# backplane.net
KiCad netlist of a schematic drawn in EAGLE
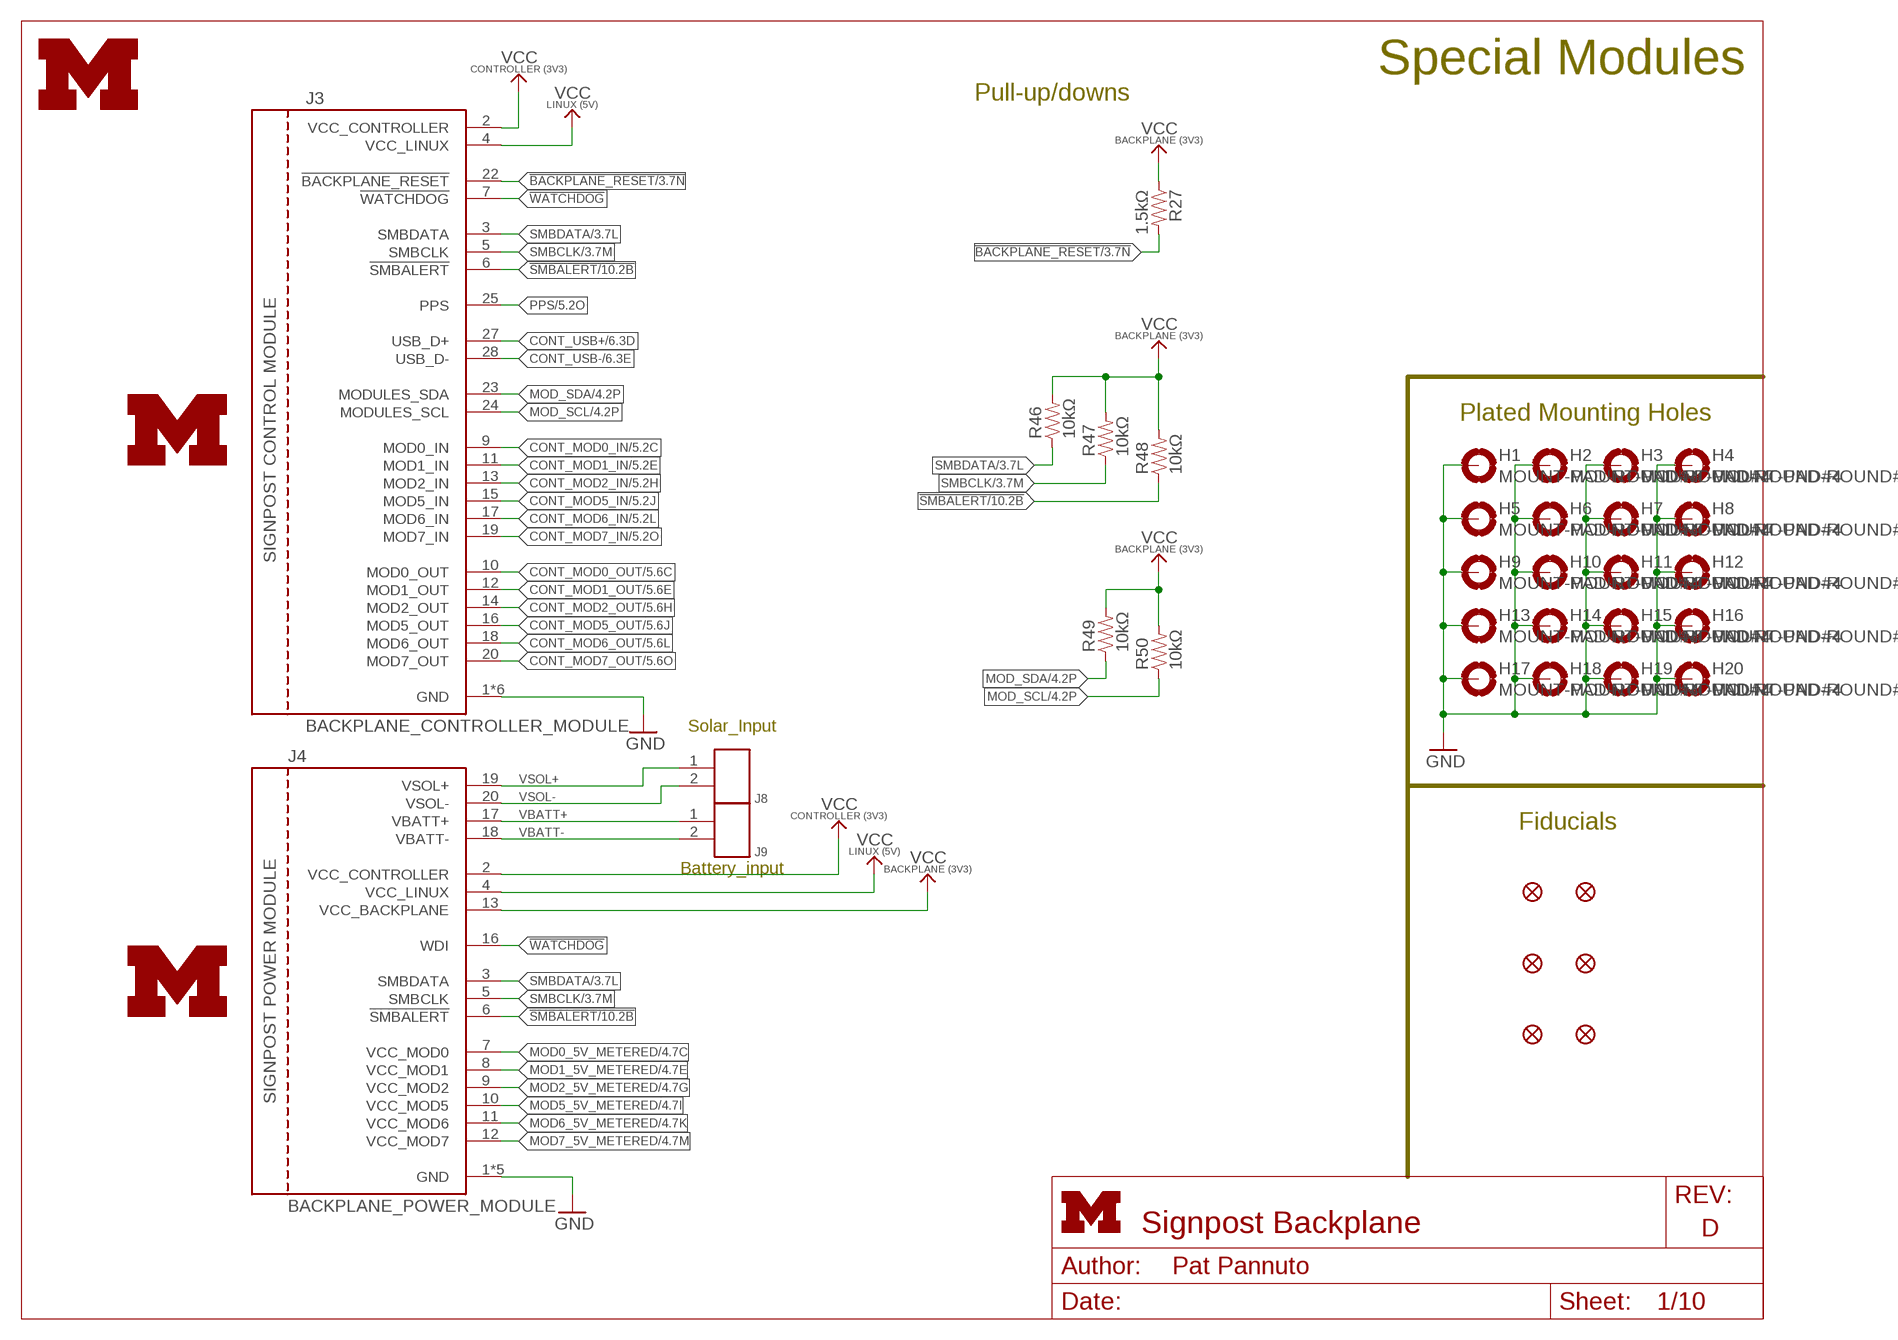
[diagram p0: schematic, sheet 1]
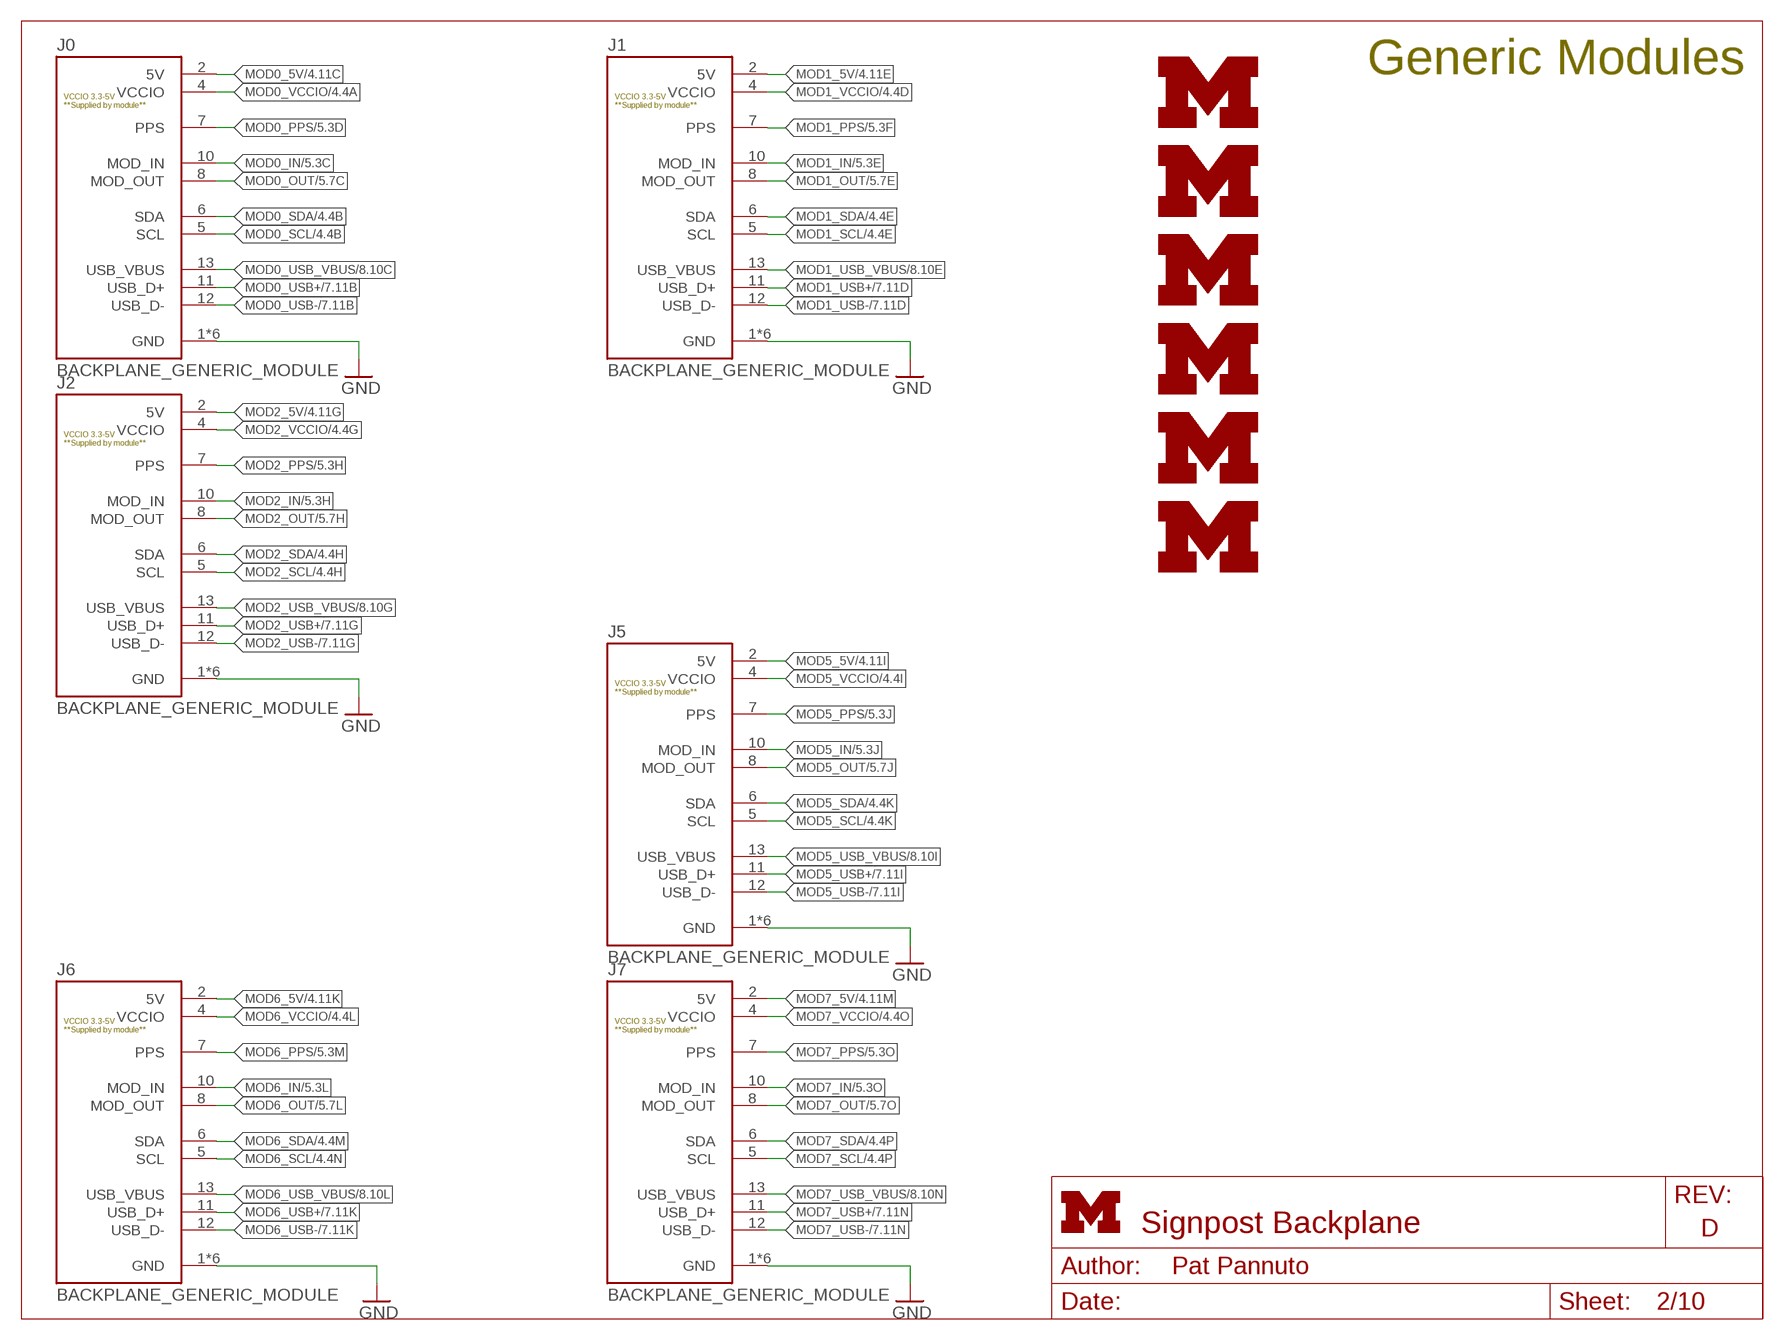
[diagram p1: schematic, sheet 2]
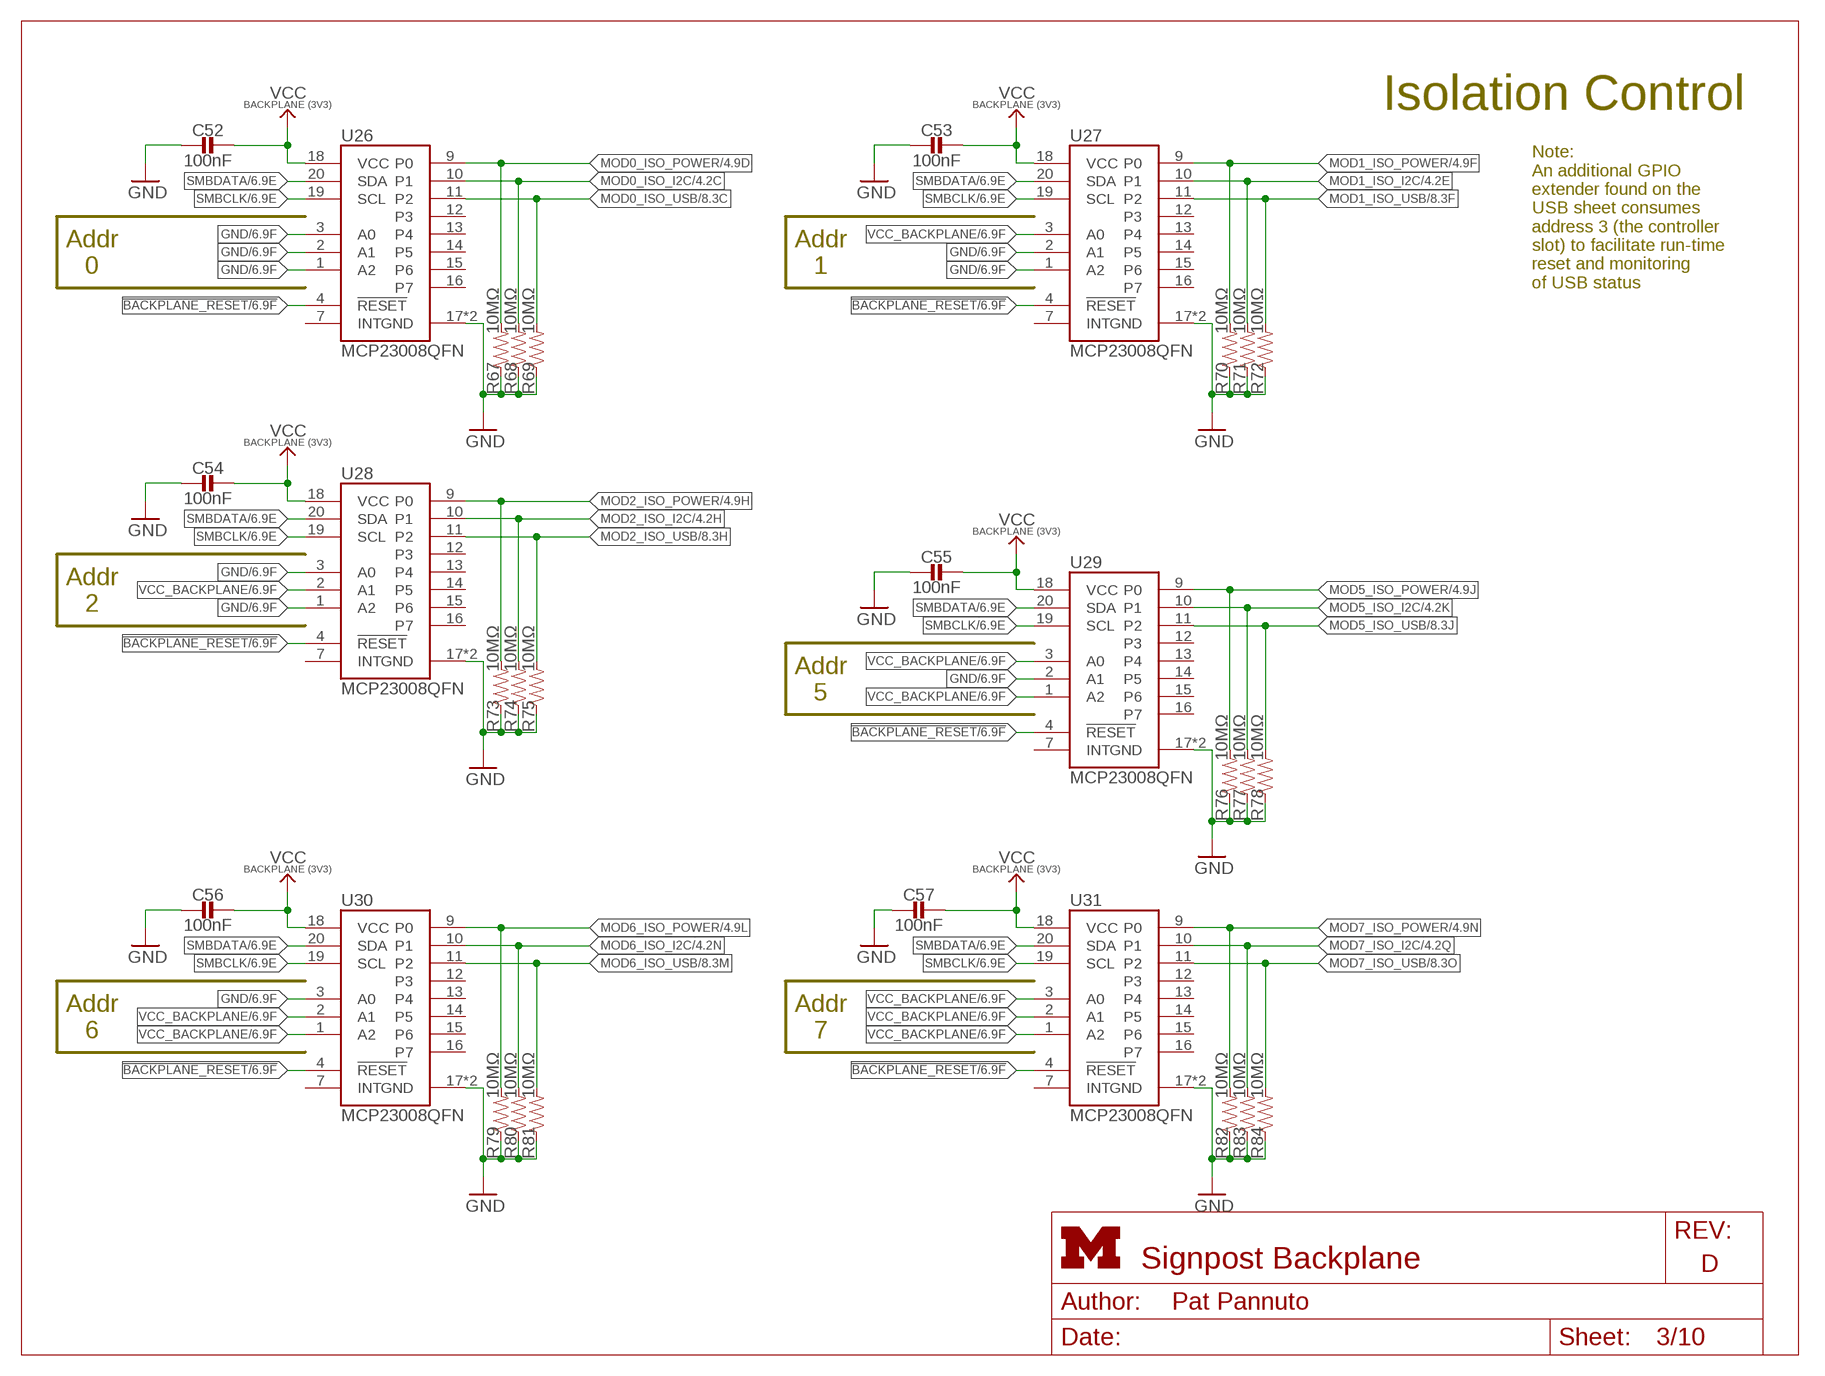
[diagram p2: schematic, sheet 3]
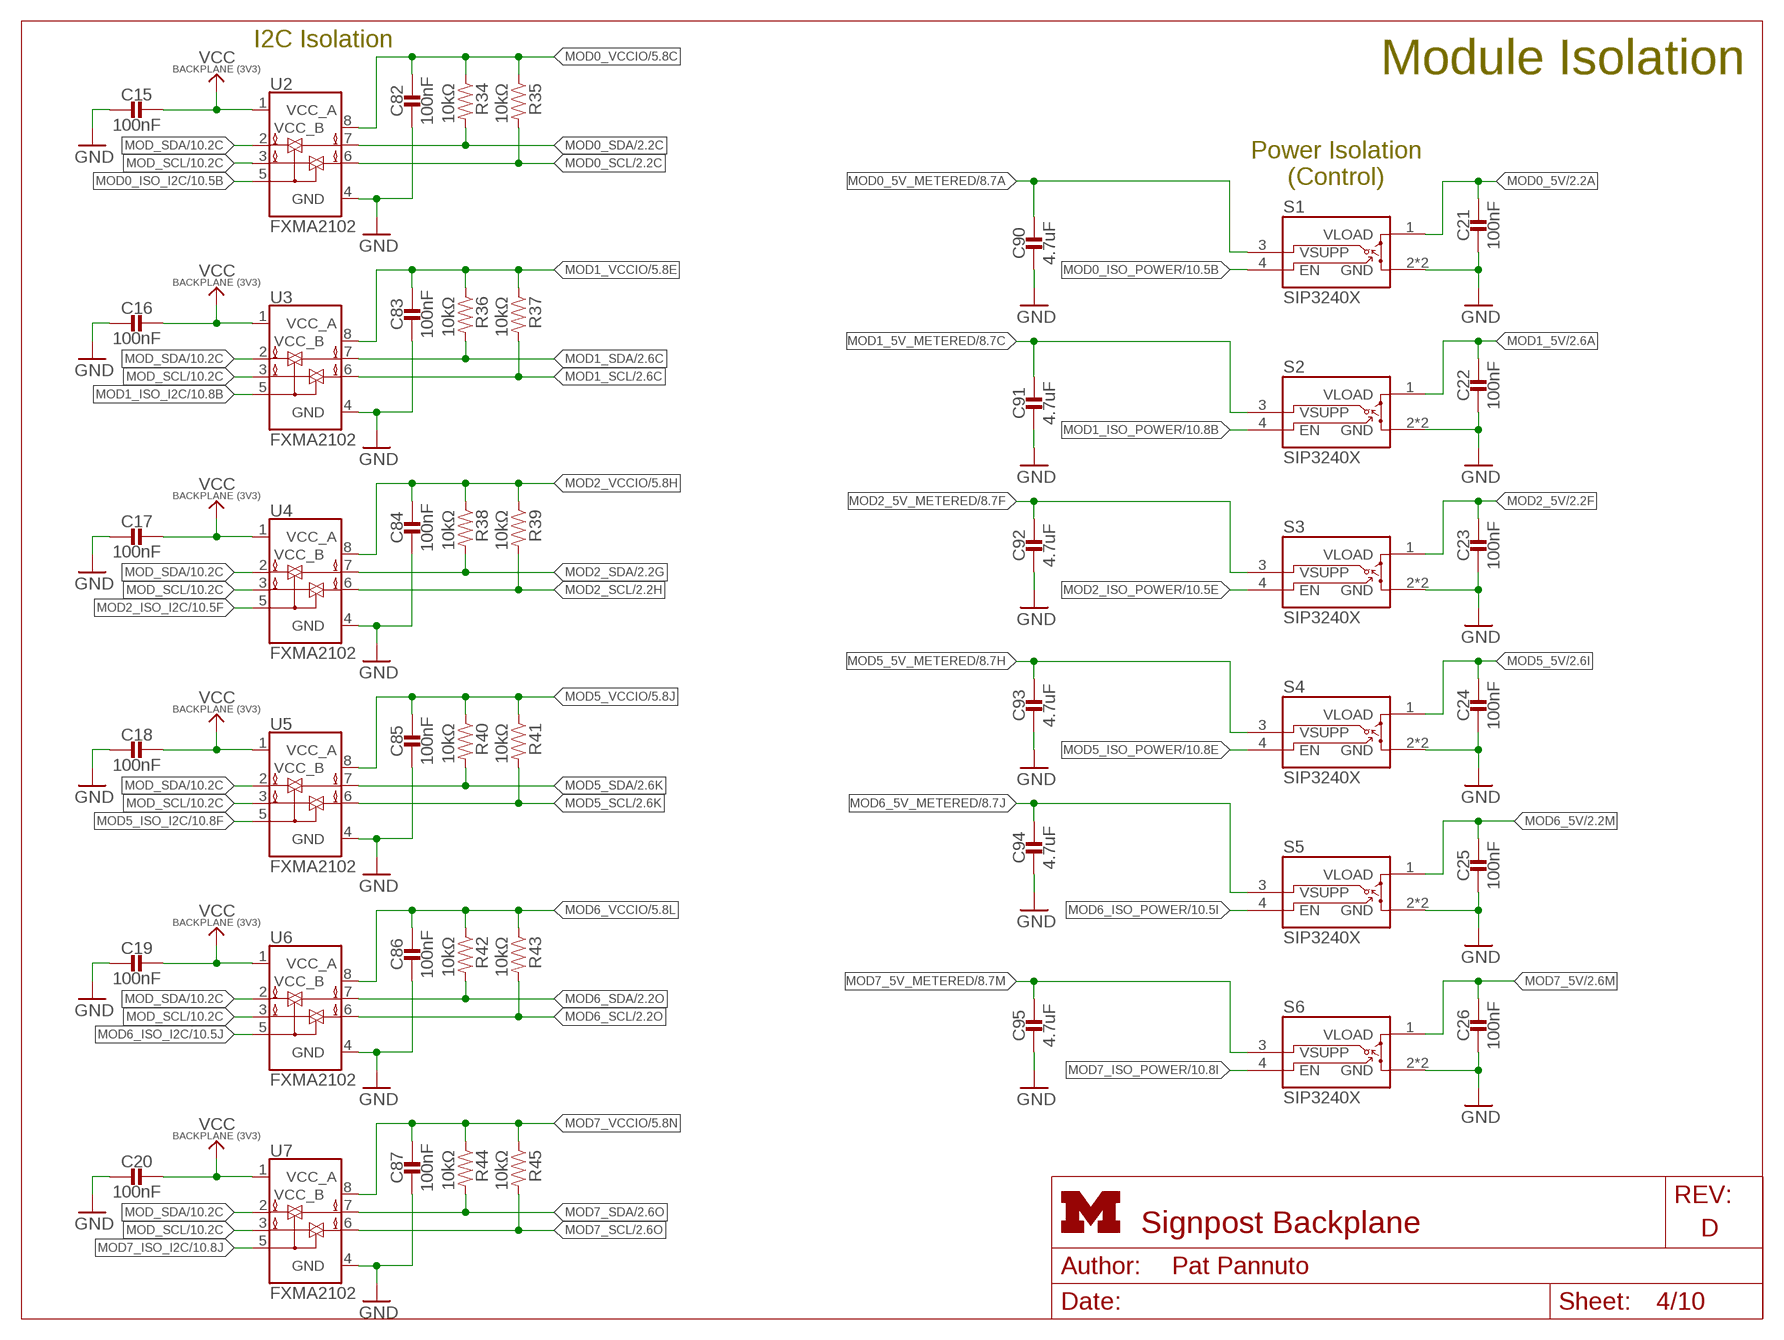
[diagram p3: schematic, sheet 4]
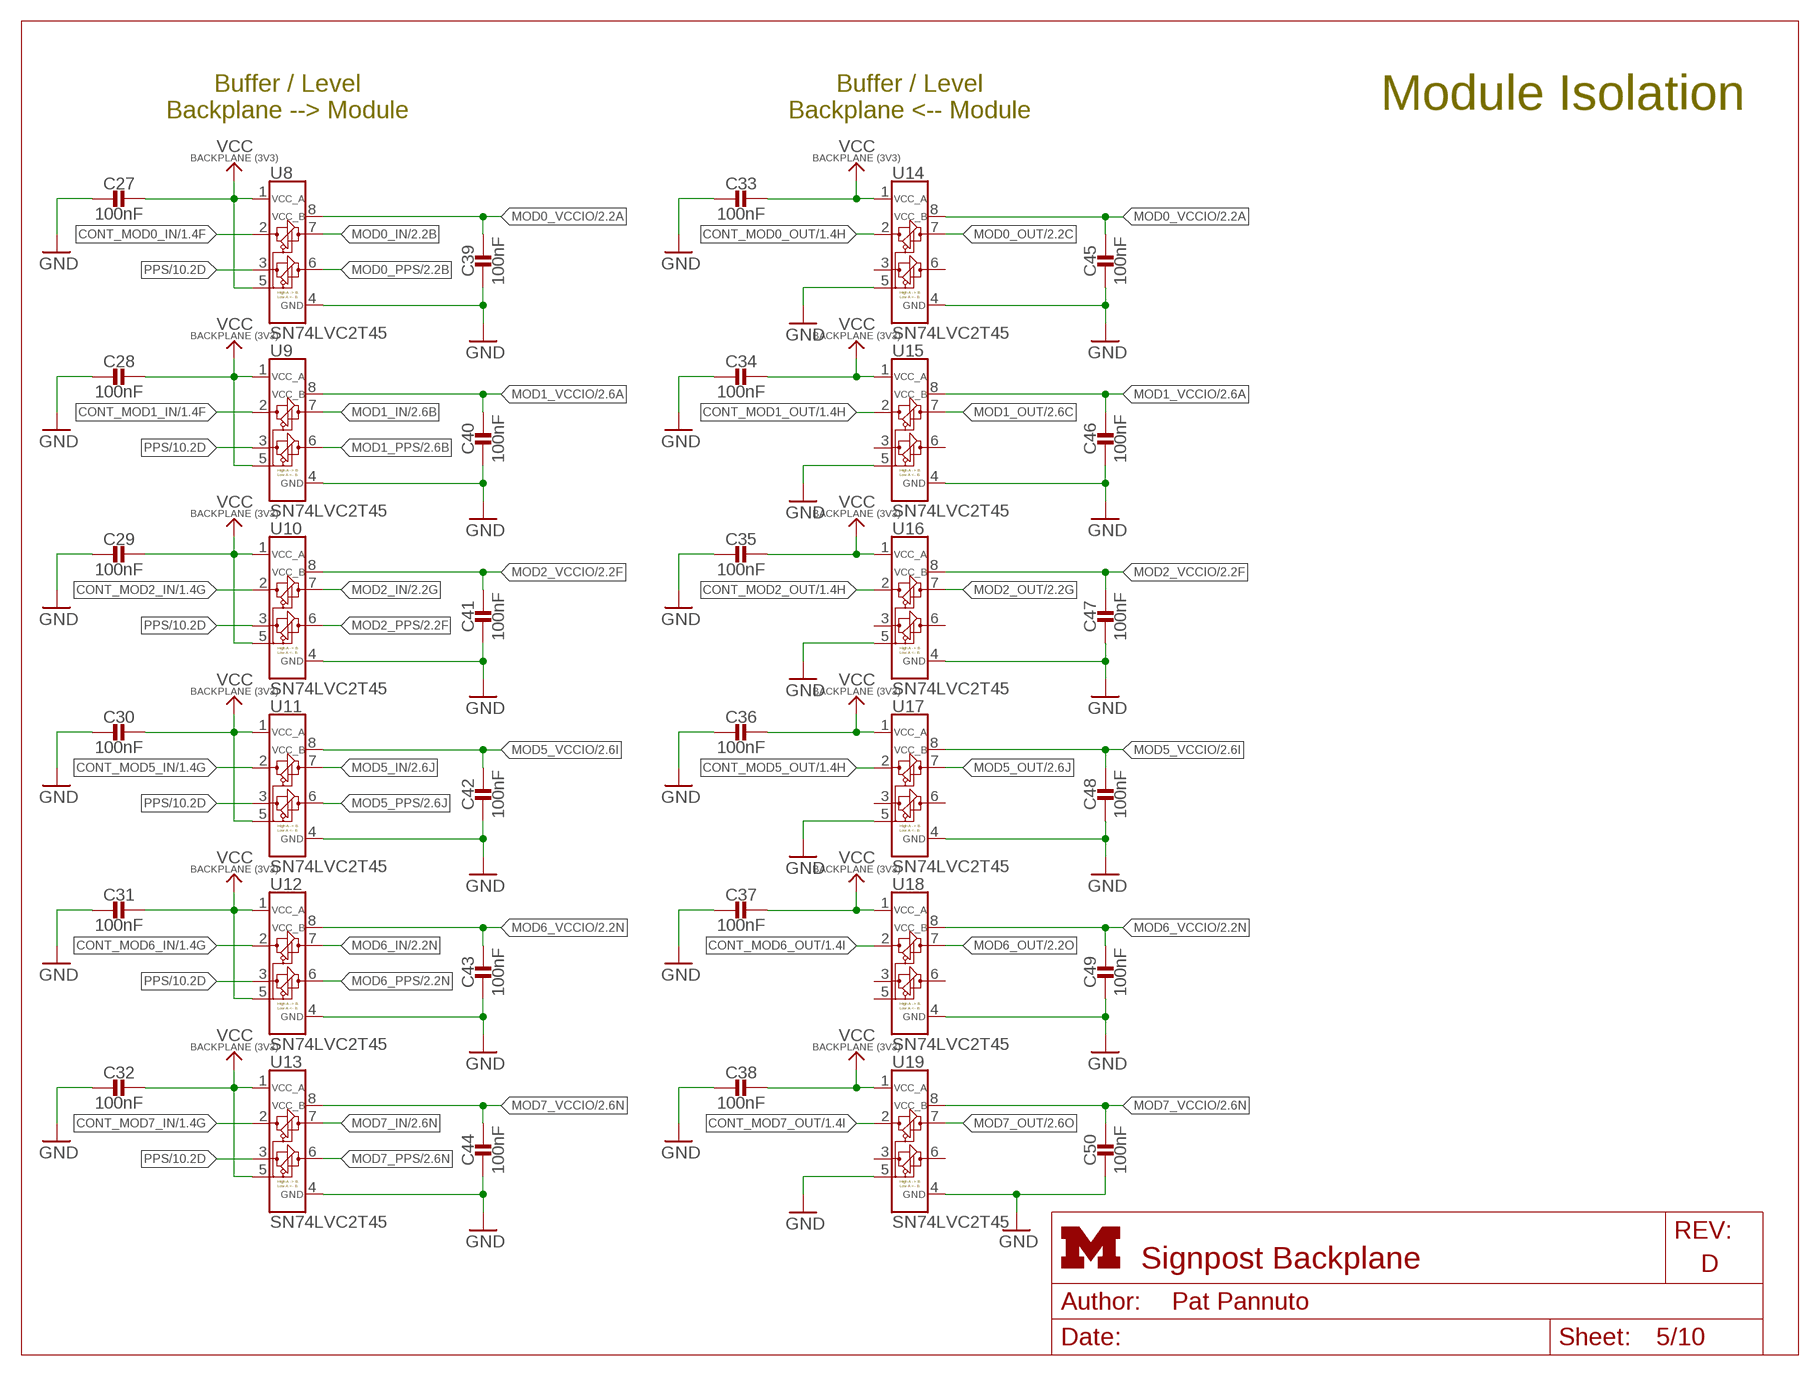
[diagram p4: schematic, sheet 5]
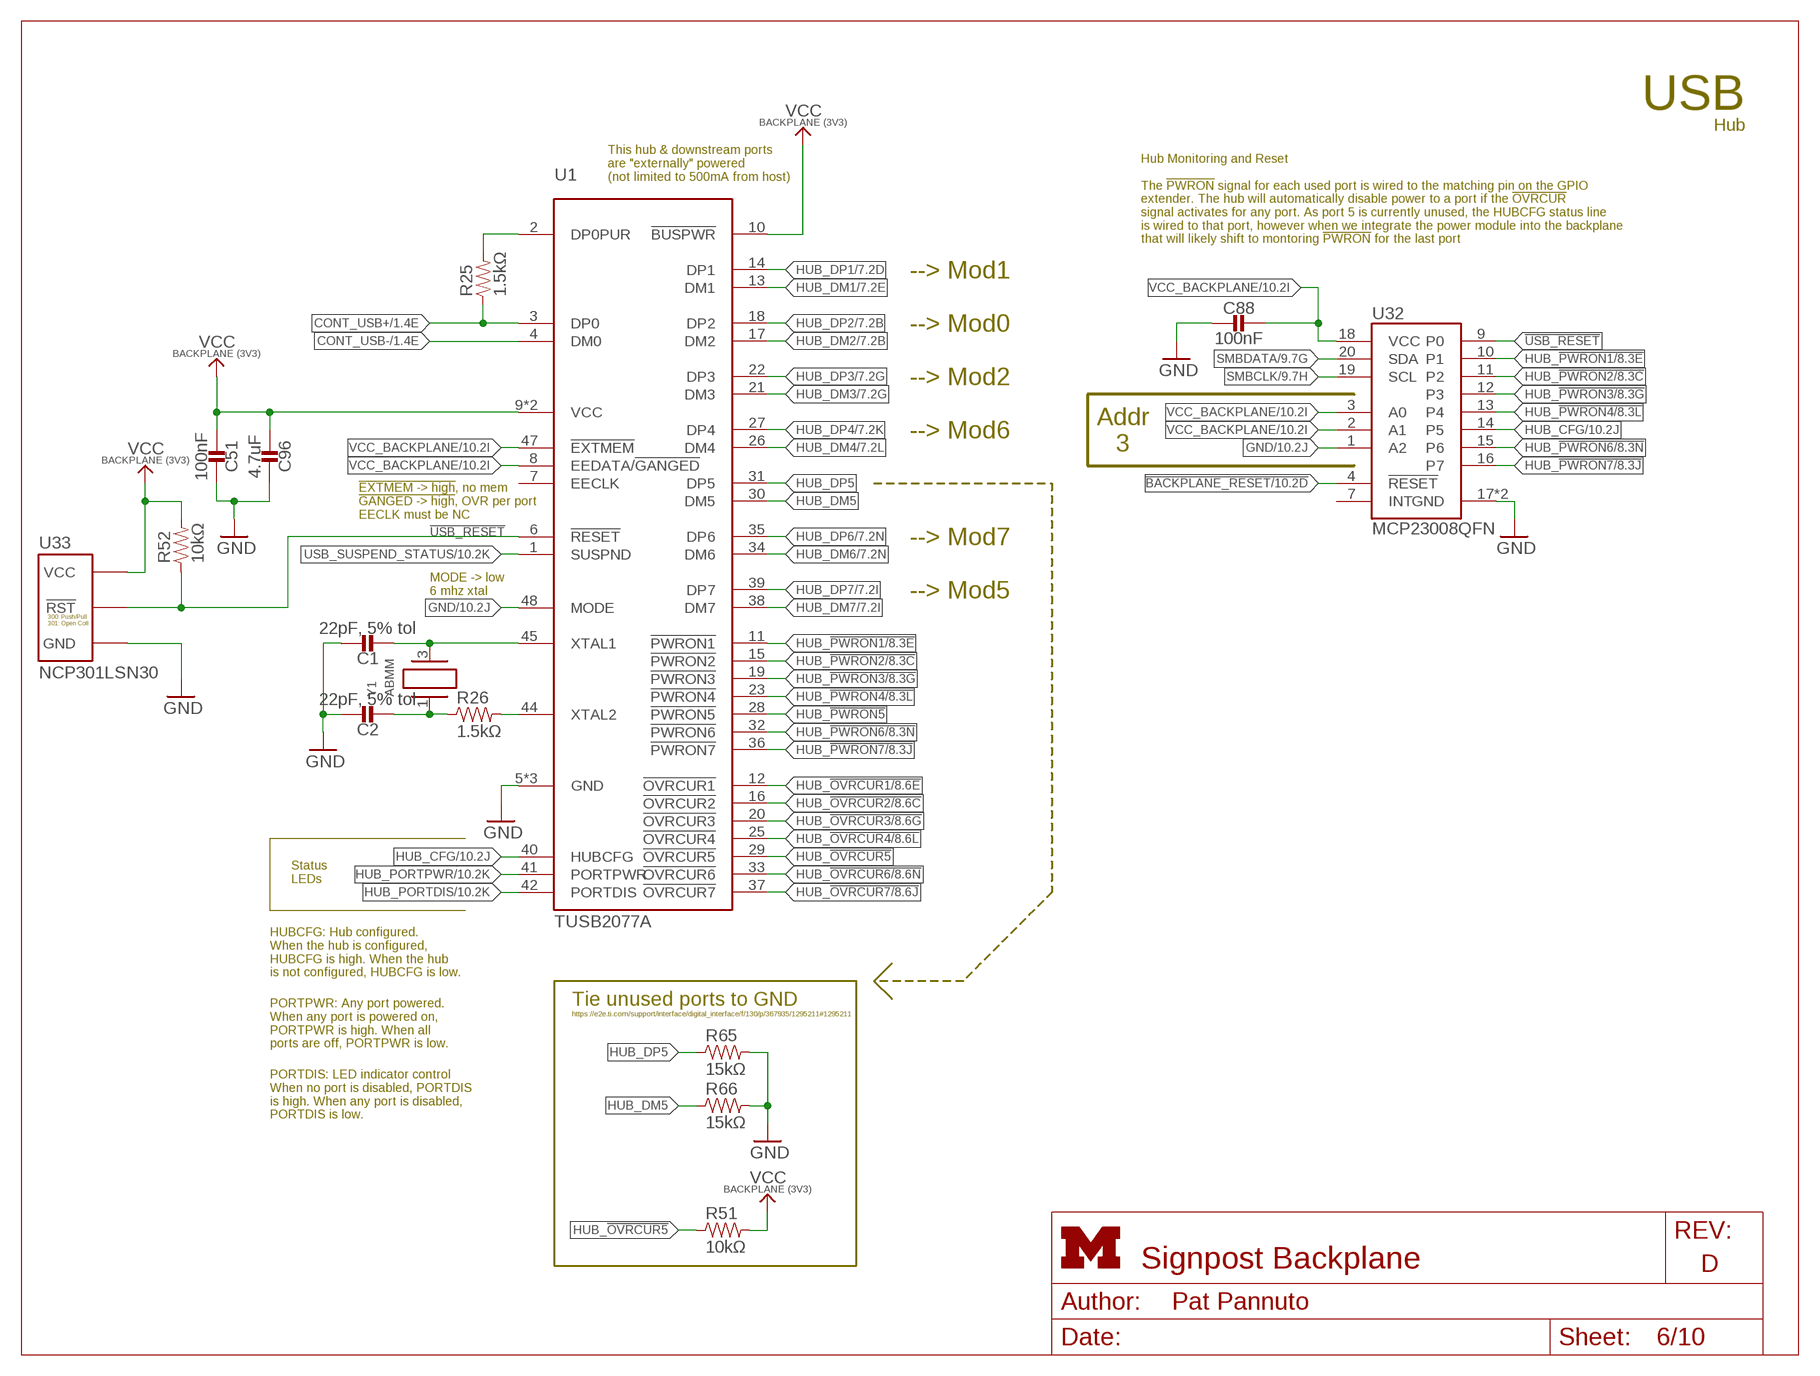
[diagram p5: schematic, sheet 6]
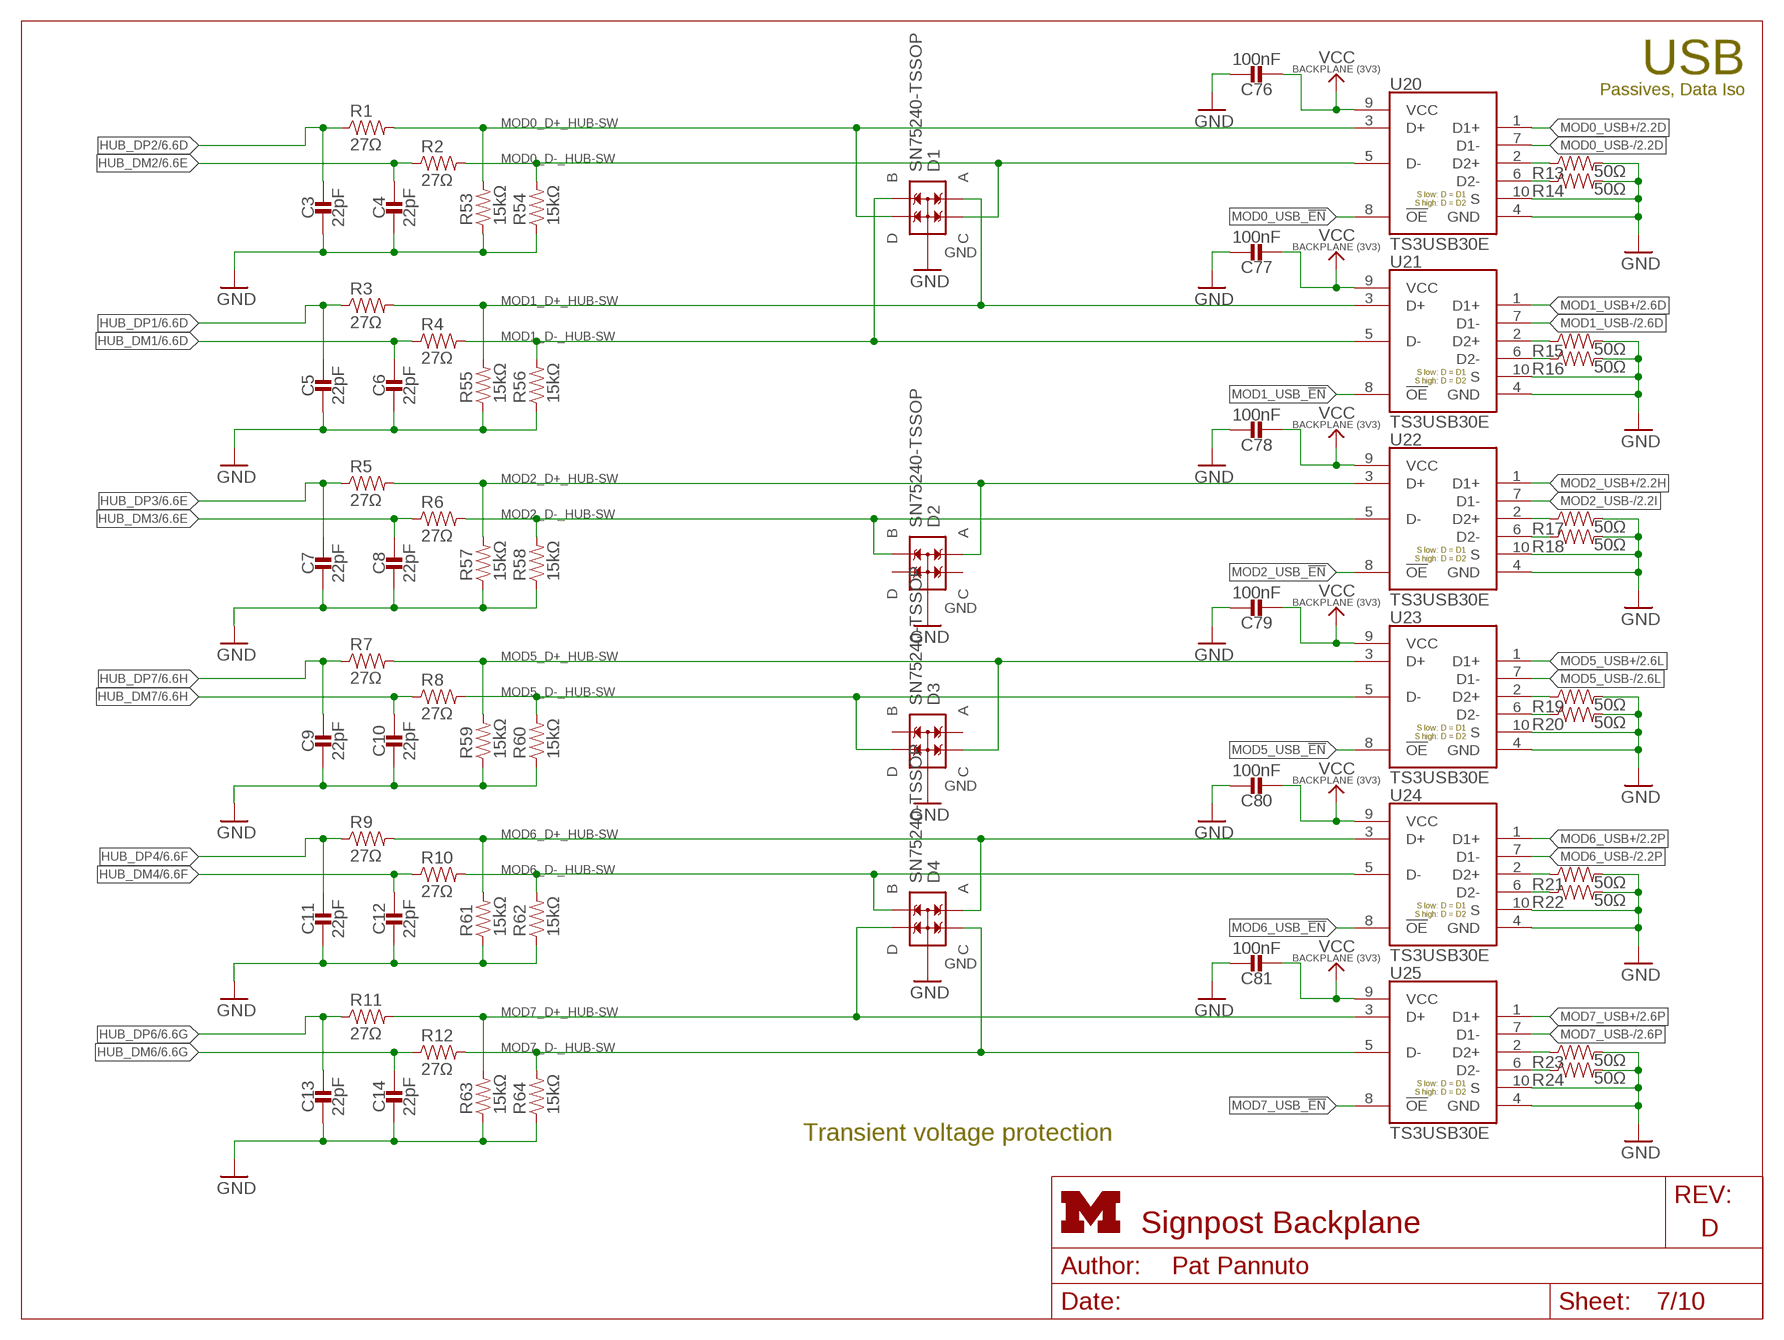
[diagram p6: schematic, sheet 7]
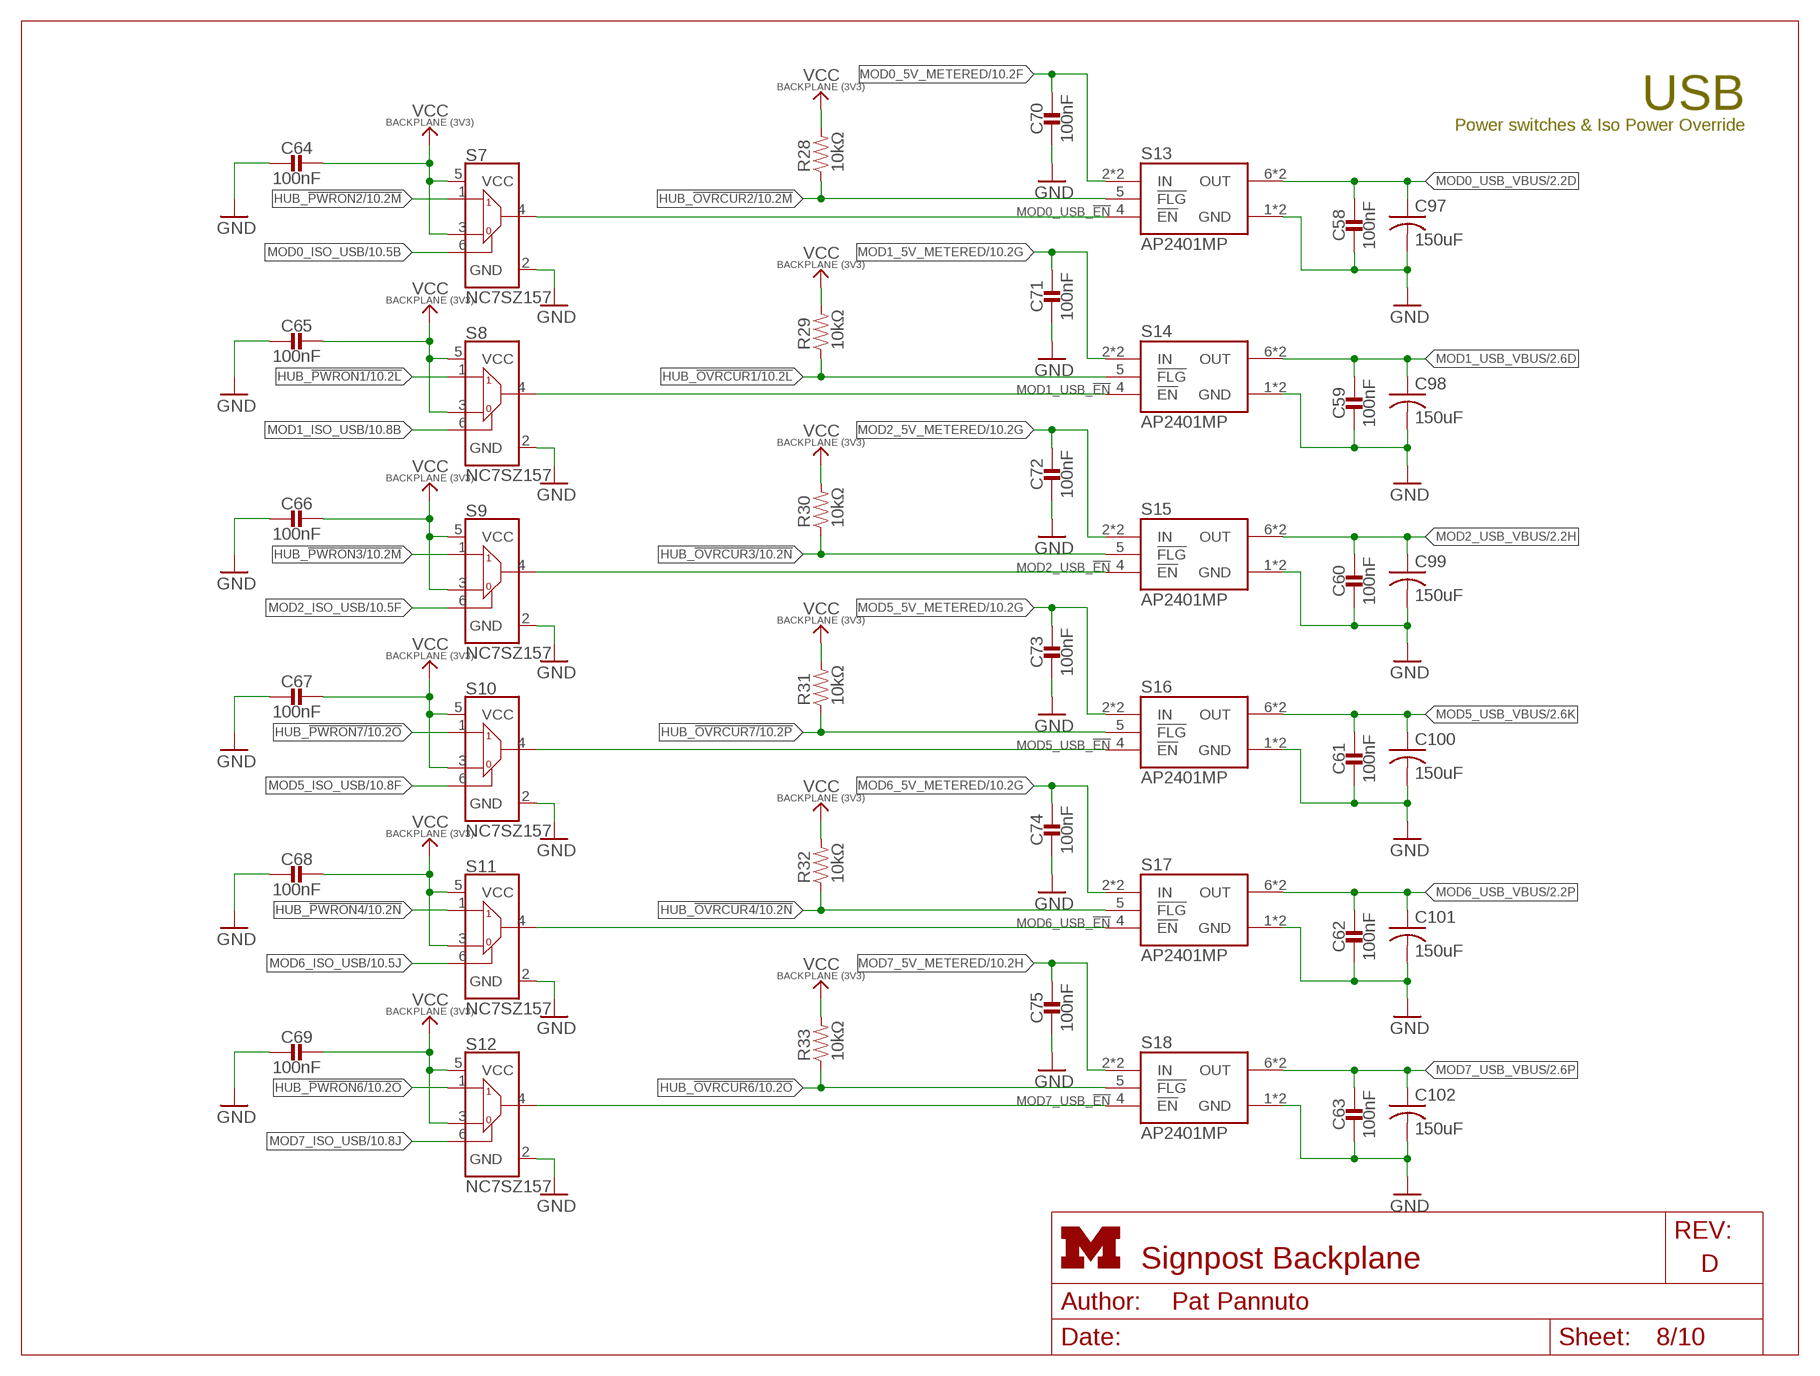
[diagram p7: schematic, sheet 8]
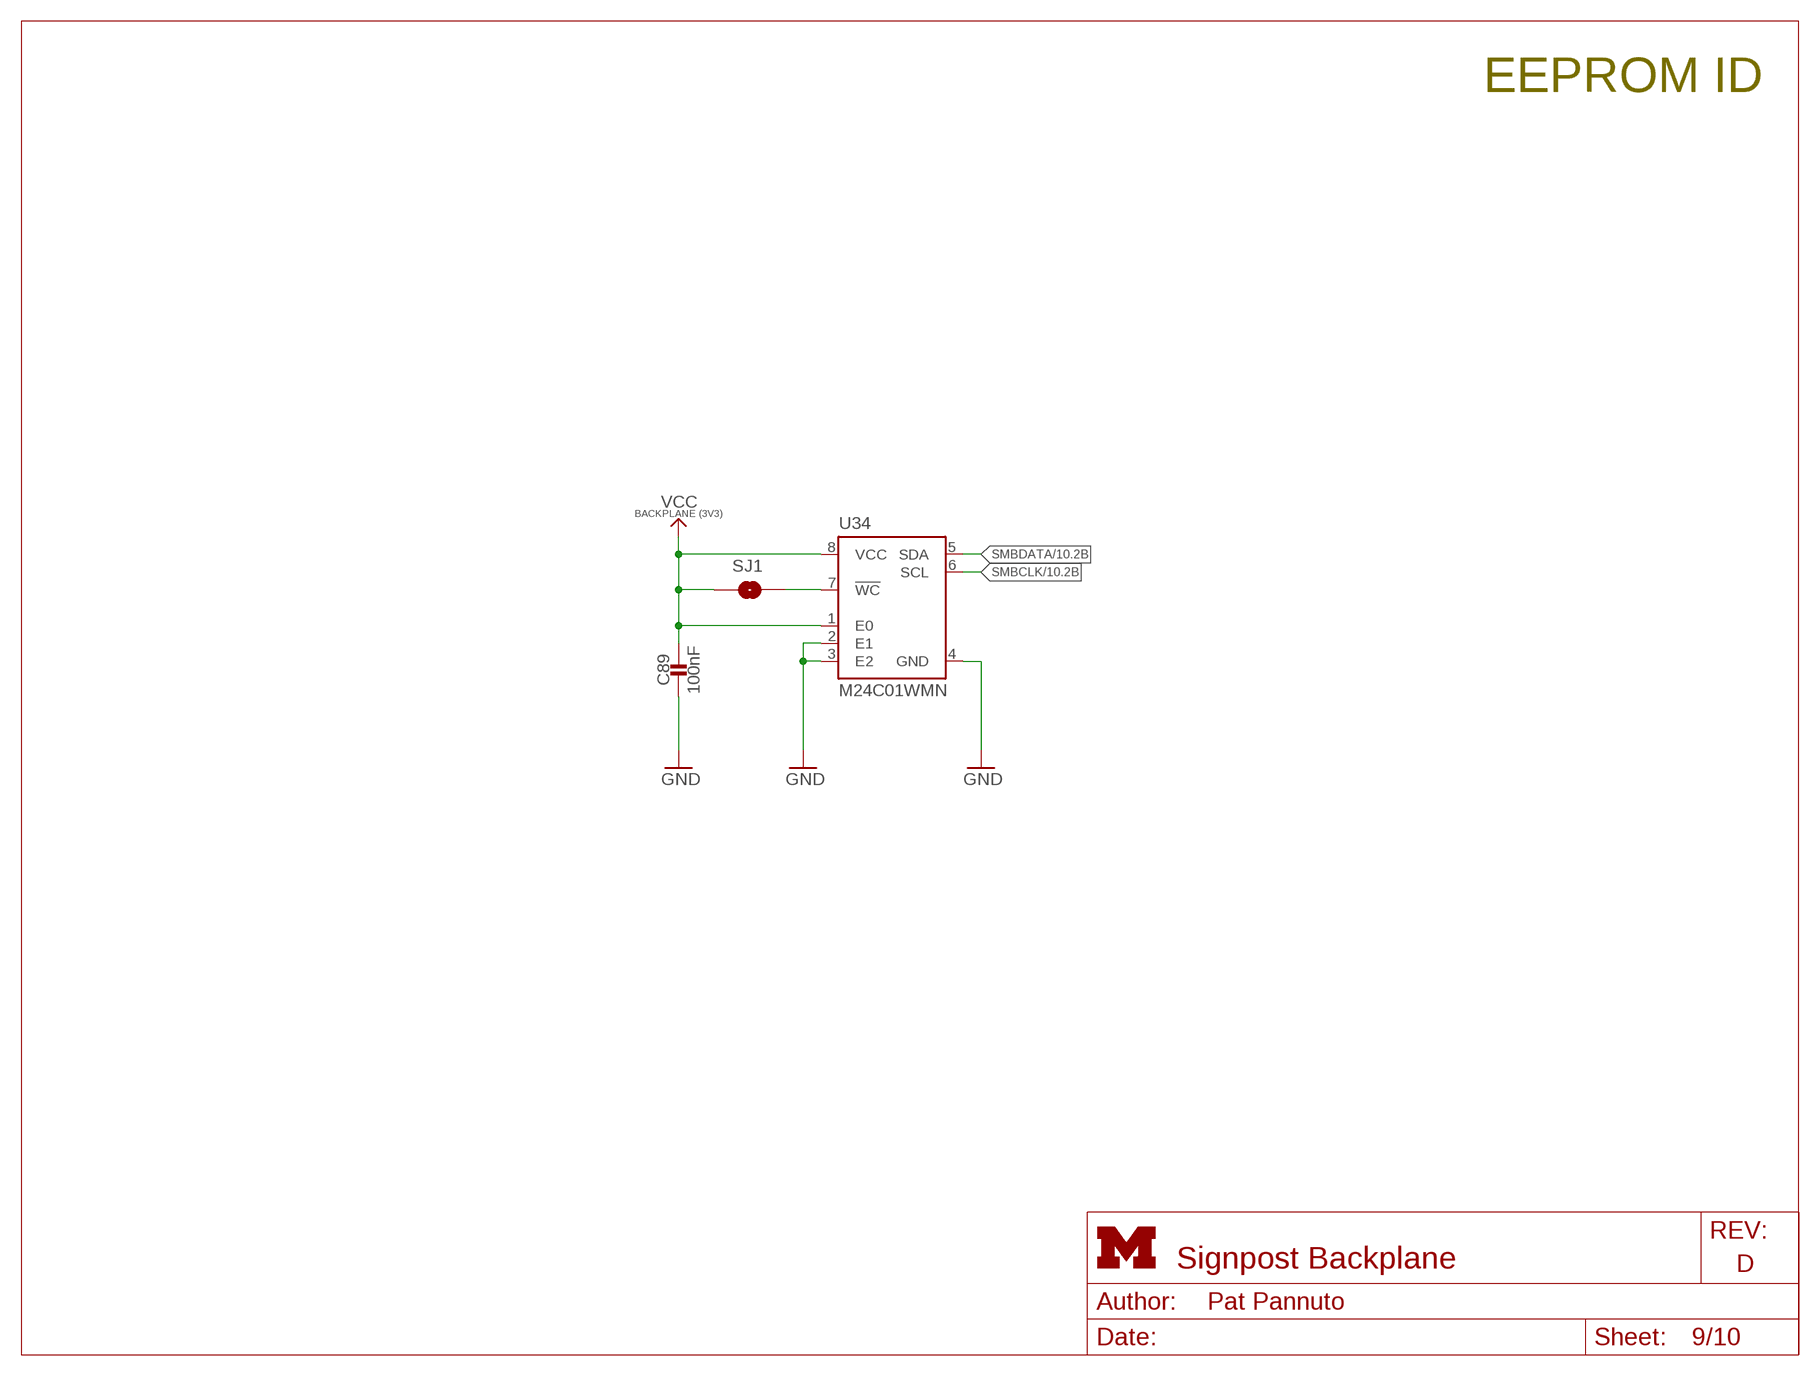
[diagram p8: schematic, sheet 9]
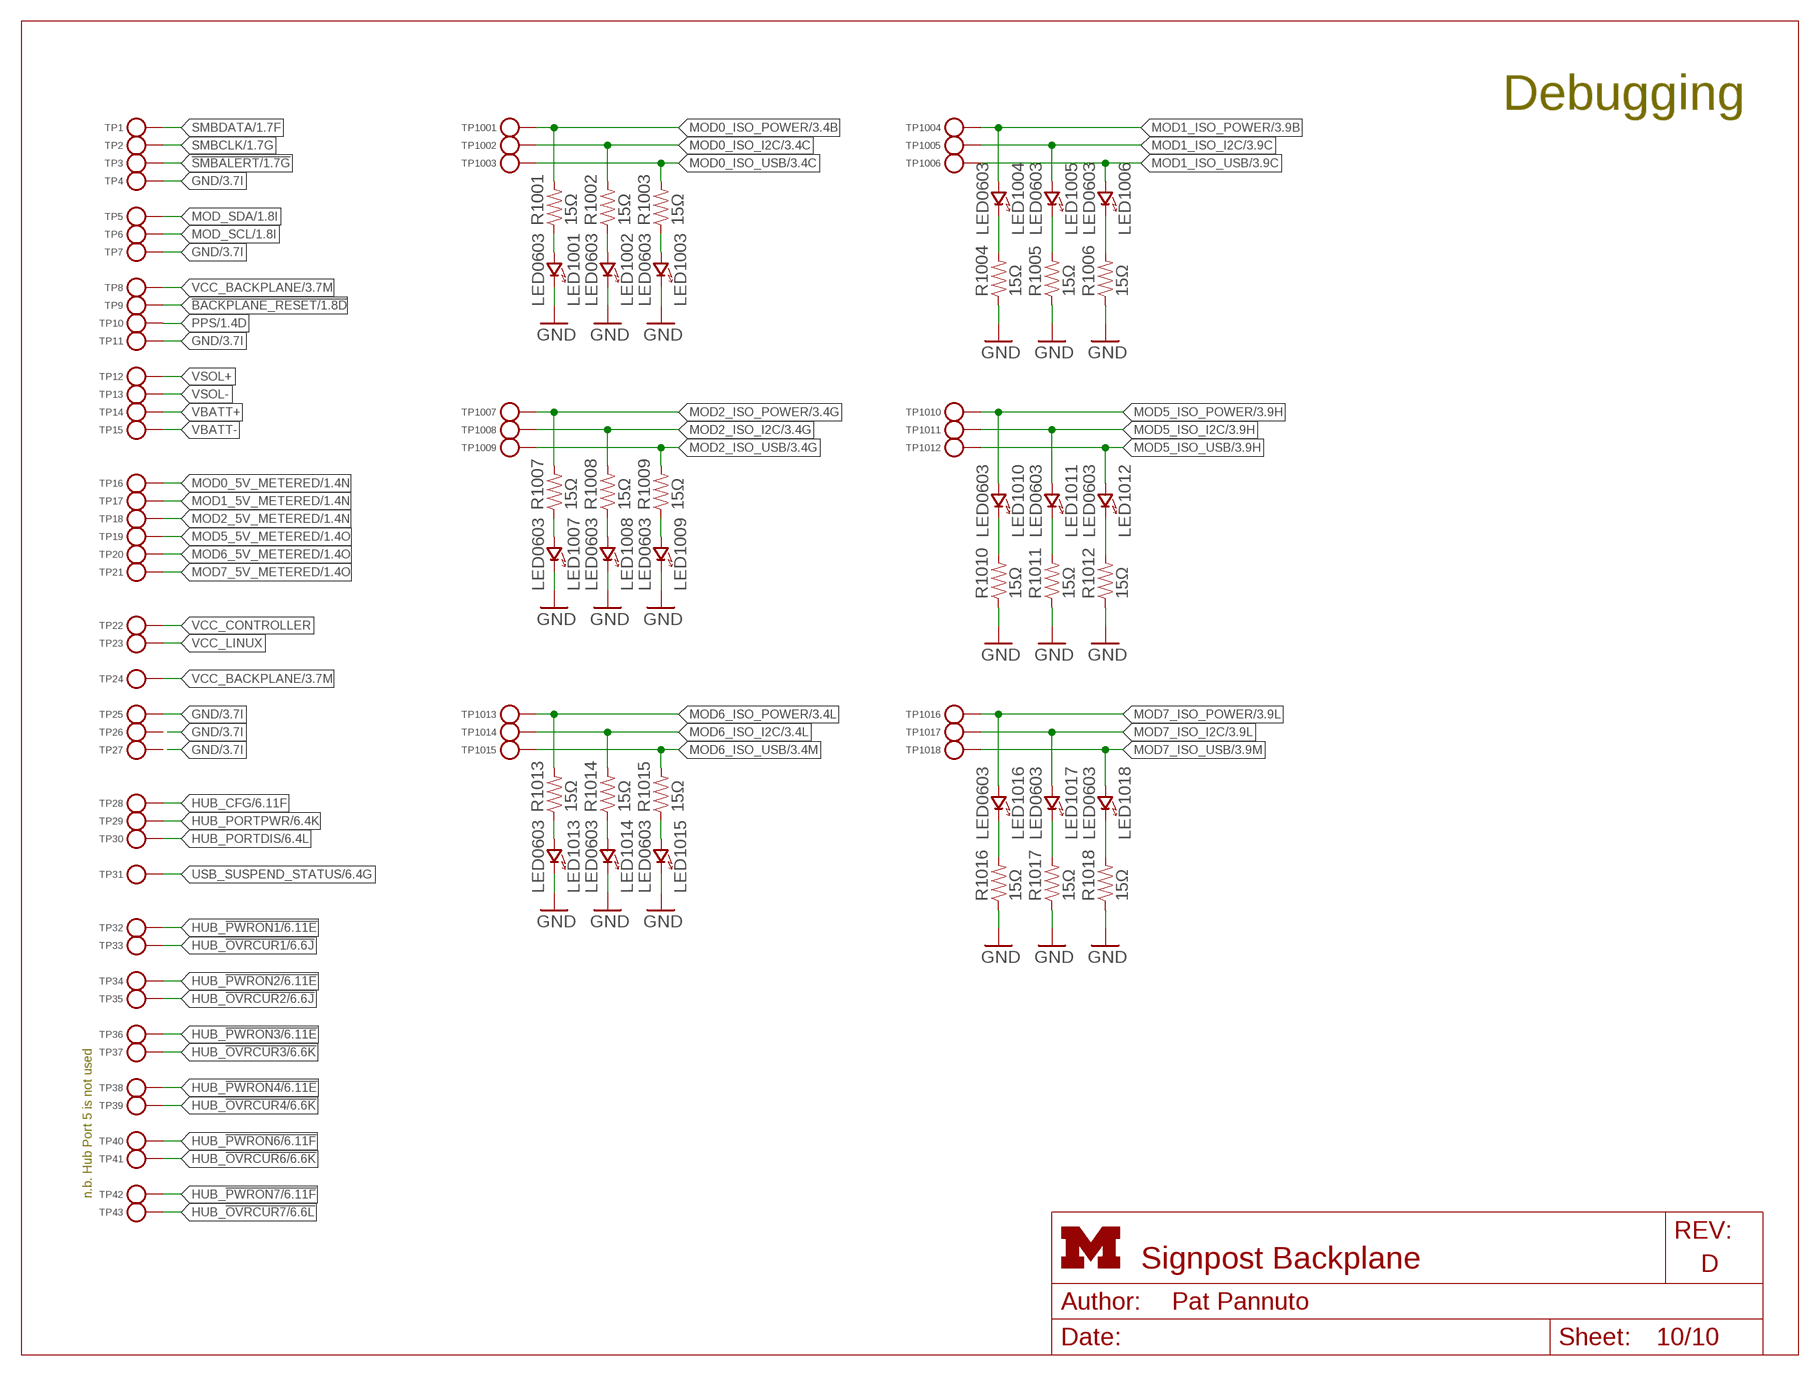
[diagram p9: schematic, sheet 10]

(export (version "E")
  (design (tool "Eeschema 10.0.6"))
  (components
    (comp (ref "C89")
      (value "100nF")
      (footprint "eagle-import:0603_CAP")
      (libsource (lib "eagle-import") (part "CAPACITOR0603_CAP"))
    )
    (comp (ref "SJ1")
      (value "SOLDERJUMPERNO")
      (footprint "eagle-import:SJ_2S-NO")
      (libsource (lib "eagle-import") (part "SOLDERJUMPERNO"))
    )
    (comp (ref "U34")
      (value "M24C01WMN")
      (footprint "eagle-import:SOIC-8")
      (libsource (lib "eagle-import") (part "M24C01WMN"))
    )
    (comp (ref "C58")
      (value "100nF")
      (footprint "eagle-import:0603_CAP")
      (libsource (lib "eagle-import") (part "CAPACITOR0603_CAP"))
    )
    (comp (ref "C59")
      (value "100nF")
      (footprint "eagle-import:0603_CAP")
      (libsource (lib "eagle-import") (part "CAPACITOR0603_CAP"))
    )
    (comp (ref "C60")
      (value "100nF")
      (footprint "eagle-import:0603_CAP")
      (libsource (lib "eagle-import") (part "CAPACITOR0603_CAP"))
    )
    (comp (ref "C61")
      (value "100nF")
      (footprint "eagle-import:0603_CAP")
      (libsource (lib "eagle-import") (part "CAPACITOR0603_CAP"))
    )
    (comp (ref "C62")
      (value "100nF")
      (footprint "eagle-import:0603_CAP")
      (libsource (lib "eagle-import") (part "CAPACITOR0603_CAP"))
    )
    (comp (ref "C63")
      (value "100nF")
      (footprint "eagle-import:0603_CAP")
      (libsource (lib "eagle-import") (part "CAPACITOR0603_CAP"))
    )
    (comp (ref "C64")
      (value "100nF")
      (footprint "eagle-import:0603_CAP")
      (libsource (lib "eagle-import") (part "CAPACITOR0603_CAP"))
    )
    (comp (ref "C65")
      (value "100nF")
      (footprint "eagle-import:0603_CAP")
      (libsource (lib "eagle-import") (part "CAPACITOR0603_CAP"))
    )
    (comp (ref "C66")
      (value "100nF")
      (footprint "eagle-import:0603_CAP")
      (libsource (lib "eagle-import") (part "CAPACITOR0603_CAP"))
    )
    (comp (ref "C67")
      (value "100nF")
      (footprint "eagle-import:0603_CAP")
      (libsource (lib "eagle-import") (part "CAPACITOR0603_CAP"))
    )
    (comp (ref "C68")
      (value "100nF")
      (footprint "eagle-import:0603_CAP")
      (libsource (lib "eagle-import") (part "CAPACITOR0603_CAP"))
    )
    (comp (ref "C69")
      (value "100nF")
      (footprint "eagle-import:0603_CAP")
      (libsource (lib "eagle-import") (part "CAPACITOR0603_CAP"))
    )
    (comp (ref "C70")
      (value "100nF")
      (footprint "eagle-import:0603_CAP")
      (libsource (lib "eagle-import") (part "CAPACITOR0603_CAP"))
    )
    (comp (ref "C71")
      (value "100nF")
      (footprint "eagle-import:0603_CAP")
      (libsource (lib "eagle-import") (part "CAPACITOR0603_CAP"))
    )
    (comp (ref "C72")
      (value "100nF")
      (footprint "eagle-import:0603_CAP")
      (libsource (lib "eagle-import") (part "CAPACITOR0603_CAP"))
    )
    (comp (ref "C73")
      (value "100nF")
      (footprint "eagle-import:0603_CAP")
      (libsource (lib "eagle-import") (part "CAPACITOR0603_CAP"))
    )
    (comp (ref "C74")
      (value "100nF")
      (footprint "eagle-import:0603_CAP")
      (libsource (lib "eagle-import") (part "CAPACITOR0603_CAP"))
    )
    (comp (ref "C75")
      (value "100nF")
      (footprint "eagle-import:0603_CAP")
      (libsource (lib "eagle-import") (part "CAPACITOR0603_CAP"))
    )
    (comp (ref "C97")
      (value "150uF")
      (footprint "eagle-import:C1206")
      (libsource (lib "eagle-import") (part "C-USC1206"))
    )
    (comp (ref "C98")
      (value "150uF")
      (footprint "eagle-import:C1206")
      (libsource (lib "eagle-import") (part "C-USC1206"))
    )
    (comp (ref "C99")
      (value "150uF")
      (footprint "eagle-import:C1206")
      (libsource (lib "eagle-import") (part "C-USC1206"))
    )
    (comp (ref "C100")
      (value "150uF")
      (footprint "eagle-import:C1206")
      (libsource (lib "eagle-import") (part "C-USC1206"))
    )
    (comp (ref "C101")
      (value "150uF")
      (footprint "eagle-import:C1206")
      (libsource (lib "eagle-import") (part "C-USC1206"))
    )
    (comp (ref "C102")
      (value "150uF")
      (footprint "eagle-import:C1206")
      (libsource (lib "eagle-import") (part "C-USC1206"))
    )
    (comp (ref "R28")
      (value "10kΩ")
      (footprint "eagle-import:0603-RES")
      (libsource (lib "eagle-import") (part "RESISTOR0603_RES"))
    )
    (comp (ref "R29")
      (value "10kΩ")
      (footprint "eagle-import:0603-RES")
      (libsource (lib "eagle-import") (part "RESISTOR0603_RES"))
    )
    (comp (ref "R30")
      (value "10kΩ")
      (footprint "eagle-import:0603-RES")
      (libsource (lib "eagle-import") (part "RESISTOR0603_RES"))
    )
    (comp (ref "R31")
      (value "10kΩ")
      (footprint "eagle-import:0603-RES")
      (libsource (lib "eagle-import") (part "RESISTOR0603_RES"))
    )
    (comp (ref "R32")
      (value "10kΩ")
      (footprint "eagle-import:0603-RES")
      (libsource (lib "eagle-import") (part "RESISTOR0603_RES"))
    )
    (comp (ref "R33")
      (value "10kΩ")
      (footprint "eagle-import:0603-RES")
      (libsource (lib "eagle-import") (part "RESISTOR0603_RES"))
    )
    (comp (ref "S7")
      (value "NC7SZ157")
      (footprint "eagle-import:SC70-6")
      (libsource (lib "eagle-import") (part "NC7SZ157"))
    )
    (comp (ref "S8")
      (value "NC7SZ157")
      (footprint "eagle-import:SC70-6")
      (libsource (lib "eagle-import") (part "NC7SZ157"))
    )
    (comp (ref "S9")
      (value "NC7SZ157")
      (footprint "eagle-import:SC70-6")
      (libsource (lib "eagle-import") (part "NC7SZ157"))
    )
    (comp (ref "S10")
      (value "NC7SZ157")
      (footprint "eagle-import:SC70-6")
      (libsource (lib "eagle-import") (part "NC7SZ157"))
    )
    (comp (ref "S11")
      (value "NC7SZ157")
      (footprint "eagle-import:SC70-6")
      (libsource (lib "eagle-import") (part "NC7SZ157"))
    )
    (comp (ref "S12")
      (value "NC7SZ157")
      (footprint "eagle-import:SC70-6")
      (libsource (lib "eagle-import") (part "NC7SZ157"))
    )
    (comp (ref "S13")
      (value "AP2401MP")
      (footprint "eagle-import:MSOP-8EP")
      (libsource (lib "eagle-import") (part "AP2401MP"))
    )
    (comp (ref "S14")
      (value "AP2401MP")
      (footprint "eagle-import:MSOP-8EP")
      (libsource (lib "eagle-import") (part "AP2401MP"))
    )
    (comp (ref "S15")
      (value "AP2401MP")
      (footprint "eagle-import:MSOP-8EP")
      (libsource (lib "eagle-import") (part "AP2401MP"))
    )
    (comp (ref "S16")
      (value "AP2401MP")
      (footprint "eagle-import:MSOP-8EP")
      (libsource (lib "eagle-import") (part "AP2401MP"))
    )
    (comp (ref "S17")
      (value "AP2401MP")
      (footprint "eagle-import:MSOP-8EP")
      (libsource (lib "eagle-import") (part "AP2401MP"))
    )
    (comp (ref "S18")
      (value "AP2401MP")
      (footprint "eagle-import:MSOP-8EP")
      (libsource (lib "eagle-import") (part "AP2401MP"))
    )
    (comp (ref "J0")
      (value "BACKPLANE_GENERIC_MODULE")
      (footprint "eagle-import:BACKPLANE_MODULE_14PIN")
      (libsource (lib "eagle-import") (part "BACKPLANE_GENERIC_MODULE"))
    )
    (comp (ref "J1")
      (value "BACKPLANE_GENERIC_MODULE")
      (footprint "eagle-import:BACKPLANE_MODULE_14PIN")
      (libsource (lib "eagle-import") (part "BACKPLANE_GENERIC_MODULE"))
    )
    (comp (ref "J2")
      (value "BACKPLANE_GENERIC_MODULE")
      (footprint "eagle-import:BACKPLANE_MODULE_14PIN")
      (libsource (lib "eagle-import") (part "BACKPLANE_GENERIC_MODULE"))
    )
    (comp (ref "J5")
      (value "BACKPLANE_GENERIC_MODULE")
      (footprint "eagle-import:BACKPLANE_MODULE_14PIN")
      (libsource (lib "eagle-import") (part "BACKPLANE_GENERIC_MODULE"))
    )
    (comp (ref "J6")
      (value "BACKPLANE_GENERIC_MODULE")
      (footprint "eagle-import:BACKPLANE_MODULE_14PIN")
      (libsource (lib "eagle-import") (part "BACKPLANE_GENERIC_MODULE"))
    )
    (comp (ref "J7")
      (value "BACKPLANE_GENERIC_MODULE")
      (footprint "eagle-import:BACKPLANE_MODULE_14PIN")
      (libsource (lib "eagle-import") (part "BACKPLANE_GENERIC_MODULE"))
    )
    (comp (ref "LOGO2")
      (value "UMICH_SOLID_MEDIUM")
      (footprint "eagle-import:UMICH_SOLID_200MIL")
      (libsource (lib "eagle-import") (part "UMICH_SOLID_MEDIUM"))
    )
    (comp (ref "LOGO3")
      (value "UMICH_SOLID_MEDIUM")
      (footprint "eagle-import:UMICH_SOLID_200MIL")
      (libsource (lib "eagle-import") (part "UMICH_SOLID_MEDIUM"))
    )
    (comp (ref "LOGO4")
      (value "UMICH_SOLID_MEDIUM")
      (footprint "eagle-import:UMICH_SOLID_200MIL")
      (libsource (lib "eagle-import") (part "UMICH_SOLID_MEDIUM"))
    )
    (comp (ref "LOGO5")
      (value "UMICH_SOLID_MEDIUM")
      (footprint "eagle-import:UMICH_SOLID_200MIL")
      (libsource (lib "eagle-import") (part "UMICH_SOLID_MEDIUM"))
    )
    (comp (ref "LOGO6")
      (value "UMICH_SOLID_MEDIUM")
      (footprint "eagle-import:UMICH_SOLID_200MIL")
      (libsource (lib "eagle-import") (part "UMICH_SOLID_MEDIUM"))
    )
    (comp (ref "LOGO7")
      (value "UMICH_SOLID_MEDIUM")
      (footprint "eagle-import:UMICH_SOLID_200MIL")
      (libsource (lib "eagle-import") (part "UMICH_SOLID_MEDIUM"))
    )
    (comp (ref "C52")
      (value "100nF")
      (footprint "eagle-import:0603_CAP")
      (libsource (lib "eagle-import") (part "CAPACITOR0603_CAP"))
    )
    (comp (ref "C53")
      (value "100nF")
      (footprint "eagle-import:0603_CAP")
      (libsource (lib "eagle-import") (part "CAPACITOR0603_CAP"))
    )
    (comp (ref "C54")
      (value "100nF")
      (footprint "eagle-import:0603_CAP")
      (libsource (lib "eagle-import") (part "CAPACITOR0603_CAP"))
    )
    (comp (ref "C55")
      (value "100nF")
      (footprint "eagle-import:0603_CAP")
      (libsource (lib "eagle-import") (part "CAPACITOR0603_CAP"))
    )
    (comp (ref "C56")
      (value "100nF")
      (footprint "eagle-import:0603_CAP")
      (libsource (lib "eagle-import") (part "CAPACITOR0603_CAP"))
    )
    (comp (ref "C57")
      (value "100nF")
      (footprint "eagle-import:0603_CAP")
      (libsource (lib "eagle-import") (part "CAPACITOR0603_CAP"))
    )
    (comp (ref "R67")
      (value "10MΩ")
      (footprint "eagle-import:0603-RES")
      (libsource (lib "eagle-import") (part "RESISTOR0603_RES"))
    )
    (comp (ref "R68")
      (value "10MΩ")
      (footprint "eagle-import:0603-RES")
      (libsource (lib "eagle-import") (part "RESISTOR0603_RES"))
    )
    (comp (ref "R69")
      (value "10MΩ")
      (footprint "eagle-import:0603-RES")
      (libsource (lib "eagle-import") (part "RESISTOR0603_RES"))
    )
    (comp (ref "R70")
      (value "10MΩ")
      (footprint "eagle-import:0603-RES")
      (libsource (lib "eagle-import") (part "RESISTOR0603_RES"))
    )
    (comp (ref "R71")
      (value "10MΩ")
      (footprint "eagle-import:0603-RES")
      (libsource (lib "eagle-import") (part "RESISTOR0603_RES"))
    )
    (comp (ref "R72")
      (value "10MΩ")
      (footprint "eagle-import:0603-RES")
      (libsource (lib "eagle-import") (part "RESISTOR0603_RES"))
    )
    (comp (ref "R73")
      (value "10MΩ")
      (footprint "eagle-import:0603-RES")
      (libsource (lib "eagle-import") (part "RESISTOR0603_RES"))
    )
    (comp (ref "R74")
      (value "10MΩ")
      (footprint "eagle-import:0603-RES")
      (libsource (lib "eagle-import") (part "RESISTOR0603_RES"))
    )
    (comp (ref "R75")
      (value "10MΩ")
      (footprint "eagle-import:0603-RES")
      (libsource (lib "eagle-import") (part "RESISTOR0603_RES"))
    )
    (comp (ref "R76")
      (value "10MΩ")
      (footprint "eagle-import:0603-RES")
      (libsource (lib "eagle-import") (part "RESISTOR0603_RES"))
    )
    (comp (ref "R77")
      (value "10MΩ")
      (footprint "eagle-import:0603-RES")
      (libsource (lib "eagle-import") (part "RESISTOR0603_RES"))
    )
    (comp (ref "R78")
      (value "10MΩ")
      (footprint "eagle-import:0603-RES")
      (libsource (lib "eagle-import") (part "RESISTOR0603_RES"))
    )
    (comp (ref "R79")
      (value "10MΩ")
      (footprint "eagle-import:0603-RES")
      (libsource (lib "eagle-import") (part "RESISTOR0603_RES"))
    )
    (comp (ref "R80")
      (value "10MΩ")
      (footprint "eagle-import:0603-RES")
      (libsource (lib "eagle-import") (part "RESISTOR0603_RES"))
    )
    (comp (ref "R81")
      (value "10MΩ")
      (footprint "eagle-import:0603-RES")
      (libsource (lib "eagle-import") (part "RESISTOR0603_RES"))
    )
    (comp (ref "R82")
      (value "10MΩ")
      (footprint "eagle-import:0603-RES")
      (libsource (lib "eagle-import") (part "RESISTOR0603_RES"))
    )
    (comp (ref "R83")
      (value "10MΩ")
      (footprint "eagle-import:0603-RES")
      (libsource (lib "eagle-import") (part "RESISTOR0603_RES"))
    )
    (comp (ref "R84")
      (value "10MΩ")
      (footprint "eagle-import:0603-RES")
      (libsource (lib "eagle-import") (part "RESISTOR0603_RES"))
    )
    (comp (ref "U26")
      (value "MCP23008QFN")
      (footprint "eagle-import:QFN-20-4MM")
      (libsource (lib "eagle-import") (part "MCP23008QFN"))
    )
    (comp (ref "U27")
      (value "MCP23008QFN")
      (footprint "eagle-import:QFN-20-4MM")
      (libsource (lib "eagle-import") (part "MCP23008QFN"))
    )
    (comp (ref "U28")
      (value "MCP23008QFN")
      (footprint "eagle-import:QFN-20-4MM")
      (libsource (lib "eagle-import") (part "MCP23008QFN"))
    )
    (comp (ref "U29")
      (value "MCP23008QFN")
      (footprint "eagle-import:QFN-20-4MM")
      (libsource (lib "eagle-import") (part "MCP23008QFN"))
    )
    (comp (ref "U30")
      (value "MCP23008QFN")
      (footprint "eagle-import:QFN-20-4MM")
      (libsource (lib "eagle-import") (part "MCP23008QFN"))
    )
    (comp (ref "U31")
      (value "MCP23008QFN")
      (footprint "eagle-import:QFN-20-4MM")
      (libsource (lib "eagle-import") (part "MCP23008QFN"))
    )
    (comp (ref "LED1001")
      (value "LED0603")
      (footprint "eagle-import:LED-0603")
      (libsource (lib "eagle-import") (part "LED0603"))
    )
    (comp (ref "LED1002")
      (value "LED0603")
      (footprint "eagle-import:LED-0603")
      (libsource (lib "eagle-import") (part "LED0603"))
    )
    (comp (ref "LED1003")
      (value "LED0603")
      (footprint "eagle-import:LED-0603")
      (libsource (lib "eagle-import") (part "LED0603"))
    )
    (comp (ref "LED1004")
      (value "LED0603")
      (footprint "eagle-import:LED-0603")
      (libsource (lib "eagle-import") (part "LED0603"))
    )
    (comp (ref "LED1005")
      (value "LED0603")
      (footprint "eagle-import:LED-0603")
      (libsource (lib "eagle-import") (part "LED0603"))
    )
    (comp (ref "LED1006")
      (value "LED0603")
      (footprint "eagle-import:LED-0603")
      (libsource (lib "eagle-import") (part "LED0603"))
    )
    (comp (ref "LED1007")
      (value "LED0603")
      (footprint "eagle-import:LED-0603")
      (libsource (lib "eagle-import") (part "LED0603"))
    )
    (comp (ref "LED1008")
      (value "LED0603")
      (footprint "eagle-import:LED-0603")
      (libsource (lib "eagle-import") (part "LED0603"))
    )
    (comp (ref "LED1009")
      (value "LED0603")
      (footprint "eagle-import:LED-0603")
      (libsource (lib "eagle-import") (part "LED0603"))
    )
    (comp (ref "LED1010")
      (value "LED0603")
      (footprint "eagle-import:LED-0603")
      (libsource (lib "eagle-import") (part "LED0603"))
    )
    (comp (ref "LED1011")
      (value "LED0603")
      (footprint "eagle-import:LED-0603")
      (libsource (lib "eagle-import") (part "LED0603"))
    )
    (comp (ref "LED1012")
      (value "LED0603")
      (footprint "eagle-import:LED-0603")
      (libsource (lib "eagle-import") (part "LED0603"))
    )
    (comp (ref "LED1013")
      (value "LED0603")
      (footprint "eagle-import:LED-0603")
      (libsource (lib "eagle-import") (part "LED0603"))
    )
    (comp (ref "LED1014")
      (value "LED0603")
      (footprint "eagle-import:LED-0603")
      (libsource (lib "eagle-import") (part "LED0603"))
    )
    (comp (ref "LED1015")
      (value "LED0603")
      (footprint "eagle-import:LED-0603")
      (libsource (lib "eagle-import") (part "LED0603"))
    )
    (comp (ref "LED1016")
      (value "LED0603")
      (footprint "eagle-import:LED-0603")
      (libsource (lib "eagle-import") (part "LED0603"))
    )
    (comp (ref "LED1017")
      (value "LED0603")
      (footprint "eagle-import:LED-0603")
      (libsource (lib "eagle-import") (part "LED0603"))
    )
    (comp (ref "LED1018")
      (value "LED0603")
      (footprint "eagle-import:LED-0603")
      (libsource (lib "eagle-import") (part "LED0603"))
    )
    (comp (ref "R1001")
      (value "15Ω")
      (footprint "eagle-import:0603-RES")
      (libsource (lib "eagle-import") (part "RESISTOR0603_RES"))
    )
    (comp (ref "R1002")
      (value "15Ω")
      (footprint "eagle-import:0603-RES")
      (libsource (lib "eagle-import") (part "RESISTOR0603_RES"))
    )
    (comp (ref "R1003")
      (value "15Ω")
      (footprint "eagle-import:0603-RES")
      (libsource (lib "eagle-import") (part "RESISTOR0603_RES"))
    )
    (comp (ref "R1004")
      (value "15Ω")
      (footprint "eagle-import:0603-RES")
      (libsource (lib "eagle-import") (part "RESISTOR0603_RES"))
    )
    (comp (ref "R1005")
      (value "15Ω")
      (footprint "eagle-import:0603-RES")
      (libsource (lib "eagle-import") (part "RESISTOR0603_RES"))
    )
    (comp (ref "R1006")
      (value "15Ω")
      (footprint "eagle-import:0603-RES")
      (libsource (lib "eagle-import") (part "RESISTOR0603_RES"))
    )
    (comp (ref "R1007")
      (value "15Ω")
      (footprint "eagle-import:0603-RES")
      (libsource (lib "eagle-import") (part "RESISTOR0603_RES"))
    )
    (comp (ref "R1008")
      (value "15Ω")
      (footprint "eagle-import:0603-RES")
      (libsource (lib "eagle-import") (part "RESISTOR0603_RES"))
    )
    (comp (ref "R1009")
      (value "15Ω")
      (footprint "eagle-import:0603-RES")
      (libsource (lib "eagle-import") (part "RESISTOR0603_RES"))
    )
    (comp (ref "R1010")
      (value "15Ω")
      (footprint "eagle-import:0603-RES")
      (libsource (lib "eagle-import") (part "RESISTOR0603_RES"))
    )
    (comp (ref "R1011")
      (value "15Ω")
      (footprint "eagle-import:0603-RES")
      (libsource (lib "eagle-import") (part "RESISTOR0603_RES"))
    )
    (comp (ref "R1012")
      (value "15Ω")
      (footprint "eagle-import:0603-RES")
      (libsource (lib "eagle-import") (part "RESISTOR0603_RES"))
    )
    (comp (ref "R1013")
      (value "15Ω")
      (footprint "eagle-import:0603-RES")
      (libsource (lib "eagle-import") (part "RESISTOR0603_RES"))
    )
    (comp (ref "R1014")
      (value "15Ω")
      (footprint "eagle-import:0603-RES")
      (libsource (lib "eagle-import") (part "RESISTOR0603_RES"))
    )
    (comp (ref "R1015")
      (value "15Ω")
      (footprint "eagle-import:0603-RES")
      (libsource (lib "eagle-import") (part "RESISTOR0603_RES"))
    )
    (comp (ref "R1016")
      (value "15Ω")
      (footprint "eagle-import:0603-RES")
      (libsource (lib "eagle-import") (part "RESISTOR0603_RES"))
    )
    (comp (ref "R1017")
      (value "15Ω")
      (footprint "eagle-import:0603-RES")
      (libsource (lib "eagle-import") (part "RESISTOR0603_RES"))
    )
    (comp (ref "R1018")
      (value "15Ω")
      (footprint "eagle-import:0603-RES")
      (libsource (lib "eagle-import") (part "RESISTOR0603_RES"))
    )
    (comp (ref "TP1")
      (value "TEST_POINT_0.040IN")
      (footprint "eagle-import:TESTPOINT_0.040IN")
      (libsource (lib "eagle-import") (part "TEST_POINT_0.040IN"))
    )
    (comp (ref "TP2")
      (value "TEST_POINT_0.040IN")
      (footprint "eagle-import:TESTPOINT_0.040IN")
      (libsource (lib "eagle-import") (part "TEST_POINT_0.040IN"))
    )
    (comp (ref "TP3")
      (value "TEST_POINT_0.040IN")
      (footprint "eagle-import:TESTPOINT_0.040IN")
      (libsource (lib "eagle-import") (part "TEST_POINT_0.040IN"))
    )
    (comp (ref "TP4")
      (value "TEST_POINT_0.040IN")
      (footprint "eagle-import:TESTPOINT_0.040IN")
      (libsource (lib "eagle-import") (part "TEST_POINT_0.040IN"))
    )
    (comp (ref "TP5")
      (value "TEST_POINT_0.040IN")
      (footprint "eagle-import:TESTPOINT_0.040IN")
      (libsource (lib "eagle-import") (part "TEST_POINT_0.040IN"))
    )
    (comp (ref "TP6")
      (value "TEST_POINT_0.040IN")
      (footprint "eagle-import:TESTPOINT_0.040IN")
      (libsource (lib "eagle-import") (part "TEST_POINT_0.040IN"))
    )
    (comp (ref "TP7")
      (value "TEST_POINT_0.040IN")
      (footprint "eagle-import:TESTPOINT_0.040IN")
      (libsource (lib "eagle-import") (part "TEST_POINT_0.040IN"))
    )
    (comp (ref "TP8")
      (value "TEST_POINT_0.040IN")
      (footprint "eagle-import:TESTPOINT_0.040IN")
      (libsource (lib "eagle-import") (part "TEST_POINT_0.040IN"))
    )
    (comp (ref "TP9")
      (value "TEST_POINT_0.040IN")
      (footprint "eagle-import:TESTPOINT_0.040IN")
      (libsource (lib "eagle-import") (part "TEST_POINT_0.040IN"))
    )
    (comp (ref "TP10")
      (value "TEST_POINT_0.040IN")
      (footprint "eagle-import:TESTPOINT_0.040IN")
      (libsource (lib "eagle-import") (part "TEST_POINT_0.040IN"))
    )
    (comp (ref "TP11")
      (value "TEST_POINT_0.040IN")
      (footprint "eagle-import:TESTPOINT_0.040IN")
      (libsource (lib "eagle-import") (part "TEST_POINT_0.040IN"))
    )
    (comp (ref "TP12")
      (value "TEST_POINT_0.040IN")
      (footprint "eagle-import:TESTPOINT_0.040IN")
      (libsource (lib "eagle-import") (part "TEST_POINT_0.040IN"))
    )
    (comp (ref "TP13")
      (value "TEST_POINT_0.040IN")
      (footprint "eagle-import:TESTPOINT_0.040IN")
      (libsource (lib "eagle-import") (part "TEST_POINT_0.040IN"))
    )
    (comp (ref "TP14")
      (value "TEST_POINT_0.040IN")
      (footprint "eagle-import:TESTPOINT_0.040IN")
      (libsource (lib "eagle-import") (part "TEST_POINT_0.040IN"))
    )
    (comp (ref "TP15")
      (value "TEST_POINT_0.040IN")
      (footprint "eagle-import:TESTPOINT_0.040IN")
      (libsource (lib "eagle-import") (part "TEST_POINT_0.040IN"))
    )
    (comp (ref "TP16")
      (value "TEST_POINT_0.040IN")
      (footprint "eagle-import:TESTPOINT_0.040IN")
      (libsource (lib "eagle-import") (part "TEST_POINT_0.040IN"))
    )
    (comp (ref "TP17")
      (value "TEST_POINT_0.040IN")
      (footprint "eagle-import:TESTPOINT_0.040IN")
      (libsource (lib "eagle-import") (part "TEST_POINT_0.040IN"))
    )
    (comp (ref "TP18")
      (value "TEST_POINT_0.040IN")
      (footprint "eagle-import:TESTPOINT_0.040IN")
      (libsource (lib "eagle-import") (part "TEST_POINT_0.040IN"))
    )
    (comp (ref "TP19")
      (value "TEST_POINT_0.040IN")
      (footprint "eagle-import:TESTPOINT_0.040IN")
      (libsource (lib "eagle-import") (part "TEST_POINT_0.040IN"))
    )
    (comp (ref "TP20")
      (value "TEST_POINT_0.040IN")
      (footprint "eagle-import:TESTPOINT_0.040IN")
      (libsource (lib "eagle-import") (part "TEST_POINT_0.040IN"))
    )
    (comp (ref "TP21")
      (value "TEST_POINT_0.040IN")
      (footprint "eagle-import:TESTPOINT_0.040IN")
      (libsource (lib "eagle-import") (part "TEST_POINT_0.040IN"))
    )
    (comp (ref "TP22")
      (value "TEST_POINT_0.040IN")
      (footprint "eagle-import:TESTPOINT_0.040IN")
      (libsource (lib "eagle-import") (part "TEST_POINT_0.040IN"))
    )
    (comp (ref "TP23")
      (value "TEST_POINT_0.040IN")
      (footprint "eagle-import:TESTPOINT_0.040IN")
      (libsource (lib "eagle-import") (part "TEST_POINT_0.040IN"))
    )
    (comp (ref "TP24")
      (value "TEST_POINT_0.040IN")
      (footprint "eagle-import:TESTPOINT_0.040IN")
      (libsource (lib "eagle-import") (part "TEST_POINT_0.040IN"))
    )
    (comp (ref "TP25")
      (value "TEST_POINT_0.040IN")
      (footprint "eagle-import:TESTPOINT_0.040IN")
      (libsource (lib "eagle-import") (part "TEST_POINT_0.040IN"))
    )
    (comp (ref "TP26")
      (value "TEST_POINT_0.040IN")
      (footprint "eagle-import:TESTPOINT_0.040IN")
      (libsource (lib "eagle-import") (part "TEST_POINT_0.040IN"))
    )
    (comp (ref "TP27")
      (value "TEST_POINT_0.040IN")
      (footprint "eagle-import:TESTPOINT_0.040IN")
      (libsource (lib "eagle-import") (part "TEST_POINT_0.040IN"))
    )
    (comp (ref "TP28")
      (value "TEST_POINT_0.040IN")
      (footprint "eagle-import:TESTPOINT_0.040IN")
      (libsource (lib "eagle-import") (part "TEST_POINT_0.040IN"))
    )
    (comp (ref "TP29")
      (value "TEST_POINT_0.040IN")
      (footprint "eagle-import:TESTPOINT_0.040IN")
      (libsource (lib "eagle-import") (part "TEST_POINT_0.040IN"))
    )
    (comp (ref "TP30")
      (value "TEST_POINT_0.040IN")
      (footprint "eagle-import:TESTPOINT_0.040IN")
      (libsource (lib "eagle-import") (part "TEST_POINT_0.040IN"))
    )
    (comp (ref "TP31")
      (value "TEST_POINT_0.040IN")
      (footprint "eagle-import:TESTPOINT_0.040IN")
      (libsource (lib "eagle-import") (part "TEST_POINT_0.040IN"))
    )
    (comp (ref "TP32")
      (value "TEST_POINT_0.040IN")
      (footprint "eagle-import:TESTPOINT_0.040IN")
      (libsource (lib "eagle-import") (part "TEST_POINT_0.040IN"))
    )
    (comp (ref "TP33")
      (value "TEST_POINT_0.040IN")
      (footprint "eagle-import:TESTPOINT_0.040IN")
      (libsource (lib "eagle-import") (part "TEST_POINT_0.040IN"))
    )
    (comp (ref "TP34")
      (value "TEST_POINT_0.040IN")
      (footprint "eagle-import:TESTPOINT_0.040IN")
      (libsource (lib "eagle-import") (part "TEST_POINT_0.040IN"))
    )
    (comp (ref "TP35")
      (value "TEST_POINT_0.040IN")
      (footprint "eagle-import:TESTPOINT_0.040IN")
      (libsource (lib "eagle-import") (part "TEST_POINT_0.040IN"))
    )
    (comp (ref "TP36")
      (value "TEST_POINT_0.040IN")
      (footprint "eagle-import:TESTPOINT_0.040IN")
      (libsource (lib "eagle-import") (part "TEST_POINT_0.040IN"))
    )
    (comp (ref "TP37")
      (value "TEST_POINT_0.040IN")
      (footprint "eagle-import:TESTPOINT_0.040IN")
      (libsource (lib "eagle-import") (part "TEST_POINT_0.040IN"))
    )
    (comp (ref "TP38")
      (value "TEST_POINT_0.040IN")
      (footprint "eagle-import:TESTPOINT_0.040IN")
      (libsource (lib "eagle-import") (part "TEST_POINT_0.040IN"))
    )
    (comp (ref "TP39")
      (value "TEST_POINT_0.040IN")
      (footprint "eagle-import:TESTPOINT_0.040IN")
      (libsource (lib "eagle-import") (part "TEST_POINT_0.040IN"))
    )
    (comp (ref "TP40")
      (value "TEST_POINT_0.040IN")
      (footprint "eagle-import:TESTPOINT_0.040IN")
      (libsource (lib "eagle-import") (part "TEST_POINT_0.040IN"))
    )
    (comp (ref "TP41")
      (value "TEST_POINT_0.040IN")
      (footprint "eagle-import:TESTPOINT_0.040IN")
      (libsource (lib "eagle-import") (part "TEST_POINT_0.040IN"))
    )
    (comp (ref "TP42")
      (value "TEST_POINT_0.040IN")
      (footprint "eagle-import:TESTPOINT_0.040IN")
      (libsource (lib "eagle-import") (part "TEST_POINT_0.040IN"))
    )
    (comp (ref "TP43")
      (value "TEST_POINT_0.040IN")
      (footprint "eagle-import:TESTPOINT_0.040IN")
      (libsource (lib "eagle-import") (part "TEST_POINT_0.040IN"))
    )
    (comp (ref "TP1001")
      (value "TEST_POINT_0.040IN")
      (footprint "eagle-import:TESTPOINT_0.040IN")
      (libsource (lib "eagle-import") (part "TEST_POINT_0.040IN"))
    )
    (comp (ref "TP1002")
      (value "TEST_POINT_0.040IN")
      (footprint "eagle-import:TESTPOINT_0.040IN")
      (libsource (lib "eagle-import") (part "TEST_POINT_0.040IN"))
    )
    (comp (ref "TP1003")
      (value "TEST_POINT_0.040IN")
      (footprint "eagle-import:TESTPOINT_0.040IN")
      (libsource (lib "eagle-import") (part "TEST_POINT_0.040IN"))
    )
    (comp (ref "TP1004")
      (value "TEST_POINT_0.040IN")
      (footprint "eagle-import:TESTPOINT_0.040IN")
      (libsource (lib "eagle-import") (part "TEST_POINT_0.040IN"))
    )
    (comp (ref "TP1005")
      (value "TEST_POINT_0.040IN")
      (footprint "eagle-import:TESTPOINT_0.040IN")
      (libsource (lib "eagle-import") (part "TEST_POINT_0.040IN"))
    )
    (comp (ref "TP1006")
      (value "TEST_POINT_0.040IN")
      (footprint "eagle-import:TESTPOINT_0.040IN")
      (libsource (lib "eagle-import") (part "TEST_POINT_0.040IN"))
    )
    (comp (ref "TP1007")
      (value "TEST_POINT_0.040IN")
      (footprint "eagle-import:TESTPOINT_0.040IN")
      (libsource (lib "eagle-import") (part "TEST_POINT_0.040IN"))
    )
    (comp (ref "TP1008")
      (value "TEST_POINT_0.040IN")
      (footprint "eagle-import:TESTPOINT_0.040IN")
      (libsource (lib "eagle-import") (part "TEST_POINT_0.040IN"))
    )
    (comp (ref "TP1009")
      (value "TEST_POINT_0.040IN")
      (footprint "eagle-import:TESTPOINT_0.040IN")
      (libsource (lib "eagle-import") (part "TEST_POINT_0.040IN"))
    )
    (comp (ref "TP1010")
      (value "TEST_POINT_0.040IN")
      (footprint "eagle-import:TESTPOINT_0.040IN")
      (libsource (lib "eagle-import") (part "TEST_POINT_0.040IN"))
    )
    (comp (ref "TP1011")
      (value "TEST_POINT_0.040IN")
      (footprint "eagle-import:TESTPOINT_0.040IN")
      (libsource (lib "eagle-import") (part "TEST_POINT_0.040IN"))
    )
    (comp (ref "TP1012")
      (value "TEST_POINT_0.040IN")
      (footprint "eagle-import:TESTPOINT_0.040IN")
      (libsource (lib "eagle-import") (part "TEST_POINT_0.040IN"))
    )
    (comp (ref "TP1013")
      (value "TEST_POINT_0.040IN")
      (footprint "eagle-import:TESTPOINT_0.040IN")
      (libsource (lib "eagle-import") (part "TEST_POINT_0.040IN"))
    )
    (comp (ref "TP1014")
      (value "TEST_POINT_0.040IN")
      (footprint "eagle-import:TESTPOINT_0.040IN")
      (libsource (lib "eagle-import") (part "TEST_POINT_0.040IN"))
    )
    (comp (ref "TP1015")
      (value "TEST_POINT_0.040IN")
      (footprint "eagle-import:TESTPOINT_0.040IN")
      (libsource (lib "eagle-import") (part "TEST_POINT_0.040IN"))
    )
    (comp (ref "TP1016")
      (value "TEST_POINT_0.040IN")
      (footprint "eagle-import:TESTPOINT_0.040IN")
      (libsource (lib "eagle-import") (part "TEST_POINT_0.040IN"))
    )
    (comp (ref "TP1017")
      (value "TEST_POINT_0.040IN")
      (footprint "eagle-import:TESTPOINT_0.040IN")
      (libsource (lib "eagle-import") (part "TEST_POINT_0.040IN"))
    )
    (comp (ref "TP1018")
      (value "TEST_POINT_0.040IN")
      (footprint "eagle-import:TESTPOINT_0.040IN")
      (libsource (lib "eagle-import") (part "TEST_POINT_0.040IN"))
    )
    (comp (ref "C1")
      (value "22pF, 5% tol")
      (footprint "eagle-import:0603_CAP")
      (libsource (lib "eagle-import") (part "CAPACITOR0603_CAP"))
    )
    (comp (ref "C2")
      (value "22pF, 5% tol")
      (footprint "eagle-import:0603_CAP")
      (libsource (lib "eagle-import") (part "CAPACITOR0603_CAP"))
    )
    (comp (ref "C51")
      (value "100nF")
      (footprint "eagle-import:0603_CAP")
      (libsource (lib "eagle-import") (part "CAPACITOR0603_CAP"))
    )
    (comp (ref "C88")
      (value "100nF")
      (footprint "eagle-import:0603_CAP")
      (libsource (lib "eagle-import") (part "CAPACITOR0603_CAP"))
    )
    (comp (ref "C96")
      (value "4.7uF")
      (footprint "eagle-import:0603_CAP")
      (libsource (lib "eagle-import") (part "CAPACITOR0603_CAP"))
    )
    (comp (ref "R25")
      (value "1.5kΩ")
      (footprint "eagle-import:0603-RES")
      (libsource (lib "eagle-import") (part "RESISTOR0603_RES"))
    )
    (comp (ref "R26")
      (value "1.5kΩ")
      (footprint "eagle-import:0603-RES")
      (libsource (lib "eagle-import") (part "RESISTOR0603_RES"))
    )
    (comp (ref "R51")
      (value "10kΩ")
      (footprint "eagle-import:0603-RES")
      (libsource (lib "eagle-import") (part "RESISTOR0603_RES"))
    )
    (comp (ref "R52")
      (value "10kΩ")
      (footprint "eagle-import:0603-RES")
      (libsource (lib "eagle-import") (part "RESISTOR0603_RES"))
    )
    (comp (ref "R65")
      (value "15kΩ")
      (footprint "eagle-import:0603-RES")
      (libsource (lib "eagle-import") (part "RESISTOR0603_RES"))
    )
    (comp (ref "R66")
      (value "15kΩ")
      (footprint "eagle-import:0603-RES")
      (libsource (lib "eagle-import") (part "RESISTOR0603_RES"))
    )
    (comp (ref "U1")
      (value "TUSB2077A")
      (footprint "eagle-import:LQFP-48")
      (libsource (lib "eagle-import") (part "TUSB2077A"))
    )
    (comp (ref "U32")
      (value "MCP23008QFN")
      (footprint "eagle-import:QFN-20-4MM")
      (libsource (lib "eagle-import") (part "MCP23008QFN"))
    )
    (comp (ref "U33")
      (value "NCP301LSN30")
      (footprint "eagle-import:SOT23-5")
      (libsource (lib "eagle-import") (part "NCP301LSN30"))
    )
    (comp (ref "Y1")
      (value "ABMM")
      (footprint "eagle-import:ABMM")
      (libsource (lib "eagle-import") (part "ABMM"))
    )
    (comp (ref "H1")
      (value "MOUNT-PAD-ROUND#4")
      (footprint "eagle-import:#4-PAD")
      (libsource (lib "eagle-import") (part "MOUNT-PAD-ROUND#4"))
    )
    (comp (ref "H2")
      (value "MOUNT-PAD-ROUND#4")
      (footprint "eagle-import:#4-PAD")
      (libsource (lib "eagle-import") (part "MOUNT-PAD-ROUND#4"))
    )
    (comp (ref "H3")
      (value "MOUNT-PAD-ROUND#4")
      (footprint "eagle-import:#4-PAD")
      (libsource (lib "eagle-import") (part "MOUNT-PAD-ROUND#4"))
    )
    (comp (ref "H4")
      (value "MOUNT-PAD-ROUND#4")
      (footprint "eagle-import:#4-PAD")
      (libsource (lib "eagle-import") (part "MOUNT-PAD-ROUND#4"))
    )
    (comp (ref "H5")
      (value "MOUNT-PAD-ROUND#4")
      (footprint "eagle-import:#4-PAD")
      (libsource (lib "eagle-import") (part "MOUNT-PAD-ROUND#4"))
    )
    (comp (ref "H6")
      (value "MOUNT-PAD-ROUND#4")
      (footprint "eagle-import:#4-PAD")
      (libsource (lib "eagle-import") (part "MOUNT-PAD-ROUND#4"))
    )
    (comp (ref "H7")
      (value "MOUNT-PAD-ROUND#4")
      (footprint "eagle-import:#4-PAD")
      (libsource (lib "eagle-import") (part "MOUNT-PAD-ROUND#4"))
    )
    (comp (ref "H8")
      (value "MOUNT-PAD-ROUND#4")
      (footprint "eagle-import:#4-PAD")
      (libsource (lib "eagle-import") (part "MOUNT-PAD-ROUND#4"))
    )
    (comp (ref "H9")
      (value "MOUNT-PAD-ROUND#4")
      (footprint "eagle-import:#4-PAD")
      (libsource (lib "eagle-import") (part "MOUNT-PAD-ROUND#4"))
    )
    (comp (ref "H10")
      (value "MOUNT-PAD-ROUND#4")
      (footprint "eagle-import:#4-PAD")
      (libsource (lib "eagle-import") (part "MOUNT-PAD-ROUND#4"))
    )
    (comp (ref "H11")
      (value "MOUNT-PAD-ROUND#4")
      (footprint "eagle-import:#4-PAD")
      (libsource (lib "eagle-import") (part "MOUNT-PAD-ROUND#4"))
    )
    (comp (ref "H12")
      (value "MOUNT-PAD-ROUND#4")
      (footprint "eagle-import:#4-PAD")
      (libsource (lib "eagle-import") (part "MOUNT-PAD-ROUND#4"))
    )
    (comp (ref "H13")
      (value "MOUNT-PAD-ROUND#4")
      (footprint "eagle-import:#4-PAD")
      (libsource (lib "eagle-import") (part "MOUNT-PAD-ROUND#4"))
    )
    (comp (ref "H14")
      (value "MOUNT-PAD-ROUND#4")
      (footprint "eagle-import:#4-PAD")
      (libsource (lib "eagle-import") (part "MOUNT-PAD-ROUND#4"))
    )
    (comp (ref "H15")
      (value "MOUNT-PAD-ROUND#4")
      (footprint "eagle-import:#4-PAD")
      (libsource (lib "eagle-import") (part "MOUNT-PAD-ROUND#4"))
    )
    (comp (ref "H16")
      (value "MOUNT-PAD-ROUND#4")
      (footprint "eagle-import:#4-PAD")
      (libsource (lib "eagle-import") (part "MOUNT-PAD-ROUND#4"))
    )
    (comp (ref "H17")
      (value "MOUNT-PAD-ROUND#4")
      (footprint "eagle-import:#4-PAD")
      (libsource (lib "eagle-import") (part "MOUNT-PAD-ROUND#4"))
    )
    (comp (ref "H18")
      (value "MOUNT-PAD-ROUND#4")
      (footprint "eagle-import:#4-PAD")
      (libsource (lib "eagle-import") (part "MOUNT-PAD-ROUND#4"))
    )
    (comp (ref "H19")
      (value "MOUNT-PAD-ROUND#4")
      (footprint "eagle-import:#4-PAD")
      (libsource (lib "eagle-import") (part "MOUNT-PAD-ROUND#4"))
    )
    (comp (ref "H20")
      (value "MOUNT-PAD-ROUND#4")
      (footprint "eagle-import:#4-PAD")
      (libsource (lib "eagle-import") (part "MOUNT-PAD-ROUND#4"))
    )
    (comp (ref "J3")
      (value "BACKPLANE_CONTROLLER_MODULE")
      (footprint "eagle-import:BACKPLANE_MODULE_20PIN_10PIN")
      (libsource (lib "eagle-import") (part "BACKPLANE_CONTROLLER_MODULE"))
    )
    (comp (ref "J4")
      (value "BACKPLANE_POWER_MODULE")
      (footprint "eagle-import:BACKPLANE_MODULE_20PIN")
      (libsource (lib "eagle-import") (part "BACKPLANE_POWER_MODULE"))
    )
    (comp (ref "J8")
      (value "SCREW-TERMINAL_2_0.100")
      (footprint "eagle-import:CONN_BLOCK_2")
      (libsource (lib "eagle-import") (part "SCREW-TERMINAL_2_0.100"))
    )
    (comp (ref "J9")
      (value "SCREW-TERMINAL_2_0.100")
      (footprint "eagle-import:CONN_BLOCK_2")
      (libsource (lib "eagle-import") (part "SCREW-TERMINAL_2_0.100"))
    )
    (comp (ref "JP1")
      (value "FIDUCIAL1X2")
      (footprint "eagle-import:FIDUCIAL-1X2")
      (libsource (lib "eagle-import") (part "FIDUCIAL1X2"))
    )
    (comp (ref "JP2")
      (value "FIDUCIAL1X2")
      (footprint "eagle-import:FIDUCIAL-1X2")
      (libsource (lib "eagle-import") (part "FIDUCIAL1X2"))
    )
    (comp (ref "JP3")
      (value "FIDUCIAL1X2")
      (footprint "eagle-import:FIDUCIAL-1X2")
      (libsource (lib "eagle-import") (part "FIDUCIAL1X2"))
    )
    (comp (ref "JP4")
      (value "FIDUCIAL1X2")
      (footprint "eagle-import:FIDUCIAL-1X2")
      (libsource (lib "eagle-import") (part "FIDUCIAL1X2"))
    )
    (comp (ref "JP5")
      (value "FIDUCIAL1X2")
      (footprint "eagle-import:FIDUCIAL-1X2")
      (libsource (lib "eagle-import") (part "FIDUCIAL1X2"))
    )
    (comp (ref "JP6")
      (value "FIDUCIAL1X2")
      (footprint "eagle-import:FIDUCIAL-1X2")
      (libsource (lib "eagle-import") (part "FIDUCIAL1X2"))
    )
    (comp (ref "LOGO1")
      (value "UMICH_SOLID_GIANT")
      (footprint "eagle-import:UMICH_SOLID_1000MIL")
      (libsource (lib "eagle-import") (part "UMICH_SOLID_GIANT"))
    )
    (comp (ref "LOGO8")
      (value "UMICH_SOLID_MEDIUM")
      (footprint "eagle-import:UMICH_SOLID_200MIL")
      (libsource (lib "eagle-import") (part "UMICH_SOLID_MEDIUM"))
    )
    (comp (ref "LOGO9")
      (value "UMICH_SOLID_MEDIUM")
      (footprint "eagle-import:UMICH_SOLID_200MIL")
      (libsource (lib "eagle-import") (part "UMICH_SOLID_MEDIUM"))
    )
    (comp (ref "R27")
      (value "1.5kΩ")
      (footprint "eagle-import:0603-RES")
      (libsource (lib "eagle-import") (part "RESISTOR0603_RES"))
    )
    (comp (ref "R46")
      (value "10kΩ")
      (footprint "eagle-import:0603-RES")
      (libsource (lib "eagle-import") (part "RESISTOR0603_RES"))
    )
    (comp (ref "R47")
      (value "10kΩ")
      (footprint "eagle-import:0603-RES")
      (libsource (lib "eagle-import") (part "RESISTOR0603_RES"))
    )
    (comp (ref "R48")
      (value "10kΩ")
      (footprint "eagle-import:0603-RES")
      (libsource (lib "eagle-import") (part "RESISTOR0603_RES"))
    )
    (comp (ref "R49")
      (value "10kΩ")
      (footprint "eagle-import:0603-RES")
      (libsource (lib "eagle-import") (part "RESISTOR0603_RES"))
    )
    (comp (ref "R50")
      (value "10kΩ")
      (footprint "eagle-import:0603-RES")
      (libsource (lib "eagle-import") (part "RESISTOR0603_RES"))
    )
    (comp (ref "C15")
      (value "100nF")
      (footprint "eagle-import:0603_CAP")
      (libsource (lib "eagle-import") (part "CAPACITOR0603_CAP"))
    )
    (comp (ref "C16")
      (value "100nF")
      (footprint "eagle-import:0603_CAP")
      (libsource (lib "eagle-import") (part "CAPACITOR0603_CAP"))
    )
    (comp (ref "C17")
      (value "100nF")
      (footprint "eagle-import:0603_CAP")
      (libsource (lib "eagle-import") (part "CAPACITOR0603_CAP"))
    )
    (comp (ref "C18")
      (value "100nF")
      (footprint "eagle-import:0603_CAP")
      (libsource (lib "eagle-import") (part "CAPACITOR0603_CAP"))
    )
    (comp (ref "C19")
      (value "100nF")
      (footprint "eagle-import:0603_CAP")
      (libsource (lib "eagle-import") (part "CAPACITOR0603_CAP"))
    )
    (comp (ref "C20")
      (value "100nF")
      (footprint "eagle-import:0603_CAP")
      (libsource (lib "eagle-import") (part "CAPACITOR0603_CAP"))
    )
    (comp (ref "C21")
      (value "100nF")
      (footprint "eagle-import:0603_CAP")
      (libsource (lib "eagle-import") (part "CAPACITOR0603_CAP"))
    )
    (comp (ref "C22")
      (value "100nF")
      (footprint "eagle-import:0603_CAP")
      (libsource (lib "eagle-import") (part "CAPACITOR0603_CAP"))
    )
    (comp (ref "C23")
      (value "100nF")
      (footprint "eagle-import:0603_CAP")
      (libsource (lib "eagle-import") (part "CAPACITOR0603_CAP"))
    )
    (comp (ref "C24")
      (value "100nF")
      (footprint "eagle-import:0603_CAP")
      (libsource (lib "eagle-import") (part "CAPACITOR0603_CAP"))
    )
    (comp (ref "C25")
      (value "100nF")
      (footprint "eagle-import:0603_CAP")
      (libsource (lib "eagle-import") (part "CAPACITOR0603_CAP"))
    )
    (comp (ref "C26")
      (value "100nF")
      (footprint "eagle-import:0603_CAP")
      (libsource (lib "eagle-import") (part "CAPACITOR0603_CAP"))
    )
    (comp (ref "C82")
      (value "100nF")
      (footprint "eagle-import:0603_CAP")
      (libsource (lib "eagle-import") (part "CAPACITOR0603_CAP"))
    )
    (comp (ref "C83")
      (value "100nF")
      (footprint "eagle-import:0603_CAP")
      (libsource (lib "eagle-import") (part "CAPACITOR0603_CAP"))
    )
    (comp (ref "C84")
      (value "100nF")
      (footprint "eagle-import:0603_CAP")
      (libsource (lib "eagle-import") (part "CAPACITOR0603_CAP"))
    )
    (comp (ref "C85")
      (value "100nF")
      (footprint "eagle-import:0603_CAP")
      (libsource (lib "eagle-import") (part "CAPACITOR0603_CAP"))
    )
    (comp (ref "C86")
      (value "100nF")
      (footprint "eagle-import:0603_CAP")
      (libsource (lib "eagle-import") (part "CAPACITOR0603_CAP"))
    )
    (comp (ref "C87")
      (value "100nF")
      (footprint "eagle-import:0603_CAP")
      (libsource (lib "eagle-import") (part "CAPACITOR0603_CAP"))
    )
    (comp (ref "C90")
      (value "4.7uF")
      (footprint "eagle-import:0603_CAP")
      (libsource (lib "eagle-import") (part "CAPACITOR0603_CAP"))
    )
    (comp (ref "C91")
      (value "4.7uF")
      (footprint "eagle-import:0603_CAP")
      (libsource (lib "eagle-import") (part "CAPACITOR0603_CAP"))
    )
    (comp (ref "C92")
      (value "4.7uF")
      (footprint "eagle-import:0603_CAP")
      (libsource (lib "eagle-import") (part "CAPACITOR0603_CAP"))
    )
    (comp (ref "C93")
      (value "4.7uF")
      (footprint "eagle-import:0603_CAP")
      (libsource (lib "eagle-import") (part "CAPACITOR0603_CAP"))
    )
    (comp (ref "C94")
      (value "4.7uF")
      (footprint "eagle-import:0603_CAP")
      (libsource (lib "eagle-import") (part "CAPACITOR0603_CAP"))
    )
    (comp (ref "C95")
      (value "4.7uF")
      (footprint "eagle-import:0603_CAP")
      (libsource (lib "eagle-import") (part "CAPACITOR0603_CAP"))
    )
    (comp (ref "R34")
      (value "10kΩ")
      (footprint "eagle-import:0603-RES")
      (libsource (lib "eagle-import") (part "RESISTOR0603_RES"))
    )
    (comp (ref "R35")
      (value "10kΩ")
      (footprint "eagle-import:0603-RES")
      (libsource (lib "eagle-import") (part "RESISTOR0603_RES"))
    )
    (comp (ref "R36")
      (value "10kΩ")
      (footprint "eagle-import:0603-RES")
      (libsource (lib "eagle-import") (part "RESISTOR0603_RES"))
    )
    (comp (ref "R37")
      (value "10kΩ")
      (footprint "eagle-import:0603-RES")
      (libsource (lib "eagle-import") (part "RESISTOR0603_RES"))
    )
    (comp (ref "R38")
      (value "10kΩ")
      (footprint "eagle-import:0603-RES")
      (libsource (lib "eagle-import") (part "RESISTOR0603_RES"))
    )
    (comp (ref "R39")
      (value "10kΩ")
      (footprint "eagle-import:0603-RES")
      (libsource (lib "eagle-import") (part "RESISTOR0603_RES"))
    )
    (comp (ref "R40")
      (value "10kΩ")
      (footprint "eagle-import:0603-RES")
      (libsource (lib "eagle-import") (part "RESISTOR0603_RES"))
    )
    (comp (ref "R41")
      (value "10kΩ")
      (footprint "eagle-import:0603-RES")
      (libsource (lib "eagle-import") (part "RESISTOR0603_RES"))
    )
    (comp (ref "R42")
      (value "10kΩ")
      (footprint "eagle-import:0603-RES")
      (libsource (lib "eagle-import") (part "RESISTOR0603_RES"))
    )
    (comp (ref "R43")
      (value "10kΩ")
      (footprint "eagle-import:0603-RES")
      (libsource (lib "eagle-import") (part "RESISTOR0603_RES"))
    )
    (comp (ref "R44")
      (value "10kΩ")
      (footprint "eagle-import:0603-RES")
      (libsource (lib "eagle-import") (part "RESISTOR0603_RES"))
    )
    (comp (ref "R45")
      (value "10kΩ")
      (footprint "eagle-import:0603-RES")
      (libsource (lib "eagle-import") (part "RESISTOR0603_RES"))
    )
    (comp (ref "S1")
      (value "SIP3240X")
      (footprint "eagle-import:TDFN4")
      (libsource (lib "eagle-import") (part "SIP3240X"))
    )
    (comp (ref "S2")
      (value "SIP3240X")
      (footprint "eagle-import:TDFN4")
      (libsource (lib "eagle-import") (part "SIP3240X"))
    )
    (comp (ref "S3")
      (value "SIP3240X")
      (footprint "eagle-import:TDFN4")
      (libsource (lib "eagle-import") (part "SIP3240X"))
    )
    (comp (ref "S4")
      (value "SIP3240X")
      (footprint "eagle-import:TDFN4")
      (libsource (lib "eagle-import") (part "SIP3240X"))
    )
    (comp (ref "S5")
      (value "SIP3240X")
      (footprint "eagle-import:TDFN4")
      (libsource (lib "eagle-import") (part "SIP3240X"))
    )
    (comp (ref "S6")
      (value "SIP3240X")
      (footprint "eagle-import:TDFN4")
      (libsource (lib "eagle-import") (part "SIP3240X"))
    )
    (comp (ref "U2")
      (value "FXMA2102")
      (footprint "eagle-import:UMLP-8")
      (libsource (lib "eagle-import") (part "FXMA2102"))
    )
    (comp (ref "U3")
      (value "FXMA2102")
      (footprint "eagle-import:UMLP-8")
      (libsource (lib "eagle-import") (part "FXMA2102"))
    )
    (comp (ref "U4")
      (value "FXMA2102")
      (footprint "eagle-import:UMLP-8")
      (libsource (lib "eagle-import") (part "FXMA2102"))
    )
    (comp (ref "U5")
      (value "FXMA2102")
      (footprint "eagle-import:UMLP-8")
      (libsource (lib "eagle-import") (part "FXMA2102"))
    )
    (comp (ref "U6")
      (value "FXMA2102")
      (footprint "eagle-import:UMLP-8")
      (libsource (lib "eagle-import") (part "FXMA2102"))
    )
    (comp (ref "U7")
      (value "FXMA2102")
      (footprint "eagle-import:UMLP-8")
      (libsource (lib "eagle-import") (part "FXMA2102"))
    )
    (comp (ref "C27")
      (value "100nF")
      (footprint "eagle-import:0603_CAP")
      (libsource (lib "eagle-import") (part "CAPACITOR0603_CAP"))
    )
    (comp (ref "C28")
      (value "100nF")
      (footprint "eagle-import:0603_CAP")
      (libsource (lib "eagle-import") (part "CAPACITOR0603_CAP"))
    )
    (comp (ref "C29")
      (value "100nF")
      (footprint "eagle-import:0603_CAP")
      (libsource (lib "eagle-import") (part "CAPACITOR0603_CAP"))
    )
    (comp (ref "C30")
      (value "100nF")
      (footprint "eagle-import:0603_CAP")
      (libsource (lib "eagle-import") (part "CAPACITOR0603_CAP"))
    )
    (comp (ref "C31")
      (value "100nF")
      (footprint "eagle-import:0603_CAP")
      (libsource (lib "eagle-import") (part "CAPACITOR0603_CAP"))
    )
    (comp (ref "C32")
      (value "100nF")
      (footprint "eagle-import:0603_CAP")
      (libsource (lib "eagle-import") (part "CAPACITOR0603_CAP"))
    )
    (comp (ref "C33")
      (value "100nF")
      (footprint "eagle-import:0603_CAP")
      (libsource (lib "eagle-import") (part "CAPACITOR0603_CAP"))
    )
    (comp (ref "C34")
      (value "100nF")
      (footprint "eagle-import:0603_CAP")
      (libsource (lib "eagle-import") (part "CAPACITOR0603_CAP"))
    )
    (comp (ref "C35")
      (value "100nF")
      (footprint "eagle-import:0603_CAP")
      (libsource (lib "eagle-import") (part "CAPACITOR0603_CAP"))
    )
    (comp (ref "C36")
      (value "100nF")
      (footprint "eagle-import:0603_CAP")
      (libsource (lib "eagle-import") (part "CAPACITOR0603_CAP"))
    )
    (comp (ref "C37")
      (value "100nF")
      (footprint "eagle-import:0603_CAP")
      (libsource (lib "eagle-import") (part "CAPACITOR0603_CAP"))
    )
    (comp (ref "C38")
      (value "100nF")
      (footprint "eagle-import:0603_CAP")
      (libsource (lib "eagle-import") (part "CAPACITOR0603_CAP"))
    )
    (comp (ref "C39")
      (value "100nF")
      (footprint "eagle-import:0603_CAP")
      (libsource (lib "eagle-import") (part "CAPACITOR0603_CAP"))
    )
    (comp (ref "C40")
      (value "100nF")
      (footprint "eagle-import:0603_CAP")
      (libsource (lib "eagle-import") (part "CAPACITOR0603_CAP"))
    )
    (comp (ref "C41")
      (value "100nF")
      (footprint "eagle-import:0603_CAP")
      (libsource (lib "eagle-import") (part "CAPACITOR0603_CAP"))
    )
    (comp (ref "C42")
      (value "100nF")
      (footprint "eagle-import:0603_CAP")
      (libsource (lib "eagle-import") (part "CAPACITOR0603_CAP"))
    )
    (comp (ref "C43")
      (value "100nF")
      (footprint "eagle-import:0603_CAP")
      (libsource (lib "eagle-import") (part "CAPACITOR0603_CAP"))
    )
    (comp (ref "C44")
      (value "100nF")
      (footprint "eagle-import:0603_CAP")
      (libsource (lib "eagle-import") (part "CAPACITOR0603_CAP"))
    )
    (comp (ref "C45")
      (value "100nF")
      (footprint "eagle-import:0603_CAP")
      (libsource (lib "eagle-import") (part "CAPACITOR0603_CAP"))
    )
    (comp (ref "C46")
      (value "100nF")
      (footprint "eagle-import:0603_CAP")
      (libsource (lib "eagle-import") (part "CAPACITOR0603_CAP"))
    )
    (comp (ref "C47")
      (value "100nF")
      (footprint "eagle-import:0603_CAP")
      (libsource (lib "eagle-import") (part "CAPACITOR0603_CAP"))
    )
    (comp (ref "C48")
      (value "100nF")
      (footprint "eagle-import:0603_CAP")
      (libsource (lib "eagle-import") (part "CAPACITOR0603_CAP"))
    )
    (comp (ref "C49")
      (value "100nF")
      (footprint "eagle-import:0603_CAP")
      (libsource (lib "eagle-import") (part "CAPACITOR0603_CAP"))
    )
    (comp (ref "C50")
      (value "100nF")
      (footprint "eagle-import:0603_CAP")
      (libsource (lib "eagle-import") (part "CAPACITOR0603_CAP"))
    )
    (comp (ref "U8")
      (value "SN74LVC2T45")
      (footprint "eagle-import:VFSOP-8")
      (libsource (lib "eagle-import") (part "SN74LVC2T45"))
    )
    (comp (ref "U9")
      (value "SN74LVC2T45")
      (footprint "eagle-import:VFSOP-8")
      (libsource (lib "eagle-import") (part "SN74LVC2T45"))
    )
    (comp (ref "U10")
      (value "SN74LVC2T45")
      (footprint "eagle-import:VFSOP-8")
      (libsource (lib "eagle-import") (part "SN74LVC2T45"))
    )
    (comp (ref "U11")
      (value "SN74LVC2T45")
      (footprint "eagle-import:VFSOP-8")
      (libsource (lib "eagle-import") (part "SN74LVC2T45"))
    )
    (comp (ref "U12")
      (value "SN74LVC2T45")
      (footprint "eagle-import:VFSOP-8")
      (libsource (lib "eagle-import") (part "SN74LVC2T45"))
    )
    (comp (ref "U13")
      (value "SN74LVC2T45")
      (footprint "eagle-import:VFSOP-8")
      (libsource (lib "eagle-import") (part "SN74LVC2T45"))
    )
    (comp (ref "U14")
      (value "SN74LVC2T45")
      (footprint "eagle-import:VFSOP-8")
      (libsource (lib "eagle-import") (part "SN74LVC2T45"))
    )
    (comp (ref "U15")
      (value "SN74LVC2T45")
      (footprint "eagle-import:VFSOP-8")
      (libsource (lib "eagle-import") (part "SN74LVC2T45"))
    )
    (comp (ref "U16")
      (value "SN74LVC2T45")
      (footprint "eagle-import:VFSOP-8")
      (libsource (lib "eagle-import") (part "SN74LVC2T45"))
    )
    (comp (ref "U17")
      (value "SN74LVC2T45")
      (footprint "eagle-import:VFSOP-8")
      (libsource (lib "eagle-import") (part "SN74LVC2T45"))
    )
    (comp (ref "U18")
      (value "SN74LVC2T45")
      (footprint "eagle-import:VFSOP-8")
      (libsource (lib "eagle-import") (part "SN74LVC2T45"))
    )
    (comp (ref "U19")
      (value "SN74LVC2T45")
      (footprint "eagle-import:VFSOP-8")
      (libsource (lib "eagle-import") (part "SN74LVC2T45"))
    )
    (comp (ref "C3")
      (value "22pF")
      (footprint "eagle-import:0402_CAP")
      (libsource (lib "eagle-import") (part "CAPACITOR0402_CAP"))
    )
    (comp (ref "C4")
      (value "22pF")
      (footprint "eagle-import:0402_CAP")
      (libsource (lib "eagle-import") (part "CAPACITOR0402_CAP"))
    )
    (comp (ref "C5")
      (value "22pF")
      (footprint "eagle-import:0402_CAP")
      (libsource (lib "eagle-import") (part "CAPACITOR0402_CAP"))
    )
    (comp (ref "C6")
      (value "22pF")
      (footprint "eagle-import:0402_CAP")
      (libsource (lib "eagle-import") (part "CAPACITOR0402_CAP"))
    )
    (comp (ref "C7")
      (value "22pF")
      (footprint "eagle-import:0402_CAP")
      (libsource (lib "eagle-import") (part "CAPACITOR0402_CAP"))
    )
    (comp (ref "C8")
      (value "22pF")
      (footprint "eagle-import:0402_CAP")
      (libsource (lib "eagle-import") (part "CAPACITOR0402_CAP"))
    )
    (comp (ref "C9")
      (value "22pF")
      (footprint "eagle-import:0402_CAP")
      (libsource (lib "eagle-import") (part "CAPACITOR0402_CAP"))
    )
    (comp (ref "C10")
      (value "22pF")
      (footprint "eagle-import:0402_CAP")
      (libsource (lib "eagle-import") (part "CAPACITOR0402_CAP"))
    )
    (comp (ref "C11")
      (value "22pF")
      (footprint "eagle-import:0402_CAP")
      (libsource (lib "eagle-import") (part "CAPACITOR0402_CAP"))
    )
    (comp (ref "C12")
      (value "22pF")
      (footprint "eagle-import:0402_CAP")
      (libsource (lib "eagle-import") (part "CAPACITOR0402_CAP"))
    )
    (comp (ref "C13")
      (value "22pF")
      (footprint "eagle-import:0402_CAP")
      (libsource (lib "eagle-import") (part "CAPACITOR0402_CAP"))
    )
    (comp (ref "C14")
      (value "22pF")
      (footprint "eagle-import:0402_CAP")
      (libsource (lib "eagle-import") (part "CAPACITOR0402_CAP"))
    )
    (comp (ref "C76")
      (value "100nF")
      (footprint "eagle-import:0603_CAP")
      (libsource (lib "eagle-import") (part "CAPACITOR0603_CAP"))
    )
    (comp (ref "C77")
      (value "100nF")
      (footprint "eagle-import:0603_CAP")
      (libsource (lib "eagle-import") (part "CAPACITOR0603_CAP"))
    )
    (comp (ref "C78")
      (value "100nF")
      (footprint "eagle-import:0603_CAP")
      (libsource (lib "eagle-import") (part "CAPACITOR0603_CAP"))
    )
    (comp (ref "C79")
      (value "100nF")
      (footprint "eagle-import:0603_CAP")
      (libsource (lib "eagle-import") (part "CAPACITOR0603_CAP"))
    )
    (comp (ref "C80")
      (value "100nF")
      (footprint "eagle-import:0603_CAP")
      (libsource (lib "eagle-import") (part "CAPACITOR0603_CAP"))
    )
    (comp (ref "C81")
      (value "100nF")
      (footprint "eagle-import:0603_CAP")
      (libsource (lib "eagle-import") (part "CAPACITOR0603_CAP"))
    )
    (comp (ref "D1")
      (value "SN75240-TSSOP")
      (footprint "eagle-import:TSSOP-8")
      (libsource (lib "eagle-import") (part "SN75240-TSSOP"))
    )
    (comp (ref "D2")
      (value "SN75240-TSSOP")
      (footprint "eagle-import:TSSOP-8")
      (libsource (lib "eagle-import") (part "SN75240-TSSOP"))
    )
    (comp (ref "D3")
      (value "SN75240-TSSOP")
      (footprint "eagle-import:TSSOP-8")
      (libsource (lib "eagle-import") (part "SN75240-TSSOP"))
    )
    (comp (ref "D4")
      (value "SN75240-TSSOP")
      (footprint "eagle-import:TSSOP-8")
      (libsource (lib "eagle-import") (part "SN75240-TSSOP"))
    )
    (comp (ref "R1")
      (value "27Ω")
      (footprint "eagle-import:0402_RES-HIGH_SPEED")
      (libsource (lib "eagle-import") (part "RESISTOR0402_RES-HIGH_SPEED"))
    )
    (comp (ref "R2")
      (value "27Ω")
      (footprint "eagle-import:0402_RES-HIGH_SPEED")
      (libsource (lib "eagle-import") (part "RESISTOR0402_RES-HIGH_SPEED"))
    )
    (comp (ref "R3")
      (value "27Ω")
      (footprint "eagle-import:0402_RES-HIGH_SPEED")
      (libsource (lib "eagle-import") (part "RESISTOR0402_RES-HIGH_SPEED"))
    )
    (comp (ref "R4")
      (value "27Ω")
      (footprint "eagle-import:0402_RES-HIGH_SPEED")
      (libsource (lib "eagle-import") (part "RESISTOR0402_RES-HIGH_SPEED"))
    )
    (comp (ref "R5")
      (value "27Ω")
      (footprint "eagle-import:0402_RES-HIGH_SPEED")
      (libsource (lib "eagle-import") (part "RESISTOR0402_RES-HIGH_SPEED"))
    )
    (comp (ref "R6")
      (value "27Ω")
      (footprint "eagle-import:0402_RES-HIGH_SPEED")
      (libsource (lib "eagle-import") (part "RESISTOR0402_RES-HIGH_SPEED"))
    )
    (comp (ref "R7")
      (value "27Ω")
      (footprint "eagle-import:0402_RES-HIGH_SPEED")
      (libsource (lib "eagle-import") (part "RESISTOR0402_RES-HIGH_SPEED"))
    )
    (comp (ref "R8")
      (value "27Ω")
      (footprint "eagle-import:0402_RES-HIGH_SPEED")
      (libsource (lib "eagle-import") (part "RESISTOR0402_RES-HIGH_SPEED"))
    )
    (comp (ref "R9")
      (value "27Ω")
      (footprint "eagle-import:0402_RES-HIGH_SPEED")
      (libsource (lib "eagle-import") (part "RESISTOR0402_RES-HIGH_SPEED"))
    )
    (comp (ref "R10")
      (value "27Ω")
      (footprint "eagle-import:0402_RES-HIGH_SPEED")
      (libsource (lib "eagle-import") (part "RESISTOR0402_RES-HIGH_SPEED"))
    )
    (comp (ref "R11")
      (value "27Ω")
      (footprint "eagle-import:0402_RES-HIGH_SPEED")
      (libsource (lib "eagle-import") (part "RESISTOR0402_RES-HIGH_SPEED"))
    )
    (comp (ref "R12")
      (value "27Ω")
      (footprint "eagle-import:0402_RES-HIGH_SPEED")
      (libsource (lib "eagle-import") (part "RESISTOR0402_RES-HIGH_SPEED"))
    )
    (comp (ref "R13")
      (value "50Ω")
      (footprint "eagle-import:0603-RES")
      (libsource (lib "eagle-import") (part "RESISTOR0603_RES"))
    )
    (comp (ref "R14")
      (value "50Ω")
      (footprint "eagle-import:0603-RES")
      (libsource (lib "eagle-import") (part "RESISTOR0603_RES"))
    )
    (comp (ref "R15")
      (value "50Ω")
      (footprint "eagle-import:0603-RES")
      (libsource (lib "eagle-import") (part "RESISTOR0603_RES"))
    )
    (comp (ref "R16")
      (value "50Ω")
      (footprint "eagle-import:0603-RES")
      (libsource (lib "eagle-import") (part "RESISTOR0603_RES"))
    )
    (comp (ref "R17")
      (value "50Ω")
      (footprint "eagle-import:0603-RES")
      (libsource (lib "eagle-import") (part "RESISTOR0603_RES"))
    )
    (comp (ref "R18")
      (value "50Ω")
      (footprint "eagle-import:0603-RES")
      (libsource (lib "eagle-import") (part "RESISTOR0603_RES"))
    )
    (comp (ref "R19")
      (value "50Ω")
      (footprint "eagle-import:0603-RES")
      (libsource (lib "eagle-import") (part "RESISTOR0603_RES"))
    )
    (comp (ref "R20")
      (value "50Ω")
      (footprint "eagle-import:0603-RES")
      (libsource (lib "eagle-import") (part "RESISTOR0603_RES"))
    )
    (comp (ref "R21")
      (value "50Ω")
      (footprint "eagle-import:0603-RES")
      (libsource (lib "eagle-import") (part "RESISTOR0603_RES"))
    )
    (comp (ref "R22")
      (value "50Ω")
      (footprint "eagle-import:0603-RES")
      (libsource (lib "eagle-import") (part "RESISTOR0603_RES"))
    )
    (comp (ref "R23")
      (value "50Ω")
      (footprint "eagle-import:0603-RES")
      (libsource (lib "eagle-import") (part "RESISTOR0603_RES"))
    )
    (comp (ref "R24")
      (value "50Ω")
      (footprint "eagle-import:0603-RES")
      (libsource (lib "eagle-import") (part "RESISTOR0603_RES"))
    )
    (comp (ref "R53")
      (value "15kΩ")
      (footprint "eagle-import:0603-RES")
      (libsource (lib "eagle-import") (part "RESISTOR0603_RES"))
    )
    (comp (ref "R54")
      (value "15kΩ")
      (footprint "eagle-import:0603-RES")
      (libsource (lib "eagle-import") (part "RESISTOR0603_RES"))
    )
    (comp (ref "R55")
      (value "15kΩ")
      (footprint "eagle-import:0603-RES")
      (libsource (lib "eagle-import") (part "RESISTOR0603_RES"))
    )
    (comp (ref "R56")
      (value "15kΩ")
      (footprint "eagle-import:0603-RES")
      (libsource (lib "eagle-import") (part "RESISTOR0603_RES"))
    )
    (comp (ref "R57")
      (value "15kΩ")
      (footprint "eagle-import:0603-RES")
      (libsource (lib "eagle-import") (part "RESISTOR0603_RES"))
    )
    (comp (ref "R58")
      (value "15kΩ")
      (footprint "eagle-import:0603-RES")
      (libsource (lib "eagle-import") (part "RESISTOR0603_RES"))
    )
    (comp (ref "R59")
      (value "15kΩ")
      (footprint "eagle-import:0603-RES")
      (libsource (lib "eagle-import") (part "RESISTOR0603_RES"))
    )
    (comp (ref "R60")
      (value "15kΩ")
      (footprint "eagle-import:0603-RES")
      (libsource (lib "eagle-import") (part "RESISTOR0603_RES"))
    )
    (comp (ref "R61")
      (value "15kΩ")
      (footprint "eagle-import:0603-RES")
      (libsource (lib "eagle-import") (part "RESISTOR0603_RES"))
    )
    (comp (ref "R62")
      (value "15kΩ")
      (footprint "eagle-import:0603-RES")
      (libsource (lib "eagle-import") (part "RESISTOR0603_RES"))
    )
    (comp (ref "R63")
      (value "15kΩ")
      (footprint "eagle-import:0603-RES")
      (libsource (lib "eagle-import") (part "RESISTOR0603_RES"))
    )
    (comp (ref "R64")
      (value "15kΩ")
      (footprint "eagle-import:0603-RES")
      (libsource (lib "eagle-import") (part "RESISTOR0603_RES"))
    )
    (comp (ref "U20")
      (value "TS3USB30E")
      (footprint "eagle-import:UQFN-10")
      (libsource (lib "eagle-import") (part "TS3USB30E"))
    )
    (comp (ref "U21")
      (value "TS3USB30E")
      (footprint "eagle-import:UQFN-10")
      (libsource (lib "eagle-import") (part "TS3USB30E"))
    )
    (comp (ref "U22")
      (value "TS3USB30E")
      (footprint "eagle-import:UQFN-10")
      (libsource (lib "eagle-import") (part "TS3USB30E"))
    )
    (comp (ref "U23")
      (value "TS3USB30E")
      (footprint "eagle-import:UQFN-10")
      (libsource (lib "eagle-import") (part "TS3USB30E"))
    )
    (comp (ref "U24")
      (value "TS3USB30E")
      (footprint "eagle-import:UQFN-10")
      (libsource (lib "eagle-import") (part "TS3USB30E"))
    )
    (comp (ref "U25")
      (value "TS3USB30E")
      (footprint "eagle-import:UQFN-10")
      (libsource (lib "eagle-import") (part "TS3USB30E"))
    )
  )
  (nets
    (net (code "1") (name "CONT_MOD0_IN") (class "Default")
      (node (ref "J3") (pin "9") (pinfunction "MOD0_IN_9") (pintype "bidirectional"))
      (node (ref "U8") (pin "2") (pinfunction "A1_2") (pintype "bidirectional"))
    )
    (net (code "2") (name "CONT_MOD0_OUT") (class "Default")
      (node (ref "J3") (pin "10") (pinfunction "MOD0_OUT_10") (pintype "bidirectional"))
      (node (ref "U14") (pin "2") (pinfunction "A1_2") (pintype "bidirectional"))
    )
    (net (code "3") (name "CONT_MOD1_IN") (class "Default")
      (node (ref "J3") (pin "11") (pinfunction "MOD1_IN_11") (pintype "bidirectional"))
      (node (ref "U9") (pin "2") (pinfunction "A1_2") (pintype "bidirectional"))
    )
    (net (code "4") (name "CONT_MOD1_OUT") (class "Default")
      (node (ref "J3") (pin "12") (pinfunction "MOD1_OUT_12") (pintype "bidirectional"))
      (node (ref "U15") (pin "2") (pinfunction "A1_2") (pintype "bidirectional"))
    )
    (net (code "5") (name "CONT_MOD2_IN") (class "Default")
      (node (ref "J3") (pin "13") (pinfunction "MOD2_IN_13") (pintype "bidirectional"))
      (node (ref "U10") (pin "2") (pinfunction "A1_2") (pintype "bidirectional"))
    )
    (net (code "6") (name "CONT_MOD2_OUT") (class "Default")
      (node (ref "J3") (pin "14") (pinfunction "MOD2_OUT_14") (pintype "bidirectional"))
      (node (ref "U16") (pin "2") (pinfunction "A1_2") (pintype "bidirectional"))
    )
    (net (code "7") (name "CONT_MOD5_IN") (class "Default")
      (node (ref "J3") (pin "15") (pinfunction "MOD5_IN_15") (pintype "bidirectional"))
      (node (ref "U11") (pin "2") (pinfunction "A1_2") (pintype "bidirectional"))
    )
    (net (code "8") (name "CONT_MOD5_OUT") (class "Default")
      (node (ref "J3") (pin "16") (pinfunction "MOD5_OUT_16") (pintype "bidirectional"))
      (node (ref "U17") (pin "2") (pinfunction "A1_2") (pintype "bidirectional"))
    )
    (net (code "9") (name "CONT_MOD6_IN") (class "Default")
      (node (ref "J3") (pin "17") (pinfunction "MOD6_IN_17") (pintype "bidirectional"))
      (node (ref "U12") (pin "2") (pinfunction "A1_2") (pintype "bidirectional"))
    )
    (net (code "10") (name "CONT_MOD6_OUT") (class "Default")
      (node (ref "J3") (pin "18") (pinfunction "MOD6_OUT_18") (pintype "bidirectional"))
      (node (ref "U18") (pin "2") (pinfunction "A1_2") (pintype "bidirectional"))
    )
    (net (code "11") (name "CONT_MOD7_IN") (class "Default")
      (node (ref "J3") (pin "19") (pinfunction "MOD7_IN_19") (pintype "bidirectional"))
      (node (ref "U13") (pin "2") (pinfunction "A1_2") (pintype "bidirectional"))
    )
    (net (code "12") (name "CONT_MOD7_OUT") (class "Default")
      (node (ref "J3") (pin "20") (pinfunction "MOD7_OUT_20") (pintype "bidirectional"))
      (node (ref "U19") (pin "2") (pinfunction "A1_2") (pintype "bidirectional"))
    )
    (net (code "13") (name "CONT_USB+") (class "Default")
      (node (ref "J3") (pin "27") (pinfunction "USB_D+_27") (pintype "bidirectional"))
      (node (ref "R25") (pin "1") (pinfunction "1_1") (pintype "passive"))
      (node (ref "U1") (pin "3") (pinfunction "DP0_3") (pintype "bidirectional"))
    )
    (net (code "14") (name "CONT_USB-") (class "Default")
      (node (ref "J3") (pin "28") (pinfunction "USB_D-_28") (pintype "bidirectional"))
      (node (ref "U1") (pin "4") (pinfunction "DM0_4") (pintype "bidirectional"))
    )
    (net (code "15") (name "GND") (class "Default")
      (node (ref "C1") (pin "1") (pinfunction "1_1") (pintype "bidirectional"))
      (node (ref "C10") (pin "2") (pinfunction "2_2") (pintype "bidirectional"))
      (node (ref "C100") (pin "2") (pinfunction "2_2") (pintype "passive"))
      (node (ref "C101") (pin "2") (pinfunction "2_2") (pintype "passive"))
      (node (ref "C102") (pin "2") (pinfunction "2_2") (pintype "passive"))
      (node (ref "C11") (pin "2") (pinfunction "2_2") (pintype "bidirectional"))
      (node (ref "C12") (pin "2") (pinfunction "2_2") (pintype "bidirectional"))
      (node (ref "C13") (pin "2") (pinfunction "2_2") (pintype "bidirectional"))
      (node (ref "C14") (pin "2") (pinfunction "2_2") (pintype "bidirectional"))
      (node (ref "C15") (pin "2") (pinfunction "2_2") (pintype "bidirectional"))
      (node (ref "C16") (pin "2") (pinfunction "2_2") (pintype "bidirectional"))
      (node (ref "C17") (pin "2") (pinfunction "2_2") (pintype "bidirectional"))
      (node (ref "C18") (pin "2") (pinfunction "2_2") (pintype "bidirectional"))
      (node (ref "C19") (pin "2") (pinfunction "2_2") (pintype "bidirectional"))
      (node (ref "C2") (pin "1") (pinfunction "1_1") (pintype "bidirectional"))
      (node (ref "C20") (pin "2") (pinfunction "2_2") (pintype "bidirectional"))
      (node (ref "C21") (pin "2") (pinfunction "2_2") (pintype "bidirectional"))
      (node (ref "C22") (pin "2") (pinfunction "2_2") (pintype "bidirectional"))
      (node (ref "C23") (pin "2") (pinfunction "2_2") (pintype "bidirectional"))
      (node (ref "C24") (pin "2") (pinfunction "2_2") (pintype "bidirectional"))
      (node (ref "C25") (pin "2") (pinfunction "2_2") (pintype "bidirectional"))
      (node (ref "C26") (pin "2") (pinfunction "2_2") (pintype "bidirectional"))
      (node (ref "C27") (pin "2") (pinfunction "2_2") (pintype "bidirectional"))
      (node (ref "C28") (pin "2") (pinfunction "2_2") (pintype "bidirectional"))
      (node (ref "C29") (pin "2") (pinfunction "2_2") (pintype "bidirectional"))
      (node (ref "C3") (pin "2") (pinfunction "2_2") (pintype "bidirectional"))
      (node (ref "C30") (pin "2") (pinfunction "2_2") (pintype "bidirectional"))
      (node (ref "C31") (pin "2") (pinfunction "2_2") (pintype "bidirectional"))
      (node (ref "C32") (pin "2") (pinfunction "2_2") (pintype "bidirectional"))
      (node (ref "C33") (pin "2") (pinfunction "2_2") (pintype "bidirectional"))
      (node (ref "C34") (pin "2") (pinfunction "2_2") (pintype "bidirectional"))
      (node (ref "C35") (pin "2") (pinfunction "2_2") (pintype "bidirectional"))
      (node (ref "C36") (pin "2") (pinfunction "2_2") (pintype "bidirectional"))
      (node (ref "C37") (pin "2") (pinfunction "2_2") (pintype "bidirectional"))
      (node (ref "C38") (pin "2") (pinfunction "2_2") (pintype "bidirectional"))
      (node (ref "C39") (pin "2") (pinfunction "2_2") (pintype "bidirectional"))
      (node (ref "C4") (pin "2") (pinfunction "2_2") (pintype "bidirectional"))
      (node (ref "C40") (pin "2") (pinfunction "2_2") (pintype "bidirectional"))
      (node (ref "C41") (pin "2") (pinfunction "2_2") (pintype "bidirectional"))
      (node (ref "C42") (pin "2") (pinfunction "2_2") (pintype "bidirectional"))
      (node (ref "C43") (pin "2") (pinfunction "2_2") (pintype "bidirectional"))
      (node (ref "C44") (pin "2") (pinfunction "2_2") (pintype "bidirectional"))
      (node (ref "C45") (pin "2") (pinfunction "2_2") (pintype "bidirectional"))
      (node (ref "C46") (pin "2") (pinfunction "2_2") (pintype "bidirectional"))
      (node (ref "C47") (pin "2") (pinfunction "2_2") (pintype "bidirectional"))
      (node (ref "C48") (pin "2") (pinfunction "2_2") (pintype "bidirectional"))
      (node (ref "C49") (pin "2") (pinfunction "2_2") (pintype "bidirectional"))
      (node (ref "C5") (pin "2") (pinfunction "2_2") (pintype "bidirectional"))
      (node (ref "C50") (pin "2") (pinfunction "2_2") (pintype "bidirectional"))
      (node (ref "C51") (pin "1") (pinfunction "1_1") (pintype "bidirectional"))
      (node (ref "C52") (pin "2") (pinfunction "2_2") (pintype "bidirectional"))
      (node (ref "C53") (pin "2") (pinfunction "2_2") (pintype "bidirectional"))
      (node (ref "C54") (pin "2") (pinfunction "2_2") (pintype "bidirectional"))
      (node (ref "C55") (pin "2") (pinfunction "2_2") (pintype "bidirectional"))
      (node (ref "C56") (pin "2") (pinfunction "2_2") (pintype "bidirectional"))
      (node (ref "C57") (pin "2") (pinfunction "2_2") (pintype "bidirectional"))
      (node (ref "C58") (pin "2") (pinfunction "2_2") (pintype "bidirectional"))
      (node (ref "C59") (pin "2") (pinfunction "2_2") (pintype "bidirectional"))
      (node (ref "C6") (pin "2") (pinfunction "2_2") (pintype "bidirectional"))
      (node (ref "C60") (pin "2") (pinfunction "2_2") (pintype "bidirectional"))
      (node (ref "C61") (pin "2") (pinfunction "2_2") (pintype "bidirectional"))
      (node (ref "C62") (pin "2") (pinfunction "2_2") (pintype "bidirectional"))
      (node (ref "C63") (pin "2") (pinfunction "2_2") (pintype "bidirectional"))
      (node (ref "C64") (pin "2") (pinfunction "2_2") (pintype "bidirectional"))
      (node (ref "C65") (pin "2") (pinfunction "2_2") (pintype "bidirectional"))
      (node (ref "C66") (pin "2") (pinfunction "2_2") (pintype "bidirectional"))
      (node (ref "C67") (pin "2") (pinfunction "2_2") (pintype "bidirectional"))
      (node (ref "C68") (pin "2") (pinfunction "2_2") (pintype "bidirectional"))
      (node (ref "C69") (pin "2") (pinfunction "2_2") (pintype "bidirectional"))
      (node (ref "C7") (pin "2") (pinfunction "2_2") (pintype "bidirectional"))
      (node (ref "C70") (pin "2") (pinfunction "2_2") (pintype "bidirectional"))
      (node (ref "C71") (pin "2") (pinfunction "2_2") (pintype "bidirectional"))
      (node (ref "C72") (pin "2") (pinfunction "2_2") (pintype "bidirectional"))
      (node (ref "C73") (pin "2") (pinfunction "2_2") (pintype "bidirectional"))
      (node (ref "C74") (pin "2") (pinfunction "2_2") (pintype "bidirectional"))
      (node (ref "C75") (pin "2") (pinfunction "2_2") (pintype "bidirectional"))
      (node (ref "C76") (pin "1") (pinfunction "1_1") (pintype "bidirectional"))
      (node (ref "C77") (pin "1") (pinfunction "1_1") (pintype "bidirectional"))
      (node (ref "C78") (pin "1") (pinfunction "1_1") (pintype "bidirectional"))
      (node (ref "C79") (pin "1") (pinfunction "1_1") (pintype "bidirectional"))
      (node (ref "C8") (pin "2") (pinfunction "2_2") (pintype "bidirectional"))
      (node (ref "C80") (pin "1") (pinfunction "1_1") (pintype "bidirectional"))
      (node (ref "C81") (pin "1") (pinfunction "1_1") (pintype "bidirectional"))
      (node (ref "C82") (pin "2") (pinfunction "2_2") (pintype "bidirectional"))
      (node (ref "C83") (pin "2") (pinfunction "2_2") (pintype "bidirectional"))
      (node (ref "C84") (pin "2") (pinfunction "2_2") (pintype "bidirectional"))
      (node (ref "C85") (pin "2") (pinfunction "2_2") (pintype "bidirectional"))
      (node (ref "C86") (pin "2") (pinfunction "2_2") (pintype "bidirectional"))
      (node (ref "C87") (pin "2") (pinfunction "2_2") (pintype "bidirectional"))
      (node (ref "C88") (pin "2") (pinfunction "2_2") (pintype "bidirectional"))
      (node (ref "C89") (pin "2") (pinfunction "2_2") (pintype "bidirectional"))
      (node (ref "C9") (pin "2") (pinfunction "2_2") (pintype "bidirectional"))
      (node (ref "C90") (pin "2") (pinfunction "2_2") (pintype "bidirectional"))
      (node (ref "C91") (pin "2") (pinfunction "2_2") (pintype "bidirectional"))
      (node (ref "C92") (pin "2") (pinfunction "2_2") (pintype "bidirectional"))
      (node (ref "C93") (pin "2") (pinfunction "2_2") (pintype "bidirectional"))
      (node (ref "C94") (pin "2") (pinfunction "2_2") (pintype "bidirectional"))
      (node (ref "C95") (pin "2") (pinfunction "2_2") (pintype "bidirectional"))
      (node (ref "C96") (pin "1") (pinfunction "1_1") (pintype "bidirectional"))
      (node (ref "C97") (pin "2") (pinfunction "2_2") (pintype "passive"))
      (node (ref "C98") (pin "2") (pinfunction "2_2") (pintype "passive"))
      (node (ref "C99") (pin "2") (pinfunction "2_2") (pintype "passive"))
      (node (ref "D1") (pin "1") (pinfunction "GND_1") (pintype "bidirectional"))
      (node (ref "D1") (pin "3") (pinfunction "GND_3") (pintype "bidirectional"))
      (node (ref "D1") (pin "5") (pinfunction "GND_5") (pintype "bidirectional"))
      (node (ref "D1") (pin "7") (pinfunction "GND_7") (pintype "bidirectional"))
      (node (ref "D2") (pin "1") (pinfunction "GND_1") (pintype "bidirectional"))
      (node (ref "D2") (pin "3") (pinfunction "GND_3") (pintype "bidirectional"))
      (node (ref "D2") (pin "5") (pinfunction "GND_5") (pintype "bidirectional"))
      (node (ref "D2") (pin "7") (pinfunction "GND_7") (pintype "bidirectional"))
      (node (ref "D3") (pin "1") (pinfunction "GND_1") (pintype "bidirectional"))
      (node (ref "D3") (pin "3") (pinfunction "GND_3") (pintype "bidirectional"))
      (node (ref "D3") (pin "5") (pinfunction "GND_5") (pintype "bidirectional"))
      (node (ref "D3") (pin "7") (pinfunction "GND_7") (pintype "bidirectional"))
      (node (ref "D4") (pin "1") (pinfunction "GND_1") (pintype "bidirectional"))
      (node (ref "D4") (pin "3") (pinfunction "GND_3") (pintype "bidirectional"))
      (node (ref "D4") (pin "5") (pinfunction "GND_5") (pintype "bidirectional"))
      (node (ref "D4") (pin "7") (pinfunction "GND_7") (pintype "bidirectional"))
      (node (ref "H1") (pin "B#4") (pinfunction "MOUNT_B#4") (pintype "passive"))
      (node (ref "H10") (pin "B#4") (pinfunction "MOUNT_B#4") (pintype "passive"))
      (node (ref "H11") (pin "B#4") (pinfunction "MOUNT_B#4") (pintype "passive"))
      (node (ref "H12") (pin "B#4") (pinfunction "MOUNT_B#4") (pintype "passive"))
      (node (ref "H13") (pin "B#4") (pinfunction "MOUNT_B#4") (pintype "passive"))
      (node (ref "H14") (pin "B#4") (pinfunction "MOUNT_B#4") (pintype "passive"))
      (node (ref "H15") (pin "B#4") (pinfunction "MOUNT_B#4") (pintype "passive"))
      (node (ref "H16") (pin "B#4") (pinfunction "MOUNT_B#4") (pintype "passive"))
      (node (ref "H17") (pin "B#4") (pinfunction "MOUNT_B#4") (pintype "passive"))
      (node (ref "H18") (pin "B#4") (pinfunction "MOUNT_B#4") (pintype "passive"))
      (node (ref "H19") (pin "B#4") (pinfunction "MOUNT_B#4") (pintype "passive"))
      (node (ref "H2") (pin "B#4") (pinfunction "MOUNT_B#4") (pintype "passive"))
      (node (ref "H20") (pin "B#4") (pinfunction "MOUNT_B#4") (pintype "passive"))
      (node (ref "H3") (pin "B#4") (pinfunction "MOUNT_B#4") (pintype "passive"))
      (node (ref "H4") (pin "B#4") (pinfunction "MOUNT_B#4") (pintype "passive"))
      (node (ref "H5") (pin "B#4") (pinfunction "MOUNT_B#4") (pintype "passive"))
      (node (ref "H6") (pin "B#4") (pinfunction "MOUNT_B#4") (pintype "passive"))
      (node (ref "H7") (pin "B#4") (pinfunction "MOUNT_B#4") (pintype "passive"))
      (node (ref "H8") (pin "B#4") (pinfunction "MOUNT_B#4") (pintype "passive"))
      (node (ref "H9") (pin "B#4") (pinfunction "MOUNT_B#4") (pintype "passive"))
      (node (ref "J0") (pin "1") (pinfunction "GND_1") (pintype "bidirectional"))
      (node (ref "J0") (pin "14") (pinfunction "GND_14") (pintype "bidirectional"))
      (node (ref "J0") (pin "MNT1") (pinfunction "GND_MNT1") (pintype "bidirectional"))
      (node (ref "J0") (pin "MNT2") (pinfunction "GND_MNT2") (pintype "bidirectional"))
      (node (ref "J0") (pin "MNT3") (pinfunction "GND_MNT3") (pintype "bidirectional"))
      (node (ref "J0") (pin "MNT4") (pinfunction "GND_MNT4") (pintype "bidirectional"))
      (node (ref "J1") (pin "1") (pinfunction "GND_1") (pintype "bidirectional"))
      (node (ref "J1") (pin "14") (pinfunction "GND_14") (pintype "bidirectional"))
      (node (ref "J1") (pin "MNT1") (pinfunction "GND_MNT1") (pintype "bidirectional"))
      (node (ref "J1") (pin "MNT2") (pinfunction "GND_MNT2") (pintype "bidirectional"))
      (node (ref "J1") (pin "MNT3") (pinfunction "GND_MNT3") (pintype "bidirectional"))
      (node (ref "J1") (pin "MNT4") (pinfunction "GND_MNT4") (pintype "bidirectional"))
      (node (ref "J2") (pin "1") (pinfunction "GND_1") (pintype "bidirectional"))
      (node (ref "J2") (pin "14") (pinfunction "GND_14") (pintype "bidirectional"))
      (node (ref "J2") (pin "MNT1") (pinfunction "GND_MNT1") (pintype "bidirectional"))
      (node (ref "J2") (pin "MNT2") (pinfunction "GND_MNT2") (pintype "bidirectional"))
      (node (ref "J2") (pin "MNT3") (pinfunction "GND_MNT3") (pintype "bidirectional"))
      (node (ref "J2") (pin "MNT4") (pinfunction "GND_MNT4") (pintype "bidirectional"))
      (node (ref "J3") (pin "1") (pinfunction "GND_1") (pintype "bidirectional"))
      (node (ref "J3") (pin "21") (pinfunction "GND_21") (pintype "bidirectional"))
      (node (ref "J3") (pin "MNT1") (pinfunction "GND_MNT1") (pintype "bidirectional"))
      (node (ref "J3") (pin "MNT2") (pinfunction "GND_MNT2") (pintype "bidirectional"))
      (node (ref "J3") (pin "MNT3") (pinfunction "GND_MNT3") (pintype "bidirectional"))
      (node (ref "J3") (pin "MNT4") (pinfunction "GND_MNT4") (pintype "bidirectional"))
      (node (ref "J4") (pin "1") (pinfunction "GND_1") (pintype "power_in"))
      (node (ref "J4") (pin "MNT1") (pinfunction "GND_MNT1") (pintype "power_in"))
      (node (ref "J4") (pin "MNT2") (pinfunction "GND_MNT2") (pintype "power_in"))
      (node (ref "J4") (pin "MNT3") (pinfunction "GND_MNT3") (pintype "power_in"))
      (node (ref "J4") (pin "MNT4") (pinfunction "GND_MNT4") (pintype "power_in"))
      (node (ref "J5") (pin "1") (pinfunction "GND_1") (pintype "bidirectional"))
      (node (ref "J5") (pin "14") (pinfunction "GND_14") (pintype "bidirectional"))
      (node (ref "J5") (pin "MNT1") (pinfunction "GND_MNT1") (pintype "bidirectional"))
      (node (ref "J5") (pin "MNT2") (pinfunction "GND_MNT2") (pintype "bidirectional"))
      (node (ref "J5") (pin "MNT3") (pinfunction "GND_MNT3") (pintype "bidirectional"))
      (node (ref "J5") (pin "MNT4") (pinfunction "GND_MNT4") (pintype "bidirectional"))
      (node (ref "J6") (pin "1") (pinfunction "GND_1") (pintype "bidirectional"))
      (node (ref "J6") (pin "14") (pinfunction "GND_14") (pintype "bidirectional"))
      (node (ref "J6") (pin "MNT1") (pinfunction "GND_MNT1") (pintype "bidirectional"))
      (node (ref "J6") (pin "MNT2") (pinfunction "GND_MNT2") (pintype "bidirectional"))
      (node (ref "J6") (pin "MNT3") (pinfunction "GND_MNT3") (pintype "bidirectional"))
      (node (ref "J6") (pin "MNT4") (pinfunction "GND_MNT4") (pintype "bidirectional"))
      (node (ref "J7") (pin "1") (pinfunction "GND_1") (pintype "bidirectional"))
      (node (ref "J7") (pin "14") (pinfunction "GND_14") (pintype "bidirectional"))
      (node (ref "J7") (pin "MNT1") (pinfunction "GND_MNT1") (pintype "bidirectional"))
      (node (ref "J7") (pin "MNT2") (pinfunction "GND_MNT2") (pintype "bidirectional"))
      (node (ref "J7") (pin "MNT3") (pinfunction "GND_MNT3") (pintype "bidirectional"))
      (node (ref "J7") (pin "MNT4") (pinfunction "GND_MNT4") (pintype "bidirectional"))
      (node (ref "LED1001") (pin "C") (pinfunction "CATHODE_C") (pintype "bidirectional"))
      (node (ref "LED1002") (pin "C") (pinfunction "CATHODE_C") (pintype "bidirectional"))
      (node (ref "LED1003") (pin "C") (pinfunction "CATHODE_C") (pintype "bidirectional"))
      (node (ref "LED1007") (pin "C") (pinfunction "CATHODE_C") (pintype "bidirectional"))
      (node (ref "LED1008") (pin "C") (pinfunction "CATHODE_C") (pintype "bidirectional"))
      (node (ref "LED1009") (pin "C") (pinfunction "CATHODE_C") (pintype "bidirectional"))
      (node (ref "LED1013") (pin "C") (pinfunction "CATHODE_C") (pintype "bidirectional"))
      (node (ref "LED1014") (pin "C") (pinfunction "CATHODE_C") (pintype "bidirectional"))
      (node (ref "LED1015") (pin "C") (pinfunction "CATHODE_C") (pintype "bidirectional"))
      (node (ref "R1004") (pin "1") (pinfunction "1_1") (pintype "passive"))
      (node (ref "R1005") (pin "1") (pinfunction "1_1") (pintype "passive"))
      (node (ref "R1006") (pin "1") (pinfunction "1_1") (pintype "passive"))
      (node (ref "R1010") (pin "1") (pinfunction "1_1") (pintype "passive"))
      (node (ref "R1011") (pin "1") (pinfunction "1_1") (pintype "passive"))
      (node (ref "R1012") (pin "1") (pinfunction "1_1") (pintype "passive"))
      (node (ref "R1016") (pin "1") (pinfunction "1_1") (pintype "passive"))
      (node (ref "R1017") (pin "1") (pinfunction "1_1") (pintype "passive"))
      (node (ref "R1018") (pin "1") (pinfunction "1_1") (pintype "passive"))
      (node (ref "R13") (pin "2") (pinfunction "2_2") (pintype "passive"))
      (node (ref "R14") (pin "2") (pinfunction "2_2") (pintype "passive"))
      (node (ref "R15") (pin "2") (pinfunction "2_2") (pintype "passive"))
      (node (ref "R16") (pin "2") (pinfunction "2_2") (pintype "passive"))
      (node (ref "R17") (pin "2") (pinfunction "2_2") (pintype "passive"))
      (node (ref "R18") (pin "2") (pinfunction "2_2") (pintype "passive"))
      (node (ref "R19") (pin "2") (pinfunction "2_2") (pintype "passive"))
      (node (ref "R20") (pin "2") (pinfunction "2_2") (pintype "passive"))
      (node (ref "R21") (pin "2") (pinfunction "2_2") (pintype "passive"))
      (node (ref "R22") (pin "2") (pinfunction "2_2") (pintype "passive"))
      (node (ref "R23") (pin "2") (pinfunction "2_2") (pintype "passive"))
      (node (ref "R24") (pin "2") (pinfunction "2_2") (pintype "passive"))
      (node (ref "R53") (pin "1") (pinfunction "1_1") (pintype "passive"))
      (node (ref "R54") (pin "1") (pinfunction "1_1") (pintype "passive"))
      (node (ref "R55") (pin "1") (pinfunction "1_1") (pintype "passive"))
      (node (ref "R56") (pin "1") (pinfunction "1_1") (pintype "passive"))
      (node (ref "R57") (pin "1") (pinfunction "1_1") (pintype "passive"))
      (node (ref "R58") (pin "1") (pinfunction "1_1") (pintype "passive"))
      (node (ref "R59") (pin "1") (pinfunction "1_1") (pintype "passive"))
      (node (ref "R60") (pin "1") (pinfunction "1_1") (pintype "passive"))
      (node (ref "R61") (pin "1") (pinfunction "1_1") (pintype "passive"))
      (node (ref "R62") (pin "1") (pinfunction "1_1") (pintype "passive"))
      (node (ref "R63") (pin "1") (pinfunction "1_1") (pintype "passive"))
      (node (ref "R64") (pin "1") (pinfunction "1_1") (pintype "passive"))
      (node (ref "R65") (pin "2") (pinfunction "2_2") (pintype "passive"))
      (node (ref "R66") (pin "2") (pinfunction "2_2") (pintype "passive"))
      (node (ref "R67") (pin "1") (pinfunction "1_1") (pintype "passive"))
      (node (ref "R68") (pin "1") (pinfunction "1_1") (pintype "passive"))
      (node (ref "R69") (pin "1") (pinfunction "1_1") (pintype "passive"))
      (node (ref "R70") (pin "1") (pinfunction "1_1") (pintype "passive"))
      (node (ref "R71") (pin "1") (pinfunction "1_1") (pintype "passive"))
      (node (ref "R72") (pin "1") (pinfunction "1_1") (pintype "passive"))
      (node (ref "R73") (pin "1") (pinfunction "1_1") (pintype "passive"))
      (node (ref "R74") (pin "1") (pinfunction "1_1") (pintype "passive"))
      (node (ref "R75") (pin "1") (pinfunction "1_1") (pintype "passive"))
      (node (ref "R76") (pin "1") (pinfunction "1_1") (pintype "passive"))
      (node (ref "R77") (pin "1") (pinfunction "1_1") (pintype "passive"))
      (node (ref "R78") (pin "1") (pinfunction "1_1") (pintype "passive"))
      (node (ref "R79") (pin "1") (pinfunction "1_1") (pintype "passive"))
      (node (ref "R80") (pin "1") (pinfunction "1_1") (pintype "passive"))
      (node (ref "R81") (pin "1") (pinfunction "1_1") (pintype "passive"))
      (node (ref "R82") (pin "1") (pinfunction "1_1") (pintype "passive"))
      (node (ref "R83") (pin "1") (pinfunction "1_1") (pintype "passive"))
      (node (ref "R84") (pin "1") (pinfunction "1_1") (pintype "passive"))
      (node (ref "S1") (pin "2") (pinfunction "GND_2") (pintype "bidirectional"))
      (node (ref "S1") (pin "PAD") (pinfunction "GND_PAD") (pintype "bidirectional"))
      (node (ref "S10") (pin "2") (pinfunction "GND_2") (pintype "bidirectional"))
      (node (ref "S11") (pin "2") (pinfunction "GND_2") (pintype "bidirectional"))
      (node (ref "S12") (pin "2") (pinfunction "GND_2") (pintype "bidirectional"))
      (node (ref "S13") (pin "1") (pinfunction "GND_1") (pintype "bidirectional"))
      (node (ref "S13") (pin "PAD") (pinfunction "GND_PAD") (pintype "bidirectional"))
      (node (ref "S14") (pin "1") (pinfunction "GND_1") (pintype "bidirectional"))
      (node (ref "S14") (pin "PAD") (pinfunction "GND_PAD") (pintype "bidirectional"))
      (node (ref "S15") (pin "1") (pinfunction "GND_1") (pintype "bidirectional"))
      (node (ref "S15") (pin "PAD") (pinfunction "GND_PAD") (pintype "bidirectional"))
      (node (ref "S16") (pin "1") (pinfunction "GND_1") (pintype "bidirectional"))
      (node (ref "S16") (pin "PAD") (pinfunction "GND_PAD") (pintype "bidirectional"))
      (node (ref "S17") (pin "1") (pinfunction "GND_1") (pintype "bidirectional"))
      (node (ref "S17") (pin "PAD") (pinfunction "GND_PAD") (pintype "bidirectional"))
      (node (ref "S18") (pin "1") (pinfunction "GND_1") (pintype "bidirectional"))
      (node (ref "S18") (pin "PAD") (pinfunction "GND_PAD") (pintype "bidirectional"))
      (node (ref "S2") (pin "2") (pinfunction "GND_2") (pintype "bidirectional"))
      (node (ref "S2") (pin "PAD") (pinfunction "GND_PAD") (pintype "bidirectional"))
      (node (ref "S3") (pin "2") (pinfunction "GND_2") (pintype "bidirectional"))
      (node (ref "S3") (pin "PAD") (pinfunction "GND_PAD") (pintype "bidirectional"))
      (node (ref "S4") (pin "2") (pinfunction "GND_2") (pintype "bidirectional"))
      (node (ref "S4") (pin "PAD") (pinfunction "GND_PAD") (pintype "bidirectional"))
      (node (ref "S5") (pin "2") (pinfunction "GND_2") (pintype "bidirectional"))
      (node (ref "S5") (pin "PAD") (pinfunction "GND_PAD") (pintype "bidirectional"))
      (node (ref "S6") (pin "2") (pinfunction "GND_2") (pintype "bidirectional"))
      (node (ref "S6") (pin "PAD") (pinfunction "GND_PAD") (pintype "bidirectional"))
      (node (ref "S7") (pin "2") (pinfunction "GND_2") (pintype "bidirectional"))
      (node (ref "S8") (pin "2") (pinfunction "GND_2") (pintype "bidirectional"))
      (node (ref "S9") (pin "2") (pinfunction "GND_2") (pintype "bidirectional"))
      (node (ref "TP11") (pin "TESTPOINT") (pinfunction "TESTPOINT_TESTPOINT") (pintype "bidirectional"))
      (node (ref "TP25") (pin "TESTPOINT") (pinfunction "TESTPOINT_TESTPOINT") (pintype "bidirectional"))
      (node (ref "TP26") (pin "TESTPOINT") (pinfunction "TESTPOINT_TESTPOINT") (pintype "bidirectional"))
      (node (ref "TP27") (pin "TESTPOINT") (pinfunction "TESTPOINT_TESTPOINT") (pintype "bidirectional"))
      (node (ref "TP4") (pin "TESTPOINT") (pinfunction "TESTPOINT_TESTPOINT") (pintype "bidirectional"))
      (node (ref "TP7") (pin "TESTPOINT") (pinfunction "TESTPOINT_TESTPOINT") (pintype "bidirectional"))
      (node (ref "U1") (pin "24") (pinfunction "GND_24") (pintype "bidirectional"))
      (node (ref "U1") (pin "43") (pinfunction "GND_43") (pintype "bidirectional"))
      (node (ref "U1") (pin "48") (pinfunction "MODE_48") (pintype "bidirectional"))
      (node (ref "U1") (pin "5") (pinfunction "GND_5") (pintype "bidirectional"))
      (node (ref "U10") (pin "4") (pinfunction "GND_4") (pintype "bidirectional"))
      (node (ref "U11") (pin "4") (pinfunction "GND_4") (pintype "bidirectional"))
      (node (ref "U12") (pin "4") (pinfunction "GND_4") (pintype "bidirectional"))
      (node (ref "U13") (pin "4") (pinfunction "GND_4") (pintype "bidirectional"))
      (node (ref "U14") (pin "4") (pinfunction "GND_4") (pintype "bidirectional"))
      (node (ref "U14") (pin "5") (pinfunction "DIR_5") (pintype "bidirectional"))
      (node (ref "U15") (pin "4") (pinfunction "GND_4") (pintype "bidirectional"))
      (node (ref "U15") (pin "5") (pinfunction "DIR_5") (pintype "bidirectional"))
      (node (ref "U16") (pin "4") (pinfunction "GND_4") (pintype "bidirectional"))
      (node (ref "U16") (pin "5") (pinfunction "DIR_5") (pintype "bidirectional"))
      (node (ref "U17") (pin "4") (pinfunction "GND_4") (pintype "bidirectional"))
      (node (ref "U17") (pin "5") (pinfunction "DIR_5") (pintype "bidirectional"))
      (node (ref "U18") (pin "4") (pinfunction "GND_4") (pintype "bidirectional"))
      (node (ref "U19") (pin "4") (pinfunction "GND_4") (pintype "bidirectional"))
      (node (ref "U19") (pin "5") (pinfunction "DIR_5") (pintype "bidirectional"))
      (node (ref "U2") (pin "4") (pinfunction "GND_4") (pintype "bidirectional"))
      (node (ref "U20") (pin "10") (pinfunction "S_10") (pintype "bidirectional"))
      (node (ref "U20") (pin "4") (pinfunction "GND_4") (pintype "bidirectional"))
      (node (ref "U21") (pin "10") (pinfunction "S_10") (pintype "bidirectional"))
      (node (ref "U21") (pin "4") (pinfunction "GND_4") (pintype "bidirectional"))
      (node (ref "U22") (pin "10") (pinfunction "S_10") (pintype "bidirectional"))
      (node (ref "U22") (pin "4") (pinfunction "GND_4") (pintype "bidirectional"))
      (node (ref "U23") (pin "10") (pinfunction "S_10") (pintype "bidirectional"))
      (node (ref "U23") (pin "4") (pinfunction "GND_4") (pintype "bidirectional"))
      (node (ref "U24") (pin "10") (pinfunction "S_10") (pintype "bidirectional"))
      (node (ref "U24") (pin "4") (pinfunction "GND_4") (pintype "bidirectional"))
      (node (ref "U25") (pin "10") (pinfunction "S_10") (pintype "bidirectional"))
      (node (ref "U25") (pin "4") (pinfunction "GND_4") (pintype "bidirectional"))
      (node (ref "U26") (pin "1") (pinfunction "A2_1") (pintype "bidirectional"))
      (node (ref "U26") (pin "17") (pinfunction "GND_17") (pintype "bidirectional"))
      (node (ref "U26") (pin "2") (pinfunction "A1_2") (pintype "bidirectional"))
      (node (ref "U26") (pin "3") (pinfunction "A0_3") (pintype "bidirectional"))
      (node (ref "U26") (pin "GND") (pinfunction "GND_GND") (pintype "bidirectional"))
      (node (ref "U27") (pin "1") (pinfunction "A2_1") (pintype "bidirectional"))
      (node (ref "U27") (pin "17") (pinfunction "GND_17") (pintype "bidirectional"))
      (node (ref "U27") (pin "2") (pinfunction "A1_2") (pintype "bidirectional"))
      (node (ref "U27") (pin "GND") (pinfunction "GND_GND") (pintype "bidirectional"))
      (node (ref "U28") (pin "1") (pinfunction "A2_1") (pintype "bidirectional"))
      (node (ref "U28") (pin "17") (pinfunction "GND_17") (pintype "bidirectional"))
      (node (ref "U28") (pin "3") (pinfunction "A0_3") (pintype "bidirectional"))
      (node (ref "U28") (pin "GND") (pinfunction "GND_GND") (pintype "bidirectional"))
      (node (ref "U29") (pin "17") (pinfunction "GND_17") (pintype "bidirectional"))
      (node (ref "U29") (pin "2") (pinfunction "A1_2") (pintype "bidirectional"))
      (node (ref "U29") (pin "GND") (pinfunction "GND_GND") (pintype "bidirectional"))
      (node (ref "U3") (pin "4") (pinfunction "GND_4") (pintype "bidirectional"))
      (node (ref "U30") (pin "17") (pinfunction "GND_17") (pintype "bidirectional"))
      (node (ref "U30") (pin "3") (pinfunction "A0_3") (pintype "bidirectional"))
      (node (ref "U30") (pin "GND") (pinfunction "GND_GND") (pintype "bidirectional"))
      (node (ref "U31") (pin "17") (pinfunction "GND_17") (pintype "bidirectional"))
      (node (ref "U31") (pin "GND") (pinfunction "GND_GND") (pintype "bidirectional"))
      (node (ref "U32") (pin "1") (pinfunction "A2_1") (pintype "bidirectional"))
      (node (ref "U32") (pin "17") (pinfunction "GND_17") (pintype "bidirectional"))
      (node (ref "U32") (pin "GND") (pinfunction "GND_GND") (pintype "bidirectional"))
      (node (ref "U33") (pin "3") (pinfunction "GND_3") (pintype "bidirectional"))
      (node (ref "U34") (pin "2") (pinfunction "E1_2") (pintype "bidirectional"))
      (node (ref "U34") (pin "3") (pinfunction "E2_3") (pintype "bidirectional"))
      (node (ref "U34") (pin "4") (pinfunction "GND_4") (pintype "bidirectional"))
      (node (ref "U4") (pin "4") (pinfunction "GND_4") (pintype "bidirectional"))
      (node (ref "U5") (pin "4") (pinfunction "GND_4") (pintype "bidirectional"))
      (node (ref "U6") (pin "4") (pinfunction "GND_4") (pintype "bidirectional"))
      (node (ref "U7") (pin "4") (pinfunction "GND_4") (pintype "bidirectional"))
      (node (ref "U8") (pin "4") (pinfunction "GND_4") (pintype "bidirectional"))
      (node (ref "U9") (pin "4") (pinfunction "GND_4") (pintype "bidirectional"))
    )
    (net (code "16") (name "HUB_CFG") (class "Default")
      (node (ref "TP28") (pin "TESTPOINT") (pinfunction "TESTPOINT_TESTPOINT") (pintype "bidirectional"))
      (node (ref "U1") (pin "40") (pinfunction "HUBCFG_40") (pintype "bidirectional"))
      (node (ref "U32") (pin "14") (pinfunction "P5_14") (pintype "bidirectional"))
    )
    (net (code "17") (name "HUB_DM1") (class "Default")
      (node (ref "C6") (pin "1") (pinfunction "1_1") (pintype "bidirectional"))
      (node (ref "R4") (pin "1") (pinfunction "1_1") (pintype "passive"))
      (node (ref "U1") (pin "13") (pinfunction "DM1_13") (pintype "bidirectional"))
    )
    (net (code "18") (name "HUB_DM2") (class "Default")
      (node (ref "C4") (pin "1") (pinfunction "1_1") (pintype "bidirectional"))
      (node (ref "R2") (pin "1") (pinfunction "1_1") (pintype "passive"))
      (node (ref "U1") (pin "17") (pinfunction "DM2_17") (pintype "bidirectional"))
    )
    (net (code "19") (name "HUB_DM3") (class "Default")
      (node (ref "C8") (pin "1") (pinfunction "1_1") (pintype "bidirectional"))
      (node (ref "R6") (pin "1") (pinfunction "1_1") (pintype "passive"))
      (node (ref "U1") (pin "21") (pinfunction "DM3_21") (pintype "bidirectional"))
    )
    (net (code "20") (name "HUB_DM4") (class "Default")
      (node (ref "C12") (pin "1") (pinfunction "1_1") (pintype "bidirectional"))
      (node (ref "R10") (pin "1") (pinfunction "1_1") (pintype "passive"))
      (node (ref "U1") (pin "26") (pinfunction "DM4_26") (pintype "bidirectional"))
    )
    (net (code "21") (name "HUB_DM5") (class "Default")
      (node (ref "R66") (pin "1") (pinfunction "1_1") (pintype "passive"))
      (node (ref "U1") (pin "30") (pinfunction "DM5_30") (pintype "bidirectional"))
    )
    (net (code "22") (name "HUB_DM6") (class "Default")
      (node (ref "C14") (pin "1") (pinfunction "1_1") (pintype "bidirectional"))
      (node (ref "R12") (pin "1") (pinfunction "1_1") (pintype "passive"))
      (node (ref "U1") (pin "34") (pinfunction "DM6_34") (pintype "bidirectional"))
    )
    (net (code "23") (name "HUB_DM7") (class "Default")
      (node (ref "C10") (pin "1") (pinfunction "1_1") (pintype "bidirectional"))
      (node (ref "R8") (pin "1") (pinfunction "1_1") (pintype "passive"))
      (node (ref "U1") (pin "38") (pinfunction "DM7_38") (pintype "bidirectional"))
    )
    (net (code "24") (name "HUB_DP1") (class "Default")
      (node (ref "C5") (pin "1") (pinfunction "1_1") (pintype "bidirectional"))
      (node (ref "R3") (pin "1") (pinfunction "1_1") (pintype "passive"))
      (node (ref "U1") (pin "14") (pinfunction "DP1_14") (pintype "bidirectional"))
    )
    (net (code "25") (name "HUB_DP2") (class "Default")
      (node (ref "C3") (pin "1") (pinfunction "1_1") (pintype "bidirectional"))
      (node (ref "R1") (pin "1") (pinfunction "1_1") (pintype "passive"))
      (node (ref "U1") (pin "18") (pinfunction "DP2_18") (pintype "bidirectional"))
    )
    (net (code "26") (name "HUB_DP3") (class "Default")
      (node (ref "C7") (pin "1") (pinfunction "1_1") (pintype "bidirectional"))
      (node (ref "R5") (pin "1") (pinfunction "1_1") (pintype "passive"))
      (node (ref "U1") (pin "22") (pinfunction "DP3_22") (pintype "bidirectional"))
    )
    (net (code "27") (name "HUB_DP4") (class "Default")
      (node (ref "C11") (pin "1") (pinfunction "1_1") (pintype "bidirectional"))
      (node (ref "R9") (pin "1") (pinfunction "1_1") (pintype "passive"))
      (node (ref "U1") (pin "27") (pinfunction "DP4_27") (pintype "bidirectional"))
    )
    (net (code "28") (name "HUB_DP5") (class "Default")
      (node (ref "R65") (pin "1") (pinfunction "1_1") (pintype "passive"))
      (node (ref "U1") (pin "31") (pinfunction "DP5_31") (pintype "bidirectional"))
    )
    (net (code "29") (name "HUB_DP6") (class "Default")
      (node (ref "C13") (pin "1") (pinfunction "1_1") (pintype "bidirectional"))
      (node (ref "R11") (pin "1") (pinfunction "1_1") (pintype "passive"))
      (node (ref "U1") (pin "35") (pinfunction "DP6_35") (pintype "bidirectional"))
    )
    (net (code "30") (name "HUB_DP7") (class "Default")
      (node (ref "C9") (pin "1") (pinfunction "1_1") (pintype "bidirectional"))
      (node (ref "R7") (pin "1") (pinfunction "1_1") (pintype "passive"))
      (node (ref "U1") (pin "39") (pinfunction "DP7_39") (pintype "bidirectional"))
    )
    (net (code "31") (name "HUB_PORTDIS") (class "Default")
      (node (ref "TP30") (pin "TESTPOINT") (pinfunction "TESTPOINT_TESTPOINT") (pintype "bidirectional"))
      (node (ref "U1") (pin "42") (pinfunction "PORTDIS_42") (pintype "bidirectional"))
    )
    (net (code "32") (name "HUB_PORTPWR") (class "Default")
      (node (ref "TP29") (pin "TESTPOINT") (pinfunction "TESTPOINT_TESTPOINT") (pintype "bidirectional"))
      (node (ref "U1") (pin "41") (pinfunction "PORTPWR_41") (pintype "bidirectional"))
    )
    (net (code "33") (name "HUB_~{OVRCUR1}") (class "Default")
      (node (ref "R29") (pin "1") (pinfunction "1_1") (pintype "passive"))
      (node (ref "S14") (pin "5") (pinfunction "~{FLG}_5") (pintype "bidirectional"))
      (node (ref "TP33") (pin "TESTPOINT") (pinfunction "TESTPOINT_TESTPOINT") (pintype "bidirectional"))
      (node (ref "U1") (pin "12") (pinfunction "~{OVRCUR1}_12") (pintype "bidirectional"))
    )
    (net (code "34") (name "HUB_~{OVRCUR2}") (class "Default")
      (node (ref "R28") (pin "1") (pinfunction "1_1") (pintype "passive"))
      (node (ref "S13") (pin "5") (pinfunction "~{FLG}_5") (pintype "bidirectional"))
      (node (ref "TP35") (pin "TESTPOINT") (pinfunction "TESTPOINT_TESTPOINT") (pintype "bidirectional"))
      (node (ref "U1") (pin "16") (pinfunction "~{OVRCUR2}_16") (pintype "bidirectional"))
    )
    (net (code "35") (name "HUB_~{OVRCUR3}") (class "Default")
      (node (ref "R30") (pin "1") (pinfunction "1_1") (pintype "passive"))
      (node (ref "S15") (pin "5") (pinfunction "~{FLG}_5") (pintype "bidirectional"))
      (node (ref "TP37") (pin "TESTPOINT") (pinfunction "TESTPOINT_TESTPOINT") (pintype "bidirectional"))
      (node (ref "U1") (pin "20") (pinfunction "~{OVRCUR3}_20") (pintype "bidirectional"))
    )
    (net (code "36") (name "HUB_~{OVRCUR4}") (class "Default")
      (node (ref "R32") (pin "1") (pinfunction "1_1") (pintype "passive"))
      (node (ref "S17") (pin "5") (pinfunction "~{FLG}_5") (pintype "bidirectional"))
      (node (ref "TP39") (pin "TESTPOINT") (pinfunction "TESTPOINT_TESTPOINT") (pintype "bidirectional"))
      (node (ref "U1") (pin "25") (pinfunction "~{OVRCUR4}_25") (pintype "bidirectional"))
    )
    (net (code "37") (name "HUB_~{OVRCUR5}") (class "Default")
      (node (ref "R51") (pin "1") (pinfunction "1_1") (pintype "passive"))
      (node (ref "U1") (pin "29") (pinfunction "~{OVRCUR5}_29") (pintype "bidirectional"))
    )
    (net (code "38") (name "HUB_~{OVRCUR6}") (class "Default")
      (node (ref "R33") (pin "1") (pinfunction "1_1") (pintype "passive"))
      (node (ref "S18") (pin "5") (pinfunction "~{FLG}_5") (pintype "bidirectional"))
      (node (ref "TP41") (pin "TESTPOINT") (pinfunction "TESTPOINT_TESTPOINT") (pintype "bidirectional"))
      (node (ref "U1") (pin "33") (pinfunction "~{OVRCUR6}_33") (pintype "bidirectional"))
    )
    (net (code "39") (name "HUB_~{OVRCUR7}") (class "Default")
      (node (ref "R31") (pin "1") (pinfunction "1_1") (pintype "passive"))
      (node (ref "S16") (pin "5") (pinfunction "~{FLG}_5") (pintype "bidirectional"))
      (node (ref "TP43") (pin "TESTPOINT") (pinfunction "TESTPOINT_TESTPOINT") (pintype "bidirectional"))
      (node (ref "U1") (pin "37") (pinfunction "~{OVRCUR7}_37") (pintype "bidirectional"))
    )
    (net (code "40") (name "HUB_~{PWRON1}") (class "Default")
      (node (ref "S8") (pin "1") (pinfunction "I1_1") (pintype "bidirectional"))
      (node (ref "TP32") (pin "TESTPOINT") (pinfunction "TESTPOINT_TESTPOINT") (pintype "bidirectional"))
      (node (ref "U1") (pin "11") (pinfunction "~{PWRON1}_11") (pintype "bidirectional"))
      (node (ref "U32") (pin "10") (pinfunction "P1_10") (pintype "bidirectional"))
    )
    (net (code "41") (name "HUB_~{PWRON2}") (class "Default")
      (node (ref "S7") (pin "1") (pinfunction "I1_1") (pintype "bidirectional"))
      (node (ref "TP34") (pin "TESTPOINT") (pinfunction "TESTPOINT_TESTPOINT") (pintype "bidirectional"))
      (node (ref "U1") (pin "15") (pinfunction "~{PWRON2}_15") (pintype "bidirectional"))
      (node (ref "U32") (pin "11") (pinfunction "P2_11") (pintype "bidirectional"))
    )
    (net (code "42") (name "HUB_~{PWRON3}") (class "Default")
      (node (ref "S9") (pin "1") (pinfunction "I1_1") (pintype "bidirectional"))
      (node (ref "TP36") (pin "TESTPOINT") (pinfunction "TESTPOINT_TESTPOINT") (pintype "bidirectional"))
      (node (ref "U1") (pin "19") (pinfunction "~{PWRON3}_19") (pintype "bidirectional"))
      (node (ref "U32") (pin "12") (pinfunction "P3_12") (pintype "bidirectional"))
    )
    (net (code "43") (name "HUB_~{PWRON4}") (class "Default")
      (node (ref "S11") (pin "1") (pinfunction "I1_1") (pintype "bidirectional"))
      (node (ref "TP38") (pin "TESTPOINT") (pinfunction "TESTPOINT_TESTPOINT") (pintype "bidirectional"))
      (node (ref "U1") (pin "23") (pinfunction "~{PWRON4}_23") (pintype "bidirectional"))
      (node (ref "U32") (pin "13") (pinfunction "P4_13") (pintype "bidirectional"))
    )
    (net (code "44") (name "HUB_~{PWRON5}") (class "Default")
      (node (ref "U1") (pin "28") (pinfunction "~{PWRON5}_28") (pintype "bidirectional"))
    )
    (net (code "45") (name "HUB_~{PWRON6}") (class "Default")
      (node (ref "S12") (pin "1") (pinfunction "I1_1") (pintype "bidirectional"))
      (node (ref "TP40") (pin "TESTPOINT") (pinfunction "TESTPOINT_TESTPOINT") (pintype "bidirectional"))
      (node (ref "U1") (pin "32") (pinfunction "~{PWRON6}_32") (pintype "bidirectional"))
      (node (ref "U32") (pin "15") (pinfunction "P6_15") (pintype "bidirectional"))
    )
    (net (code "46") (name "HUB_~{PWRON7}") (class "Default")
      (node (ref "S10") (pin "1") (pinfunction "I1_1") (pintype "bidirectional"))
      (node (ref "TP42") (pin "TESTPOINT") (pinfunction "TESTPOINT_TESTPOINT") (pintype "bidirectional"))
      (node (ref "U1") (pin "36") (pinfunction "~{PWRON7}_36") (pintype "bidirectional"))
      (node (ref "U32") (pin "16") (pinfunction "P7_16") (pintype "bidirectional"))
    )
    (net (code "47") (name "MOD0_5V") (class "Default")
      (node (ref "C21") (pin "1") (pinfunction "1_1") (pintype "bidirectional"))
      (node (ref "J0") (pin "2") (pinfunction "5V_2") (pintype "bidirectional"))
      (node (ref "S1") (pin "1") (pinfunction "VLOAD_1") (pintype "bidirectional"))
    )
    (net (code "48") (name "MOD0_5V_METERED") (class "Default")
      (node (ref "C70") (pin "1") (pinfunction "1_1") (pintype "bidirectional"))
      (node (ref "C90") (pin "1") (pinfunction "1_1") (pintype "bidirectional"))
      (node (ref "J4") (pin "7") (pinfunction "VCC_MOD0_7") (pintype "power_in"))
      (node (ref "S1") (pin "3") (pinfunction "VSUPP_3") (pintype "bidirectional"))
      (node (ref "S13") (pin "2") (pinfunction "IN_2") (pintype "bidirectional"))
      (node (ref "S13") (pin "3") (pinfunction "IN_3") (pintype "bidirectional"))
      (node (ref "TP16") (pin "TESTPOINT") (pinfunction "TESTPOINT_TESTPOINT") (pintype "bidirectional"))
    )
    (net (code "49") (name "MOD0_D+_HUB-SW") (class "Default")
      (node (ref "D1") (pin "4") (pinfunction "D_4") (pintype "bidirectional"))
      (node (ref "R1") (pin "2") (pinfunction "2_2") (pintype "passive"))
      (node (ref "R53") (pin "2") (pinfunction "2_2") (pintype "passive"))
      (node (ref "U20") (pin "3") (pinfunction "D+_3") (pintype "bidirectional"))
    )
    (net (code "50") (name "MOD0_D-_HUB-SW") (class "Default")
      (node (ref "D1") (pin "2") (pinfunction "C_2") (pintype "bidirectional"))
      (node (ref "R2") (pin "2") (pinfunction "2_2") (pintype "passive"))
      (node (ref "R54") (pin "2") (pinfunction "2_2") (pintype "passive"))
      (node (ref "U20") (pin "5") (pinfunction "D-_5") (pintype "bidirectional"))
    )
    (net (code "51") (name "MOD0_IN") (class "Default")
      (node (ref "J0") (pin "10") (pinfunction "MOD_IN_10") (pintype "bidirectional"))
      (node (ref "U8") (pin "7") (pinfunction "B1_7") (pintype "bidirectional"))
    )
    (net (code "52") (name "MOD0_ISO_I2C") (class "Default")
      (node (ref "R1002") (pin "2") (pinfunction "2_2") (pintype "passive"))
      (node (ref "R68") (pin "2") (pinfunction "2_2") (pintype "passive"))
      (node (ref "TP1002") (pin "TESTPOINT") (pinfunction "TESTPOINT_TESTPOINT") (pintype "bidirectional"))
      (node (ref "U2") (pin "5") (pinfunction "OE_5") (pintype "bidirectional"))
      (node (ref "U26") (pin "10") (pinfunction "P1_10") (pintype "bidirectional"))
    )
    (net (code "53") (name "MOD0_ISO_POWER") (class "Default")
      (node (ref "R1001") (pin "2") (pinfunction "2_2") (pintype "passive"))
      (node (ref "R67") (pin "2") (pinfunction "2_2") (pintype "passive"))
      (node (ref "S1") (pin "4") (pinfunction "EN_4") (pintype "bidirectional"))
      (node (ref "TP1001") (pin "TESTPOINT") (pinfunction "TESTPOINT_TESTPOINT") (pintype "bidirectional"))
      (node (ref "U26") (pin "9") (pinfunction "P0_9") (pintype "bidirectional"))
    )
    (net (code "54") (name "MOD0_ISO_USB") (class "Default")
      (node (ref "R1003") (pin "2") (pinfunction "2_2") (pintype "passive"))
      (node (ref "R69") (pin "2") (pinfunction "2_2") (pintype "passive"))
      (node (ref "S7") (pin "6") (pinfunction "S_6") (pintype "bidirectional"))
      (node (ref "TP1003") (pin "TESTPOINT") (pinfunction "TESTPOINT_TESTPOINT") (pintype "bidirectional"))
      (node (ref "U26") (pin "11") (pinfunction "P2_11") (pintype "bidirectional"))
    )
    (net (code "55") (name "MOD0_OUT") (class "Default")
      (node (ref "J0") (pin "8") (pinfunction "MOD_OUT_8") (pintype "bidirectional"))
      (node (ref "U14") (pin "7") (pinfunction "B1_7") (pintype "bidirectional"))
    )
    (net (code "56") (name "MOD0_PPS") (class "Default")
      (node (ref "J0") (pin "7") (pinfunction "PPS_7") (pintype "bidirectional"))
      (node (ref "U8") (pin "6") (pinfunction "B2_6") (pintype "bidirectional"))
    )
    (net (code "57") (name "MOD0_SCL") (class "Default")
      (node (ref "J0") (pin "5") (pinfunction "SCL_5") (pintype "bidirectional"))
      (node (ref "R35") (pin "2") (pinfunction "2_2") (pintype "passive"))
      (node (ref "U2") (pin "6") (pinfunction "B1_6") (pintype "bidirectional"))
    )
    (net (code "58") (name "MOD0_SDA") (class "Default")
      (node (ref "J0") (pin "6") (pinfunction "SDA_6") (pintype "bidirectional"))
      (node (ref "R34") (pin "2") (pinfunction "2_2") (pintype "passive"))
      (node (ref "U2") (pin "7") (pinfunction "B0_7") (pintype "bidirectional"))
    )
    (net (code "59") (name "MOD0_USB+") (class "Default")
      (node (ref "J0") (pin "11") (pinfunction "USB_D+_11") (pintype "bidirectional"))
      (node (ref "U20") (pin "1") (pinfunction "D1+_1") (pintype "bidirectional"))
    )
    (net (code "60") (name "MOD0_USB-") (class "Default")
      (node (ref "J0") (pin "12") (pinfunction "USB_D-_12") (pintype "bidirectional"))
      (node (ref "U20") (pin "7") (pinfunction "D1-_7") (pintype "bidirectional"))
    )
    (net (code "61") (name "MOD0_USB_VBUS") (class "Default")
      (node (ref "C58") (pin "1") (pinfunction "1_1") (pintype "bidirectional"))
      (node (ref "C97") (pin "1") (pinfunction "1_1") (pintype "passive"))
      (node (ref "J0") (pin "13") (pinfunction "USB_VBUS_13") (pintype "bidirectional"))
      (node (ref "S13") (pin "6") (pinfunction "OUT_6") (pintype "bidirectional"))
      (node (ref "S13") (pin "7") (pinfunction "OUT_7") (pintype "bidirectional"))
    )
    (net (code "62") (name "MOD0_USB_~{EN}") (class "Default")
      (node (ref "S13") (pin "4") (pinfunction "~{EN}_4") (pintype "bidirectional"))
      (node (ref "S7") (pin "4") (pinfunction "Z_4") (pintype "bidirectional"))
      (node (ref "U20") (pin "8") (pinfunction "~{OE}_8") (pintype "bidirectional"))
    )
    (net (code "63") (name "MOD0_VCCIO") (class "Default")
      (node (ref "C39") (pin "1") (pinfunction "1_1") (pintype "bidirectional"))
      (node (ref "C45") (pin "1") (pinfunction "1_1") (pintype "bidirectional"))
      (node (ref "C82") (pin "1") (pinfunction "1_1") (pintype "bidirectional"))
      (node (ref "J0") (pin "4") (pinfunction "VCCIO_4") (pintype "bidirectional"))
      (node (ref "R34") (pin "1") (pinfunction "1_1") (pintype "passive"))
      (node (ref "R35") (pin "1") (pinfunction "1_1") (pintype "passive"))
      (node (ref "U14") (pin "8") (pinfunction "VCC_B_8") (pintype "bidirectional"))
      (node (ref "U2") (pin "8") (pinfunction "VCC_B_8") (pintype "bidirectional"))
      (node (ref "U8") (pin "8") (pinfunction "VCC_B_8") (pintype "bidirectional"))
    )
    (net (code "64") (name "MOD1_5V") (class "Default")
      (node (ref "C22") (pin "1") (pinfunction "1_1") (pintype "bidirectional"))
      (node (ref "J1") (pin "2") (pinfunction "5V_2") (pintype "bidirectional"))
      (node (ref "S2") (pin "1") (pinfunction "VLOAD_1") (pintype "bidirectional"))
    )
    (net (code "65") (name "MOD1_5V_METERED") (class "Default")
      (node (ref "C71") (pin "1") (pinfunction "1_1") (pintype "bidirectional"))
      (node (ref "C91") (pin "1") (pinfunction "1_1") (pintype "bidirectional"))
      (node (ref "J4") (pin "8") (pinfunction "VCC_MOD1_8") (pintype "power_in"))
      (node (ref "S14") (pin "2") (pinfunction "IN_2") (pintype "bidirectional"))
      (node (ref "S14") (pin "3") (pinfunction "IN_3") (pintype "bidirectional"))
      (node (ref "S2") (pin "3") (pinfunction "VSUPP_3") (pintype "bidirectional"))
      (node (ref "TP17") (pin "TESTPOINT") (pinfunction "TESTPOINT_TESTPOINT") (pintype "bidirectional"))
    )
    (net (code "66") (name "MOD1_D+_HUB-SW") (class "Default")
      (node (ref "D1") (pin "8") (pinfunction "A_8") (pintype "bidirectional"))
      (node (ref "R3") (pin "2") (pinfunction "2_2") (pintype "passive"))
      (node (ref "R55") (pin "2") (pinfunction "2_2") (pintype "passive"))
      (node (ref "U21") (pin "3") (pinfunction "D+_3") (pintype "bidirectional"))
    )
    (net (code "67") (name "MOD1_D-_HUB-SW") (class "Default")
      (node (ref "D1") (pin "6") (pinfunction "B_6") (pintype "bidirectional"))
      (node (ref "R4") (pin "2") (pinfunction "2_2") (pintype "passive"))
      (node (ref "R56") (pin "2") (pinfunction "2_2") (pintype "passive"))
      (node (ref "U21") (pin "5") (pinfunction "D-_5") (pintype "bidirectional"))
    )
    (net (code "68") (name "MOD1_IN") (class "Default")
      (node (ref "J1") (pin "10") (pinfunction "MOD_IN_10") (pintype "bidirectional"))
      (node (ref "U9") (pin "7") (pinfunction "B1_7") (pintype "bidirectional"))
    )
    (net (code "69") (name "MOD1_ISO_I2C") (class "Default")
      (node (ref "LED1005") (pin "A") (pinfunction "ANODE_A") (pintype "bidirectional"))
      (node (ref "R71") (pin "2") (pinfunction "2_2") (pintype "passive"))
      (node (ref "TP1005") (pin "TESTPOINT") (pinfunction "TESTPOINT_TESTPOINT") (pintype "bidirectional"))
      (node (ref "U27") (pin "10") (pinfunction "P1_10") (pintype "bidirectional"))
      (node (ref "U3") (pin "5") (pinfunction "OE_5") (pintype "bidirectional"))
    )
    (net (code "70") (name "MOD1_ISO_POWER") (class "Default")
      (node (ref "LED1004") (pin "A") (pinfunction "ANODE_A") (pintype "bidirectional"))
      (node (ref "R70") (pin "2") (pinfunction "2_2") (pintype "passive"))
      (node (ref "S2") (pin "4") (pinfunction "EN_4") (pintype "bidirectional"))
      (node (ref "TP1004") (pin "TESTPOINT") (pinfunction "TESTPOINT_TESTPOINT") (pintype "bidirectional"))
      (node (ref "U27") (pin "9") (pinfunction "P0_9") (pintype "bidirectional"))
    )
    (net (code "71") (name "MOD1_ISO_USB") (class "Default")
      (node (ref "LED1006") (pin "A") (pinfunction "ANODE_A") (pintype "bidirectional"))
      (node (ref "R72") (pin "2") (pinfunction "2_2") (pintype "passive"))
      (node (ref "S8") (pin "6") (pinfunction "S_6") (pintype "bidirectional"))
      (node (ref "TP1006") (pin "TESTPOINT") (pinfunction "TESTPOINT_TESTPOINT") (pintype "bidirectional"))
      (node (ref "U27") (pin "11") (pinfunction "P2_11") (pintype "bidirectional"))
    )
    (net (code "72") (name "MOD1_OUT") (class "Default")
      (node (ref "J1") (pin "8") (pinfunction "MOD_OUT_8") (pintype "bidirectional"))
      (node (ref "U15") (pin "7") (pinfunction "B1_7") (pintype "bidirectional"))
    )
    (net (code "73") (name "MOD1_PPS") (class "Default")
      (node (ref "J1") (pin "7") (pinfunction "PPS_7") (pintype "bidirectional"))
      (node (ref "U9") (pin "6") (pinfunction "B2_6") (pintype "bidirectional"))
    )
    (net (code "74") (name "MOD1_SCL") (class "Default")
      (node (ref "J1") (pin "5") (pinfunction "SCL_5") (pintype "bidirectional"))
      (node (ref "R37") (pin "2") (pinfunction "2_2") (pintype "passive"))
      (node (ref "U3") (pin "6") (pinfunction "B1_6") (pintype "bidirectional"))
    )
    (net (code "75") (name "MOD1_SDA") (class "Default")
      (node (ref "J1") (pin "6") (pinfunction "SDA_6") (pintype "bidirectional"))
      (node (ref "R36") (pin "2") (pinfunction "2_2") (pintype "passive"))
      (node (ref "U3") (pin "7") (pinfunction "B0_7") (pintype "bidirectional"))
    )
    (net (code "76") (name "MOD1_USB+") (class "Default")
      (node (ref "J1") (pin "11") (pinfunction "USB_D+_11") (pintype "bidirectional"))
      (node (ref "U21") (pin "1") (pinfunction "D1+_1") (pintype "bidirectional"))
    )
    (net (code "77") (name "MOD1_USB-") (class "Default")
      (node (ref "J1") (pin "12") (pinfunction "USB_D-_12") (pintype "bidirectional"))
      (node (ref "U21") (pin "7") (pinfunction "D1-_7") (pintype "bidirectional"))
    )
    (net (code "78") (name "MOD1_USB_VBUS") (class "Default")
      (node (ref "C59") (pin "1") (pinfunction "1_1") (pintype "bidirectional"))
      (node (ref "C98") (pin "1") (pinfunction "1_1") (pintype "passive"))
      (node (ref "J1") (pin "13") (pinfunction "USB_VBUS_13") (pintype "bidirectional"))
      (node (ref "S14") (pin "6") (pinfunction "OUT_6") (pintype "bidirectional"))
      (node (ref "S14") (pin "7") (pinfunction "OUT_7") (pintype "bidirectional"))
    )
    (net (code "79") (name "MOD1_USB_~{EN}") (class "Default")
      (node (ref "S14") (pin "4") (pinfunction "~{EN}_4") (pintype "bidirectional"))
      (node (ref "S8") (pin "4") (pinfunction "Z_4") (pintype "bidirectional"))
      (node (ref "U21") (pin "8") (pinfunction "~{OE}_8") (pintype "bidirectional"))
    )
    (net (code "80") (name "MOD1_VCCIO") (class "Default")
      (node (ref "C40") (pin "1") (pinfunction "1_1") (pintype "bidirectional"))
      (node (ref "C46") (pin "1") (pinfunction "1_1") (pintype "bidirectional"))
      (node (ref "C83") (pin "1") (pinfunction "1_1") (pintype "bidirectional"))
      (node (ref "J1") (pin "4") (pinfunction "VCCIO_4") (pintype "bidirectional"))
      (node (ref "R36") (pin "1") (pinfunction "1_1") (pintype "passive"))
      (node (ref "R37") (pin "1") (pinfunction "1_1") (pintype "passive"))
      (node (ref "U15") (pin "8") (pinfunction "VCC_B_8") (pintype "bidirectional"))
      (node (ref "U3") (pin "8") (pinfunction "VCC_B_8") (pintype "bidirectional"))
      (node (ref "U9") (pin "8") (pinfunction "VCC_B_8") (pintype "bidirectional"))
    )
    (net (code "81") (name "MOD2_5V") (class "Default")
      (node (ref "C23") (pin "1") (pinfunction "1_1") (pintype "bidirectional"))
      (node (ref "J2") (pin "2") (pinfunction "5V_2") (pintype "bidirectional"))
      (node (ref "S3") (pin "1") (pinfunction "VLOAD_1") (pintype "bidirectional"))
    )
    (net (code "82") (name "MOD2_5V_METERED") (class "Default")
      (node (ref "C72") (pin "1") (pinfunction "1_1") (pintype "bidirectional"))
      (node (ref "C92") (pin "1") (pinfunction "1_1") (pintype "bidirectional"))
      (node (ref "J4") (pin "9") (pinfunction "VCC_MOD2_9") (pintype "power_in"))
      (node (ref "S15") (pin "2") (pinfunction "IN_2") (pintype "bidirectional"))
      (node (ref "S15") (pin "3") (pinfunction "IN_3") (pintype "bidirectional"))
      (node (ref "S3") (pin "3") (pinfunction "VSUPP_3") (pintype "bidirectional"))
      (node (ref "TP18") (pin "TESTPOINT") (pinfunction "TESTPOINT_TESTPOINT") (pintype "bidirectional"))
    )
    (net (code "83") (name "MOD2_D+_HUB-SW") (class "Default")
      (node (ref "D2") (pin "8") (pinfunction "A_8") (pintype "bidirectional"))
      (node (ref "R5") (pin "2") (pinfunction "2_2") (pintype "passive"))
      (node (ref "R57") (pin "2") (pinfunction "2_2") (pintype "passive"))
      (node (ref "U22") (pin "3") (pinfunction "D+_3") (pintype "bidirectional"))
    )
    (net (code "84") (name "MOD2_D-_HUB-SW") (class "Default")
      (node (ref "D2") (pin "6") (pinfunction "B_6") (pintype "bidirectional"))
      (node (ref "R58") (pin "2") (pinfunction "2_2") (pintype "passive"))
      (node (ref "R6") (pin "2") (pinfunction "2_2") (pintype "passive"))
      (node (ref "U22") (pin "5") (pinfunction "D-_5") (pintype "bidirectional"))
    )
    (net (code "85") (name "MOD2_IN") (class "Default")
      (node (ref "J2") (pin "10") (pinfunction "MOD_IN_10") (pintype "bidirectional"))
      (node (ref "U10") (pin "7") (pinfunction "B1_7") (pintype "bidirectional"))
    )
    (net (code "86") (name "MOD2_ISO_I2C") (class "Default")
      (node (ref "R1008") (pin "2") (pinfunction "2_2") (pintype "passive"))
      (node (ref "R74") (pin "2") (pinfunction "2_2") (pintype "passive"))
      (node (ref "TP1008") (pin "TESTPOINT") (pinfunction "TESTPOINT_TESTPOINT") (pintype "bidirectional"))
      (node (ref "U28") (pin "10") (pinfunction "P1_10") (pintype "bidirectional"))
      (node (ref "U4") (pin "5") (pinfunction "OE_5") (pintype "bidirectional"))
    )
    (net (code "87") (name "MOD2_ISO_POWER") (class "Default")
      (node (ref "R1007") (pin "2") (pinfunction "2_2") (pintype "passive"))
      (node (ref "R73") (pin "2") (pinfunction "2_2") (pintype "passive"))
      (node (ref "S3") (pin "4") (pinfunction "EN_4") (pintype "bidirectional"))
      (node (ref "TP1007") (pin "TESTPOINT") (pinfunction "TESTPOINT_TESTPOINT") (pintype "bidirectional"))
      (node (ref "U28") (pin "9") (pinfunction "P0_9") (pintype "bidirectional"))
    )
    (net (code "88") (name "MOD2_ISO_USB") (class "Default")
      (node (ref "R1009") (pin "2") (pinfunction "2_2") (pintype "passive"))
      (node (ref "R75") (pin "2") (pinfunction "2_2") (pintype "passive"))
      (node (ref "S9") (pin "6") (pinfunction "S_6") (pintype "bidirectional"))
      (node (ref "TP1009") (pin "TESTPOINT") (pinfunction "TESTPOINT_TESTPOINT") (pintype "bidirectional"))
      (node (ref "U28") (pin "11") (pinfunction "P2_11") (pintype "bidirectional"))
    )
    (net (code "89") (name "MOD2_OUT") (class "Default")
      (node (ref "J2") (pin "8") (pinfunction "MOD_OUT_8") (pintype "bidirectional"))
      (node (ref "U16") (pin "7") (pinfunction "B1_7") (pintype "bidirectional"))
    )
    (net (code "90") (name "MOD2_PPS") (class "Default")
      (node (ref "J2") (pin "7") (pinfunction "PPS_7") (pintype "bidirectional"))
      (node (ref "U10") (pin "6") (pinfunction "B2_6") (pintype "bidirectional"))
    )
    (net (code "91") (name "MOD2_SCL") (class "Default")
      (node (ref "J2") (pin "5") (pinfunction "SCL_5") (pintype "bidirectional"))
      (node (ref "R39") (pin "2") (pinfunction "2_2") (pintype "passive"))
      (node (ref "U4") (pin "6") (pinfunction "B1_6") (pintype "bidirectional"))
    )
    (net (code "92") (name "MOD2_SDA") (class "Default")
      (node (ref "J2") (pin "6") (pinfunction "SDA_6") (pintype "bidirectional"))
      (node (ref "R38") (pin "2") (pinfunction "2_2") (pintype "passive"))
      (node (ref "U4") (pin "7") (pinfunction "B0_7") (pintype "bidirectional"))
    )
    (net (code "93") (name "MOD2_USB+") (class "Default")
      (node (ref "J2") (pin "11") (pinfunction "USB_D+_11") (pintype "bidirectional"))
      (node (ref "U22") (pin "1") (pinfunction "D1+_1") (pintype "bidirectional"))
    )
    (net (code "94") (name "MOD2_USB-") (class "Default")
      (node (ref "J2") (pin "12") (pinfunction "USB_D-_12") (pintype "bidirectional"))
      (node (ref "U22") (pin "7") (pinfunction "D1-_7") (pintype "bidirectional"))
    )
    (net (code "95") (name "MOD2_USB_VBUS") (class "Default")
      (node (ref "C60") (pin "1") (pinfunction "1_1") (pintype "bidirectional"))
      (node (ref "C99") (pin "1") (pinfunction "1_1") (pintype "passive"))
      (node (ref "J2") (pin "13") (pinfunction "USB_VBUS_13") (pintype "bidirectional"))
      (node (ref "S15") (pin "6") (pinfunction "OUT_6") (pintype "bidirectional"))
      (node (ref "S15") (pin "7") (pinfunction "OUT_7") (pintype "bidirectional"))
    )
    (net (code "96") (name "MOD2_USB_~{EN}") (class "Default")
      (node (ref "S15") (pin "4") (pinfunction "~{EN}_4") (pintype "bidirectional"))
      (node (ref "S9") (pin "4") (pinfunction "Z_4") (pintype "bidirectional"))
      (node (ref "U22") (pin "8") (pinfunction "~{OE}_8") (pintype "bidirectional"))
    )
    (net (code "97") (name "MOD2_VCCIO") (class "Default")
      (node (ref "C41") (pin "1") (pinfunction "1_1") (pintype "bidirectional"))
      (node (ref "C47") (pin "1") (pinfunction "1_1") (pintype "bidirectional"))
      (node (ref "C84") (pin "1") (pinfunction "1_1") (pintype "bidirectional"))
      (node (ref "J2") (pin "4") (pinfunction "VCCIO_4") (pintype "bidirectional"))
      (node (ref "R38") (pin "1") (pinfunction "1_1") (pintype "passive"))
      (node (ref "R39") (pin "1") (pinfunction "1_1") (pintype "passive"))
      (node (ref "U10") (pin "8") (pinfunction "VCC_B_8") (pintype "bidirectional"))
      (node (ref "U16") (pin "8") (pinfunction "VCC_B_8") (pintype "bidirectional"))
      (node (ref "U4") (pin "8") (pinfunction "VCC_B_8") (pintype "bidirectional"))
    )
    (net (code "98") (name "MOD5_5V") (class "Default")
      (node (ref "C24") (pin "1") (pinfunction "1_1") (pintype "bidirectional"))
      (node (ref "J5") (pin "2") (pinfunction "5V_2") (pintype "bidirectional"))
      (node (ref "S4") (pin "1") (pinfunction "VLOAD_1") (pintype "bidirectional"))
    )
    (net (code "99") (name "MOD5_5V_METERED") (class "Default")
      (node (ref "C73") (pin "1") (pinfunction "1_1") (pintype "bidirectional"))
      (node (ref "C93") (pin "1") (pinfunction "1_1") (pintype "bidirectional"))
      (node (ref "J4") (pin "10") (pinfunction "VCC_MOD5_10") (pintype "power_in"))
      (node (ref "S16") (pin "2") (pinfunction "IN_2") (pintype "bidirectional"))
      (node (ref "S16") (pin "3") (pinfunction "IN_3") (pintype "bidirectional"))
      (node (ref "S4") (pin "3") (pinfunction "VSUPP_3") (pintype "bidirectional"))
      (node (ref "TP19") (pin "TESTPOINT") (pinfunction "TESTPOINT_TESTPOINT") (pintype "bidirectional"))
    )
    (net (code "100") (name "MOD5_D+_HUB-SW") (class "Default")
      (node (ref "D3") (pin "2") (pinfunction "C_2") (pintype "bidirectional"))
      (node (ref "R59") (pin "2") (pinfunction "2_2") (pintype "passive"))
      (node (ref "R7") (pin "2") (pinfunction "2_2") (pintype "passive"))
      (node (ref "U23") (pin "3") (pinfunction "D+_3") (pintype "bidirectional"))
    )
    (net (code "101") (name "MOD5_D-_HUB-SW") (class "Default")
      (node (ref "D3") (pin "4") (pinfunction "D_4") (pintype "bidirectional"))
      (node (ref "R60") (pin "2") (pinfunction "2_2") (pintype "passive"))
      (node (ref "R8") (pin "2") (pinfunction "2_2") (pintype "passive"))
      (node (ref "U23") (pin "5") (pinfunction "D-_5") (pintype "bidirectional"))
    )
    (net (code "102") (name "MOD5_IN") (class "Default")
      (node (ref "J5") (pin "10") (pinfunction "MOD_IN_10") (pintype "bidirectional"))
      (node (ref "U11") (pin "7") (pinfunction "B1_7") (pintype "bidirectional"))
    )
    (net (code "103") (name "MOD5_ISO_I2C") (class "Default")
      (node (ref "LED1011") (pin "A") (pinfunction "ANODE_A") (pintype "bidirectional"))
      (node (ref "R77") (pin "2") (pinfunction "2_2") (pintype "passive"))
      (node (ref "TP1011") (pin "TESTPOINT") (pinfunction "TESTPOINT_TESTPOINT") (pintype "bidirectional"))
      (node (ref "U29") (pin "10") (pinfunction "P1_10") (pintype "bidirectional"))
      (node (ref "U5") (pin "5") (pinfunction "OE_5") (pintype "bidirectional"))
    )
    (net (code "104") (name "MOD5_ISO_POWER") (class "Default")
      (node (ref "LED1010") (pin "A") (pinfunction "ANODE_A") (pintype "bidirectional"))
      (node (ref "R76") (pin "2") (pinfunction "2_2") (pintype "passive"))
      (node (ref "S4") (pin "4") (pinfunction "EN_4") (pintype "bidirectional"))
      (node (ref "TP1010") (pin "TESTPOINT") (pinfunction "TESTPOINT_TESTPOINT") (pintype "bidirectional"))
      (node (ref "U29") (pin "9") (pinfunction "P0_9") (pintype "bidirectional"))
    )
    (net (code "105") (name "MOD5_ISO_USB") (class "Default")
      (node (ref "LED1012") (pin "A") (pinfunction "ANODE_A") (pintype "bidirectional"))
      (node (ref "R78") (pin "2") (pinfunction "2_2") (pintype "passive"))
      (node (ref "S10") (pin "6") (pinfunction "S_6") (pintype "bidirectional"))
      (node (ref "TP1012") (pin "TESTPOINT") (pinfunction "TESTPOINT_TESTPOINT") (pintype "bidirectional"))
      (node (ref "U29") (pin "11") (pinfunction "P2_11") (pintype "bidirectional"))
    )
    (net (code "106") (name "MOD5_OUT") (class "Default")
      (node (ref "J5") (pin "8") (pinfunction "MOD_OUT_8") (pintype "bidirectional"))
      (node (ref "U17") (pin "7") (pinfunction "B1_7") (pintype "bidirectional"))
    )
    (net (code "107") (name "MOD5_PPS") (class "Default")
      (node (ref "J5") (pin "7") (pinfunction "PPS_7") (pintype "bidirectional"))
      (node (ref "U11") (pin "6") (pinfunction "B2_6") (pintype "bidirectional"))
    )
    (net (code "108") (name "MOD5_SCL") (class "Default")
      (node (ref "J5") (pin "5") (pinfunction "SCL_5") (pintype "bidirectional"))
      (node (ref "R41") (pin "2") (pinfunction "2_2") (pintype "passive"))
      (node (ref "U5") (pin "6") (pinfunction "B1_6") (pintype "bidirectional"))
    )
    (net (code "109") (name "MOD5_SDA") (class "Default")
      (node (ref "J5") (pin "6") (pinfunction "SDA_6") (pintype "bidirectional"))
      (node (ref "R40") (pin "2") (pinfunction "2_2") (pintype "passive"))
      (node (ref "U5") (pin "7") (pinfunction "B0_7") (pintype "bidirectional"))
    )
    (net (code "110") (name "MOD5_USB+") (class "Default")
      (node (ref "J5") (pin "11") (pinfunction "USB_D+_11") (pintype "bidirectional"))
      (node (ref "U23") (pin "1") (pinfunction "D1+_1") (pintype "bidirectional"))
    )
    (net (code "111") (name "MOD5_USB-") (class "Default")
      (node (ref "J5") (pin "12") (pinfunction "USB_D-_12") (pintype "bidirectional"))
      (node (ref "U23") (pin "7") (pinfunction "D1-_7") (pintype "bidirectional"))
    )
    (net (code "112") (name "MOD5_USB_VBUS") (class "Default")
      (node (ref "C100") (pin "1") (pinfunction "1_1") (pintype "passive"))
      (node (ref "C61") (pin "1") (pinfunction "1_1") (pintype "bidirectional"))
      (node (ref "J5") (pin "13") (pinfunction "USB_VBUS_13") (pintype "bidirectional"))
      (node (ref "S16") (pin "6") (pinfunction "OUT_6") (pintype "bidirectional"))
      (node (ref "S16") (pin "7") (pinfunction "OUT_7") (pintype "bidirectional"))
    )
    (net (code "113") (name "MOD5_USB_~{EN}") (class "Default")
      (node (ref "S10") (pin "4") (pinfunction "Z_4") (pintype "bidirectional"))
      (node (ref "S16") (pin "4") (pinfunction "~{EN}_4") (pintype "bidirectional"))
      (node (ref "U23") (pin "8") (pinfunction "~{OE}_8") (pintype "bidirectional"))
    )
    (net (code "114") (name "MOD5_VCCIO") (class "Default")
      (node (ref "C42") (pin "1") (pinfunction "1_1") (pintype "bidirectional"))
      (node (ref "C48") (pin "1") (pinfunction "1_1") (pintype "bidirectional"))
      (node (ref "C85") (pin "1") (pinfunction "1_1") (pintype "bidirectional"))
      (node (ref "J5") (pin "4") (pinfunction "VCCIO_4") (pintype "bidirectional"))
      (node (ref "R40") (pin "1") (pinfunction "1_1") (pintype "passive"))
      (node (ref "R41") (pin "1") (pinfunction "1_1") (pintype "passive"))
      (node (ref "U11") (pin "8") (pinfunction "VCC_B_8") (pintype "bidirectional"))
      (node (ref "U17") (pin "8") (pinfunction "VCC_B_8") (pintype "bidirectional"))
      (node (ref "U5") (pin "8") (pinfunction "VCC_B_8") (pintype "bidirectional"))
    )
    (net (code "115") (name "MOD6_5V") (class "Default")
      (node (ref "C25") (pin "1") (pinfunction "1_1") (pintype "bidirectional"))
      (node (ref "J6") (pin "2") (pinfunction "5V_2") (pintype "bidirectional"))
      (node (ref "S5") (pin "1") (pinfunction "VLOAD_1") (pintype "bidirectional"))
    )
    (net (code "116") (name "MOD6_5V_METERED") (class "Default")
      (node (ref "C74") (pin "1") (pinfunction "1_1") (pintype "bidirectional"))
      (node (ref "C94") (pin "1") (pinfunction "1_1") (pintype "bidirectional"))
      (node (ref "J4") (pin "11") (pinfunction "VCC_MOD6_11") (pintype "power_in"))
      (node (ref "S17") (pin "2") (pinfunction "IN_2") (pintype "bidirectional"))
      (node (ref "S17") (pin "3") (pinfunction "IN_3") (pintype "bidirectional"))
      (node (ref "S5") (pin "3") (pinfunction "VSUPP_3") (pintype "bidirectional"))
      (node (ref "TP20") (pin "TESTPOINT") (pinfunction "TESTPOINT_TESTPOINT") (pintype "bidirectional"))
    )
    (net (code "117") (name "MOD6_D+_HUB-SW") (class "Default")
      (node (ref "D4") (pin "8") (pinfunction "A_8") (pintype "bidirectional"))
      (node (ref "R61") (pin "2") (pinfunction "2_2") (pintype "passive"))
      (node (ref "R9") (pin "2") (pinfunction "2_2") (pintype "passive"))
      (node (ref "U24") (pin "3") (pinfunction "D+_3") (pintype "bidirectional"))
    )
    (net (code "118") (name "MOD6_D-_HUB-SW") (class "Default")
      (node (ref "D4") (pin "6") (pinfunction "B_6") (pintype "bidirectional"))
      (node (ref "R10") (pin "2") (pinfunction "2_2") (pintype "passive"))
      (node (ref "R62") (pin "2") (pinfunction "2_2") (pintype "passive"))
      (node (ref "U24") (pin "5") (pinfunction "D-_5") (pintype "bidirectional"))
    )
    (net (code "119") (name "MOD6_IN") (class "Default")
      (node (ref "J6") (pin "10") (pinfunction "MOD_IN_10") (pintype "bidirectional"))
      (node (ref "U12") (pin "7") (pinfunction "B1_7") (pintype "bidirectional"))
    )
    (net (code "120") (name "MOD6_ISO_I2C") (class "Default")
      (node (ref "R1014") (pin "2") (pinfunction "2_2") (pintype "passive"))
      (node (ref "R80") (pin "2") (pinfunction "2_2") (pintype "passive"))
      (node (ref "TP1014") (pin "TESTPOINT") (pinfunction "TESTPOINT_TESTPOINT") (pintype "bidirectional"))
      (node (ref "U30") (pin "10") (pinfunction "P1_10") (pintype "bidirectional"))
      (node (ref "U6") (pin "5") (pinfunction "OE_5") (pintype "bidirectional"))
    )
    (net (code "121") (name "MOD6_ISO_POWER") (class "Default")
      (node (ref "R1013") (pin "2") (pinfunction "2_2") (pintype "passive"))
      (node (ref "R79") (pin "2") (pinfunction "2_2") (pintype "passive"))
      (node (ref "S5") (pin "4") (pinfunction "EN_4") (pintype "bidirectional"))
      (node (ref "TP1013") (pin "TESTPOINT") (pinfunction "TESTPOINT_TESTPOINT") (pintype "bidirectional"))
      (node (ref "U30") (pin "9") (pinfunction "P0_9") (pintype "bidirectional"))
    )
    (net (code "122") (name "MOD6_ISO_USB") (class "Default")
      (node (ref "R1015") (pin "2") (pinfunction "2_2") (pintype "passive"))
      (node (ref "R81") (pin "2") (pinfunction "2_2") (pintype "passive"))
      (node (ref "S11") (pin "6") (pinfunction "S_6") (pintype "bidirectional"))
      (node (ref "TP1015") (pin "TESTPOINT") (pinfunction "TESTPOINT_TESTPOINT") (pintype "bidirectional"))
      (node (ref "U30") (pin "11") (pinfunction "P2_11") (pintype "bidirectional"))
    )
    (net (code "123") (name "MOD6_OUT") (class "Default")
      (node (ref "J6") (pin "8") (pinfunction "MOD_OUT_8") (pintype "bidirectional"))
      (node (ref "U18") (pin "7") (pinfunction "B1_7") (pintype "bidirectional"))
    )
    (net (code "124") (name "MOD6_PPS") (class "Default")
      (node (ref "J6") (pin "7") (pinfunction "PPS_7") (pintype "bidirectional"))
      (node (ref "U12") (pin "6") (pinfunction "B2_6") (pintype "bidirectional"))
    )
    (net (code "125") (name "MOD6_SCL") (class "Default")
      (node (ref "J6") (pin "5") (pinfunction "SCL_5") (pintype "bidirectional"))
      (node (ref "R43") (pin "2") (pinfunction "2_2") (pintype "passive"))
      (node (ref "U6") (pin "6") (pinfunction "B1_6") (pintype "bidirectional"))
    )
    (net (code "126") (name "MOD6_SDA") (class "Default")
      (node (ref "J6") (pin "6") (pinfunction "SDA_6") (pintype "bidirectional"))
      (node (ref "R42") (pin "2") (pinfunction "2_2") (pintype "passive"))
      (node (ref "U6") (pin "7") (pinfunction "B0_7") (pintype "bidirectional"))
    )
    (net (code "127") (name "MOD6_USB+") (class "Default")
      (node (ref "J6") (pin "11") (pinfunction "USB_D+_11") (pintype "bidirectional"))
      (node (ref "U24") (pin "1") (pinfunction "D1+_1") (pintype "bidirectional"))
    )
    (net (code "128") (name "MOD6_USB-") (class "Default")
      (node (ref "J6") (pin "12") (pinfunction "USB_D-_12") (pintype "bidirectional"))
      (node (ref "U24") (pin "7") (pinfunction "D1-_7") (pintype "bidirectional"))
    )
    (net (code "129") (name "MOD6_USB_VBUS") (class "Default")
      (node (ref "C101") (pin "1") (pinfunction "1_1") (pintype "passive"))
      (node (ref "C62") (pin "1") (pinfunction "1_1") (pintype "bidirectional"))
      (node (ref "J6") (pin "13") (pinfunction "USB_VBUS_13") (pintype "bidirectional"))
      (node (ref "S17") (pin "6") (pinfunction "OUT_6") (pintype "bidirectional"))
      (node (ref "S17") (pin "7") (pinfunction "OUT_7") (pintype "bidirectional"))
    )
    (net (code "130") (name "MOD6_USB_~{EN}") (class "Default")
      (node (ref "S11") (pin "4") (pinfunction "Z_4") (pintype "bidirectional"))
      (node (ref "S17") (pin "4") (pinfunction "~{EN}_4") (pintype "bidirectional"))
      (node (ref "U24") (pin "8") (pinfunction "~{OE}_8") (pintype "bidirectional"))
    )
    (net (code "131") (name "MOD6_VCCIO") (class "Default")
      (node (ref "C43") (pin "1") (pinfunction "1_1") (pintype "bidirectional"))
      (node (ref "C49") (pin "1") (pinfunction "1_1") (pintype "bidirectional"))
      (node (ref "C86") (pin "1") (pinfunction "1_1") (pintype "bidirectional"))
      (node (ref "J6") (pin "4") (pinfunction "VCCIO_4") (pintype "bidirectional"))
      (node (ref "R42") (pin "1") (pinfunction "1_1") (pintype "passive"))
      (node (ref "R43") (pin "1") (pinfunction "1_1") (pintype "passive"))
      (node (ref "U12") (pin "8") (pinfunction "VCC_B_8") (pintype "bidirectional"))
      (node (ref "U18") (pin "8") (pinfunction "VCC_B_8") (pintype "bidirectional"))
      (node (ref "U6") (pin "8") (pinfunction "VCC_B_8") (pintype "bidirectional"))
    )
    (net (code "132") (name "MOD7_5V") (class "Default")
      (node (ref "C26") (pin "1") (pinfunction "1_1") (pintype "bidirectional"))
      (node (ref "J7") (pin "2") (pinfunction "5V_2") (pintype "bidirectional"))
      (node (ref "S6") (pin "1") (pinfunction "VLOAD_1") (pintype "bidirectional"))
    )
    (net (code "133") (name "MOD7_5V_METERED") (class "Default")
      (node (ref "C75") (pin "1") (pinfunction "1_1") (pintype "bidirectional"))
      (node (ref "C95") (pin "1") (pinfunction "1_1") (pintype "bidirectional"))
      (node (ref "J4") (pin "12") (pinfunction "VCC_MOD7_12") (pintype "power_in"))
      (node (ref "S18") (pin "2") (pinfunction "IN_2") (pintype "bidirectional"))
      (node (ref "S18") (pin "3") (pinfunction "IN_3") (pintype "bidirectional"))
      (node (ref "S6") (pin "3") (pinfunction "VSUPP_3") (pintype "bidirectional"))
      (node (ref "TP21") (pin "TESTPOINT") (pinfunction "TESTPOINT_TESTPOINT") (pintype "bidirectional"))
    )
    (net (code "134") (name "MOD7_D+_HUB-SW") (class "Default")
      (node (ref "D4") (pin "4") (pinfunction "D_4") (pintype "bidirectional"))
      (node (ref "R11") (pin "2") (pinfunction "2_2") (pintype "passive"))
      (node (ref "R63") (pin "2") (pinfunction "2_2") (pintype "passive"))
      (node (ref "U25") (pin "3") (pinfunction "D+_3") (pintype "bidirectional"))
    )
    (net (code "135") (name "MOD7_D-_HUB-SW") (class "Default")
      (node (ref "D4") (pin "2") (pinfunction "C_2") (pintype "bidirectional"))
      (node (ref "R12") (pin "2") (pinfunction "2_2") (pintype "passive"))
      (node (ref "R64") (pin "2") (pinfunction "2_2") (pintype "passive"))
      (node (ref "U25") (pin "5") (pinfunction "D-_5") (pintype "bidirectional"))
    )
    (net (code "136") (name "MOD7_IN") (class "Default")
      (node (ref "J7") (pin "10") (pinfunction "MOD_IN_10") (pintype "bidirectional"))
      (node (ref "U13") (pin "7") (pinfunction "B1_7") (pintype "bidirectional"))
    )
    (net (code "137") (name "MOD7_ISO_I2C") (class "Default")
      (node (ref "LED1017") (pin "A") (pinfunction "ANODE_A") (pintype "bidirectional"))
      (node (ref "R83") (pin "2") (pinfunction "2_2") (pintype "passive"))
      (node (ref "TP1017") (pin "TESTPOINT") (pinfunction "TESTPOINT_TESTPOINT") (pintype "bidirectional"))
      (node (ref "U31") (pin "10") (pinfunction "P1_10") (pintype "bidirectional"))
      (node (ref "U7") (pin "5") (pinfunction "OE_5") (pintype "bidirectional"))
    )
    (net (code "138") (name "MOD7_ISO_POWER") (class "Default")
      (node (ref "LED1016") (pin "A") (pinfunction "ANODE_A") (pintype "bidirectional"))
      (node (ref "R82") (pin "2") (pinfunction "2_2") (pintype "passive"))
      (node (ref "S6") (pin "4") (pinfunction "EN_4") (pintype "bidirectional"))
      (node (ref "TP1016") (pin "TESTPOINT") (pinfunction "TESTPOINT_TESTPOINT") (pintype "bidirectional"))
      (node (ref "U31") (pin "9") (pinfunction "P0_9") (pintype "bidirectional"))
    )
    (net (code "139") (name "MOD7_ISO_USB") (class "Default")
      (node (ref "LED1018") (pin "A") (pinfunction "ANODE_A") (pintype "bidirectional"))
      (node (ref "R84") (pin "2") (pinfunction "2_2") (pintype "passive"))
      (node (ref "S12") (pin "6") (pinfunction "S_6") (pintype "bidirectional"))
      (node (ref "TP1018") (pin "TESTPOINT") (pinfunction "TESTPOINT_TESTPOINT") (pintype "bidirectional"))
      (node (ref "U31") (pin "11") (pinfunction "P2_11") (pintype "bidirectional"))
    )
    (net (code "140") (name "MOD7_OUT") (class "Default")
      (node (ref "J7") (pin "8") (pinfunction "MOD_OUT_8") (pintype "bidirectional"))
      (node (ref "U19") (pin "7") (pinfunction "B1_7") (pintype "bidirectional"))
    )
    (net (code "141") (name "MOD7_PPS") (class "Default")
      (node (ref "J7") (pin "7") (pinfunction "PPS_7") (pintype "bidirectional"))
      (node (ref "U13") (pin "6") (pinfunction "B2_6") (pintype "bidirectional"))
    )
    (net (code "142") (name "MOD7_SCL") (class "Default")
      (node (ref "J7") (pin "5") (pinfunction "SCL_5") (pintype "bidirectional"))
      (node (ref "R45") (pin "2") (pinfunction "2_2") (pintype "passive"))
      (node (ref "U7") (pin "6") (pinfunction "B1_6") (pintype "bidirectional"))
    )
    (net (code "143") (name "MOD7_SDA") (class "Default")
      (node (ref "J7") (pin "6") (pinfunction "SDA_6") (pintype "bidirectional"))
      (node (ref "R44") (pin "2") (pinfunction "2_2") (pintype "passive"))
      (node (ref "U7") (pin "7") (pinfunction "B0_7") (pintype "bidirectional"))
    )
    (net (code "144") (name "MOD7_USB+") (class "Default")
      (node (ref "J7") (pin "11") (pinfunction "USB_D+_11") (pintype "bidirectional"))
      (node (ref "U25") (pin "1") (pinfunction "D1+_1") (pintype "bidirectional"))
    )
    (net (code "145") (name "MOD7_USB-") (class "Default")
      (node (ref "J7") (pin "12") (pinfunction "USB_D-_12") (pintype "bidirectional"))
      (node (ref "U25") (pin "7") (pinfunction "D1-_7") (pintype "bidirectional"))
    )
    (net (code "146") (name "MOD7_USB_VBUS") (class "Default")
      (node (ref "C102") (pin "1") (pinfunction "1_1") (pintype "passive"))
      (node (ref "C63") (pin "1") (pinfunction "1_1") (pintype "bidirectional"))
      (node (ref "J7") (pin "13") (pinfunction "USB_VBUS_13") (pintype "bidirectional"))
      (node (ref "S18") (pin "6") (pinfunction "OUT_6") (pintype "bidirectional"))
      (node (ref "S18") (pin "7") (pinfunction "OUT_7") (pintype "bidirectional"))
    )
    (net (code "147") (name "MOD7_USB_~{EN}") (class "Default")
      (node (ref "S12") (pin "4") (pinfunction "Z_4") (pintype "bidirectional"))
      (node (ref "S18") (pin "4") (pinfunction "~{EN}_4") (pintype "bidirectional"))
      (node (ref "U25") (pin "8") (pinfunction "~{OE}_8") (pintype "bidirectional"))
    )
    (net (code "148") (name "MOD7_VCCIO") (class "Default")
      (node (ref "C44") (pin "1") (pinfunction "1_1") (pintype "bidirectional"))
      (node (ref "C50") (pin "1") (pinfunction "1_1") (pintype "bidirectional"))
      (node (ref "C87") (pin "1") (pinfunction "1_1") (pintype "bidirectional"))
      (node (ref "J7") (pin "4") (pinfunction "VCCIO_4") (pintype "bidirectional"))
      (node (ref "R44") (pin "1") (pinfunction "1_1") (pintype "passive"))
      (node (ref "R45") (pin "1") (pinfunction "1_1") (pintype "passive"))
      (node (ref "U13") (pin "8") (pinfunction "VCC_B_8") (pintype "bidirectional"))
      (node (ref "U19") (pin "8") (pinfunction "VCC_B_8") (pintype "bidirectional"))
      (node (ref "U7") (pin "8") (pinfunction "VCC_B_8") (pintype "bidirectional"))
    )
    (net (code "149") (name "MOD_SCL") (class "Default")
      (node (ref "J3") (pin "24") (pinfunction "MODULES_SCL_24") (pintype "bidirectional"))
      (node (ref "R50") (pin "1") (pinfunction "1_1") (pintype "passive"))
      (node (ref "TP6") (pin "TESTPOINT") (pinfunction "TESTPOINT_TESTPOINT") (pintype "bidirectional"))
      (node (ref "U2") (pin "3") (pinfunction "A1_3") (pintype "bidirectional"))
      (node (ref "U3") (pin "3") (pinfunction "A1_3") (pintype "bidirectional"))
      (node (ref "U4") (pin "3") (pinfunction "A1_3") (pintype "bidirectional"))
      (node (ref "U5") (pin "3") (pinfunction "A1_3") (pintype "bidirectional"))
      (node (ref "U6") (pin "3") (pinfunction "A1_3") (pintype "bidirectional"))
      (node (ref "U7") (pin "3") (pinfunction "A1_3") (pintype "bidirectional"))
    )
    (net (code "150") (name "MOD_SDA") (class "Default")
      (node (ref "J3") (pin "23") (pinfunction "MODULES_SDA_23") (pintype "bidirectional"))
      (node (ref "R49") (pin "1") (pinfunction "1_1") (pintype "passive"))
      (node (ref "TP5") (pin "TESTPOINT") (pinfunction "TESTPOINT_TESTPOINT") (pintype "bidirectional"))
      (node (ref "U2") (pin "2") (pinfunction "A0_2") (pintype "bidirectional"))
      (node (ref "U3") (pin "2") (pinfunction "A0_2") (pintype "bidirectional"))
      (node (ref "U4") (pin "2") (pinfunction "A0_2") (pintype "bidirectional"))
      (node (ref "U5") (pin "2") (pinfunction "A0_2") (pintype "bidirectional"))
      (node (ref "U6") (pin "2") (pinfunction "A0_2") (pintype "bidirectional"))
      (node (ref "U7") (pin "2") (pinfunction "A0_2") (pintype "bidirectional"))
    )
    (net (code "151") (name "Net-(C2-Pad2)") (class "Default")
      (node (ref "C2") (pin "2") (pinfunction "2_2") (pintype "bidirectional"))
      (node (ref "R26") (pin "1") (pinfunction "1_1") (pintype "passive"))
      (node (ref "Y1") (pin "1") (pinfunction "1_1") (pintype "bidirectional"))
    )
    (net (code "152") (name "Net-(LED1001-ANODE)") (class "Default")
      (node (ref "LED1001") (pin "A") (pinfunction "ANODE_A") (pintype "bidirectional"))
      (node (ref "R1001") (pin "1") (pinfunction "1_1") (pintype "passive"))
    )
    (net (code "153") (name "Net-(LED1002-ANODE)") (class "Default")
      (node (ref "LED1002") (pin "A") (pinfunction "ANODE_A") (pintype "bidirectional"))
      (node (ref "R1002") (pin "1") (pinfunction "1_1") (pintype "passive"))
    )
    (net (code "154") (name "Net-(LED1003-ANODE)") (class "Default")
      (node (ref "LED1003") (pin "A") (pinfunction "ANODE_A") (pintype "bidirectional"))
      (node (ref "R1003") (pin "1") (pinfunction "1_1") (pintype "passive"))
    )
    (net (code "155") (name "Net-(LED1004-CATHODE)") (class "Default")
      (node (ref "LED1004") (pin "C") (pinfunction "CATHODE_C") (pintype "bidirectional"))
      (node (ref "R1004") (pin "2") (pinfunction "2_2") (pintype "passive"))
    )
    (net (code "156") (name "Net-(LED1005-CATHODE)") (class "Default")
      (node (ref "LED1005") (pin "C") (pinfunction "CATHODE_C") (pintype "bidirectional"))
      (node (ref "R1005") (pin "2") (pinfunction "2_2") (pintype "passive"))
    )
    (net (code "157") (name "Net-(LED1006-CATHODE)") (class "Default")
      (node (ref "LED1006") (pin "C") (pinfunction "CATHODE_C") (pintype "bidirectional"))
      (node (ref "R1006") (pin "2") (pinfunction "2_2") (pintype "passive"))
    )
    (net (code "158") (name "Net-(LED1007-ANODE)") (class "Default")
      (node (ref "LED1007") (pin "A") (pinfunction "ANODE_A") (pintype "bidirectional"))
      (node (ref "R1007") (pin "1") (pinfunction "1_1") (pintype "passive"))
    )
    (net (code "159") (name "Net-(LED1008-ANODE)") (class "Default")
      (node (ref "LED1008") (pin "A") (pinfunction "ANODE_A") (pintype "bidirectional"))
      (node (ref "R1008") (pin "1") (pinfunction "1_1") (pintype "passive"))
    )
    (net (code "160") (name "Net-(LED1009-ANODE)") (class "Default")
      (node (ref "LED1009") (pin "A") (pinfunction "ANODE_A") (pintype "bidirectional"))
      (node (ref "R1009") (pin "1") (pinfunction "1_1") (pintype "passive"))
    )
    (net (code "161") (name "Net-(LED1010-CATHODE)") (class "Default")
      (node (ref "LED1010") (pin "C") (pinfunction "CATHODE_C") (pintype "bidirectional"))
      (node (ref "R1010") (pin "2") (pinfunction "2_2") (pintype "passive"))
    )
    (net (code "162") (name "Net-(LED1011-CATHODE)") (class "Default")
      (node (ref "LED1011") (pin "C") (pinfunction "CATHODE_C") (pintype "bidirectional"))
      (node (ref "R1011") (pin "2") (pinfunction "2_2") (pintype "passive"))
    )
    (net (code "163") (name "Net-(LED1012-CATHODE)") (class "Default")
      (node (ref "LED1012") (pin "C") (pinfunction "CATHODE_C") (pintype "bidirectional"))
      (node (ref "R1012") (pin "2") (pinfunction "2_2") (pintype "passive"))
    )
    (net (code "164") (name "Net-(LED1013-ANODE)") (class "Default")
      (node (ref "LED1013") (pin "A") (pinfunction "ANODE_A") (pintype "bidirectional"))
      (node (ref "R1013") (pin "1") (pinfunction "1_1") (pintype "passive"))
    )
    (net (code "165") (name "Net-(LED1014-ANODE)") (class "Default")
      (node (ref "LED1014") (pin "A") (pinfunction "ANODE_A") (pintype "bidirectional"))
      (node (ref "R1014") (pin "1") (pinfunction "1_1") (pintype "passive"))
    )
    (net (code "166") (name "Net-(LED1015-ANODE)") (class "Default")
      (node (ref "LED1015") (pin "A") (pinfunction "ANODE_A") (pintype "bidirectional"))
      (node (ref "R1015") (pin "1") (pinfunction "1_1") (pintype "passive"))
    )
    (net (code "167") (name "Net-(LED1016-CATHODE)") (class "Default")
      (node (ref "LED1016") (pin "C") (pinfunction "CATHODE_C") (pintype "bidirectional"))
      (node (ref "R1016") (pin "2") (pinfunction "2_2") (pintype "passive"))
    )
    (net (code "168") (name "Net-(LED1017-CATHODE)") (class "Default")
      (node (ref "LED1017") (pin "C") (pinfunction "CATHODE_C") (pintype "bidirectional"))
      (node (ref "R1017") (pin "2") (pinfunction "2_2") (pintype "passive"))
    )
    (net (code "169") (name "Net-(LED1018-CATHODE)") (class "Default")
      (node (ref "LED1018") (pin "C") (pinfunction "CATHODE_C") (pintype "bidirectional"))
      (node (ref "R1018") (pin "2") (pinfunction "2_2") (pintype "passive"))
    )
    (net (code "170") (name "Net-(U1-DP0PUR)") (class "Default")
      (node (ref "R25") (pin "2") (pinfunction "2_2") (pintype "passive"))
      (node (ref "U1") (pin "2") (pinfunction "DP0PUR_2") (pintype "bidirectional"))
    )
    (net (code "171") (name "Net-(U1-XTAL1)") (class "Default")
      (node (ref "C1") (pin "2") (pinfunction "2_2") (pintype "bidirectional"))
      (node (ref "U1") (pin "45") (pinfunction "XTAL1_45") (pintype "bidirectional"))
      (node (ref "Y1") (pin "3") (pinfunction "2_3") (pintype "bidirectional"))
    )
    (net (code "172") (name "Net-(U1-XTAL2)") (class "Default")
      (node (ref "R26") (pin "2") (pinfunction "2_2") (pintype "passive"))
      (node (ref "U1") (pin "44") (pinfunction "XTAL2_44") (pintype "bidirectional"))
    )
    (net (code "173") (name "Net-(U20-D2+)") (class "Default")
      (node (ref "R13") (pin "1") (pinfunction "1_1") (pintype "passive"))
      (node (ref "U20") (pin "2") (pinfunction "D2+_2") (pintype "bidirectional"))
    )
    (net (code "174") (name "Net-(U20-D2-)") (class "Default")
      (node (ref "R14") (pin "1") (pinfunction "1_1") (pintype "passive"))
      (node (ref "U20") (pin "6") (pinfunction "D2-_6") (pintype "bidirectional"))
    )
    (net (code "175") (name "Net-(U21-D2+)") (class "Default")
      (node (ref "R15") (pin "1") (pinfunction "1_1") (pintype "passive"))
      (node (ref "U21") (pin "2") (pinfunction "D2+_2") (pintype "bidirectional"))
    )
    (net (code "176") (name "Net-(U21-D2-)") (class "Default")
      (node (ref "R16") (pin "1") (pinfunction "1_1") (pintype "passive"))
      (node (ref "U21") (pin "6") (pinfunction "D2-_6") (pintype "bidirectional"))
    )
    (net (code "177") (name "Net-(U22-D2+)") (class "Default")
      (node (ref "R17") (pin "1") (pinfunction "1_1") (pintype "passive"))
      (node (ref "U22") (pin "2") (pinfunction "D2+_2") (pintype "bidirectional"))
    )
    (net (code "178") (name "Net-(U22-D2-)") (class "Default")
      (node (ref "R18") (pin "1") (pinfunction "1_1") (pintype "passive"))
      (node (ref "U22") (pin "6") (pinfunction "D2-_6") (pintype "bidirectional"))
    )
    (net (code "179") (name "Net-(U23-D2+)") (class "Default")
      (node (ref "R19") (pin "1") (pinfunction "1_1") (pintype "passive"))
      (node (ref "U23") (pin "2") (pinfunction "D2+_2") (pintype "bidirectional"))
    )
    (net (code "180") (name "Net-(U23-D2-)") (class "Default")
      (node (ref "R20") (pin "1") (pinfunction "1_1") (pintype "passive"))
      (node (ref "U23") (pin "6") (pinfunction "D2-_6") (pintype "bidirectional"))
    )
    (net (code "181") (name "Net-(U24-D2+)") (class "Default")
      (node (ref "R21") (pin "1") (pinfunction "1_1") (pintype "passive"))
      (node (ref "U24") (pin "2") (pinfunction "D2+_2") (pintype "bidirectional"))
    )
    (net (code "182") (name "Net-(U24-D2-)") (class "Default")
      (node (ref "R22") (pin "1") (pinfunction "1_1") (pintype "passive"))
      (node (ref "U24") (pin "6") (pinfunction "D2-_6") (pintype "bidirectional"))
    )
    (net (code "183") (name "Net-(U25-D2+)") (class "Default")
      (node (ref "R23") (pin "1") (pinfunction "1_1") (pintype "passive"))
      (node (ref "U25") (pin "2") (pinfunction "D2+_2") (pintype "bidirectional"))
    )
    (net (code "184") (name "Net-(U25-D2-)") (class "Default")
      (node (ref "R24") (pin "1") (pinfunction "1_1") (pintype "passive"))
      (node (ref "U25") (pin "6") (pinfunction "D2-_6") (pintype "bidirectional"))
    )
    (net (code "185") (name "Net-(U34-~{WC})") (class "Default")
      (node (ref "SJ1") (pin "2") (pinfunction "2_2") (pintype "passive"))
      (node (ref "U34") (pin "7") (pinfunction "~{WC}_7") (pintype "bidirectional"))
    )
    (net (code "186") (name "PPS") (class "Default")
      (node (ref "J3") (pin "25") (pinfunction "PPS_25") (pintype "bidirectional"))
      (node (ref "TP10") (pin "TESTPOINT") (pinfunction "TESTPOINT_TESTPOINT") (pintype "bidirectional"))
      (node (ref "U10") (pin "3") (pinfunction "A2_3") (pintype "bidirectional"))
      (node (ref "U11") (pin "3") (pinfunction "A2_3") (pintype "bidirectional"))
      (node (ref "U12") (pin "3") (pinfunction "A2_3") (pintype "bidirectional"))
      (node (ref "U13") (pin "3") (pinfunction "A2_3") (pintype "bidirectional"))
      (node (ref "U8") (pin "3") (pinfunction "A2_3") (pintype "bidirectional"))
      (node (ref "U9") (pin "3") (pinfunction "A2_3") (pintype "bidirectional"))
    )
    (net (code "187") (name "SMBCLK") (class "Default")
      (node (ref "J3") (pin "5") (pinfunction "SMBCLK_5") (pintype "bidirectional"))
      (node (ref "J4") (pin "5") (pinfunction "SMBCLK_5") (pintype "open_collector"))
      (node (ref "R47") (pin "1") (pinfunction "1_1") (pintype "passive"))
      (node (ref "TP2") (pin "TESTPOINT") (pinfunction "TESTPOINT_TESTPOINT") (pintype "bidirectional"))
      (node (ref "U26") (pin "19") (pinfunction "SCL_19") (pintype "bidirectional"))
      (node (ref "U27") (pin "19") (pinfunction "SCL_19") (pintype "bidirectional"))
      (node (ref "U28") (pin "19") (pinfunction "SCL_19") (pintype "bidirectional"))
      (node (ref "U29") (pin "19") (pinfunction "SCL_19") (pintype "bidirectional"))
      (node (ref "U30") (pin "19") (pinfunction "SCL_19") (pintype "bidirectional"))
      (node (ref "U31") (pin "19") (pinfunction "SCL_19") (pintype "bidirectional"))
      (node (ref "U32") (pin "19") (pinfunction "SCL_19") (pintype "bidirectional"))
      (node (ref "U34") (pin "6") (pinfunction "SCL_6") (pintype "bidirectional"))
    )
    (net (code "188") (name "SMBDATA") (class "Default")
      (node (ref "J3") (pin "3") (pinfunction "SMBDATA_3") (pintype "bidirectional"))
      (node (ref "J4") (pin "3") (pinfunction "SMBDATA_3") (pintype "open_collector"))
      (node (ref "R46") (pin "1") (pinfunction "1_1") (pintype "passive"))
      (node (ref "TP1") (pin "TESTPOINT") (pinfunction "TESTPOINT_TESTPOINT") (pintype "bidirectional"))
      (node (ref "U26") (pin "20") (pinfunction "SDA_20") (pintype "bidirectional"))
      (node (ref "U27") (pin "20") (pinfunction "SDA_20") (pintype "bidirectional"))
      (node (ref "U28") (pin "20") (pinfunction "SDA_20") (pintype "bidirectional"))
      (node (ref "U29") (pin "20") (pinfunction "SDA_20") (pintype "bidirectional"))
      (node (ref "U30") (pin "20") (pinfunction "SDA_20") (pintype "bidirectional"))
      (node (ref "U31") (pin "20") (pinfunction "SDA_20") (pintype "bidirectional"))
      (node (ref "U32") (pin "20") (pinfunction "SDA_20") (pintype "bidirectional"))
      (node (ref "U34") (pin "5") (pinfunction "SDA_5") (pintype "bidirectional"))
    )
    (net (code "189") (name "USB_SUSPEND_STATUS") (class "Default")
      (node (ref "TP31") (pin "TESTPOINT") (pinfunction "TESTPOINT_TESTPOINT") (pintype "bidirectional"))
      (node (ref "U1") (pin "1") (pinfunction "SUSPND_1") (pintype "bidirectional"))
    )
    (net (code "190") (name "VBATT+") (class "Default")
      (node (ref "J4") (pin "17") (pinfunction "VBATT+_17") (pintype "power_in"))
      (node (ref "J9") (pin "1") (pinfunction "1_1") (pintype "bidirectional"))
      (node (ref "TP14") (pin "TESTPOINT") (pinfunction "TESTPOINT_TESTPOINT") (pintype "bidirectional"))
    )
    (net (code "191") (name "VBATT-") (class "Default")
      (node (ref "J4") (pin "18") (pinfunction "VBATT-_18") (pintype "power_in"))
      (node (ref "J9") (pin "2") (pinfunction "2_2") (pintype "bidirectional"))
      (node (ref "TP15") (pin "TESTPOINT") (pinfunction "TESTPOINT_TESTPOINT") (pintype "bidirectional"))
    )
    (net (code "192") (name "VCC_BACKPLANE") (class "Default")
      (node (ref "C15") (pin "1") (pinfunction "1_1") (pintype "bidirectional"))
      (node (ref "C16") (pin "1") (pinfunction "1_1") (pintype "bidirectional"))
      (node (ref "C17") (pin "1") (pinfunction "1_1") (pintype "bidirectional"))
      (node (ref "C18") (pin "1") (pinfunction "1_1") (pintype "bidirectional"))
      (node (ref "C19") (pin "1") (pinfunction "1_1") (pintype "bidirectional"))
      (node (ref "C20") (pin "1") (pinfunction "1_1") (pintype "bidirectional"))
      (node (ref "C27") (pin "1") (pinfunction "1_1") (pintype "bidirectional"))
      (node (ref "C28") (pin "1") (pinfunction "1_1") (pintype "bidirectional"))
      (node (ref "C29") (pin "1") (pinfunction "1_1") (pintype "bidirectional"))
      (node (ref "C30") (pin "1") (pinfunction "1_1") (pintype "bidirectional"))
      (node (ref "C31") (pin "1") (pinfunction "1_1") (pintype "bidirectional"))
      (node (ref "C32") (pin "1") (pinfunction "1_1") (pintype "bidirectional"))
      (node (ref "C33") (pin "1") (pinfunction "1_1") (pintype "bidirectional"))
      (node (ref "C34") (pin "1") (pinfunction "1_1") (pintype "bidirectional"))
      (node (ref "C35") (pin "1") (pinfunction "1_1") (pintype "bidirectional"))
      (node (ref "C36") (pin "1") (pinfunction "1_1") (pintype "bidirectional"))
      (node (ref "C37") (pin "1") (pinfunction "1_1") (pintype "bidirectional"))
      (node (ref "C38") (pin "1") (pinfunction "1_1") (pintype "bidirectional"))
      (node (ref "C51") (pin "2") (pinfunction "2_2") (pintype "bidirectional"))
      (node (ref "C52") (pin "1") (pinfunction "1_1") (pintype "bidirectional"))
      (node (ref "C53") (pin "1") (pinfunction "1_1") (pintype "bidirectional"))
      (node (ref "C54") (pin "1") (pinfunction "1_1") (pintype "bidirectional"))
      (node (ref "C55") (pin "1") (pinfunction "1_1") (pintype "bidirectional"))
      (node (ref "C56") (pin "1") (pinfunction "1_1") (pintype "bidirectional"))
      (node (ref "C57") (pin "1") (pinfunction "1_1") (pintype "bidirectional"))
      (node (ref "C64") (pin "1") (pinfunction "1_1") (pintype "bidirectional"))
      (node (ref "C65") (pin "1") (pinfunction "1_1") (pintype "bidirectional"))
      (node (ref "C66") (pin "1") (pinfunction "1_1") (pintype "bidirectional"))
      (node (ref "C67") (pin "1") (pinfunction "1_1") (pintype "bidirectional"))
      (node (ref "C68") (pin "1") (pinfunction "1_1") (pintype "bidirectional"))
      (node (ref "C69") (pin "1") (pinfunction "1_1") (pintype "bidirectional"))
      (node (ref "C76") (pin "2") (pinfunction "2_2") (pintype "bidirectional"))
      (node (ref "C77") (pin "2") (pinfunction "2_2") (pintype "bidirectional"))
      (node (ref "C78") (pin "2") (pinfunction "2_2") (pintype "bidirectional"))
      (node (ref "C79") (pin "2") (pinfunction "2_2") (pintype "bidirectional"))
      (node (ref "C80") (pin "2") (pinfunction "2_2") (pintype "bidirectional"))
      (node (ref "C81") (pin "2") (pinfunction "2_2") (pintype "bidirectional"))
      (node (ref "C88") (pin "1") (pinfunction "1_1") (pintype "bidirectional"))
      (node (ref "C89") (pin "1") (pinfunction "1_1") (pintype "bidirectional"))
      (node (ref "C96") (pin "2") (pinfunction "2_2") (pintype "bidirectional"))
      (node (ref "J4") (pin "13") (pinfunction "VCC_BACKPLANE_13") (pintype "power_in"))
      (node (ref "R27") (pin "1") (pinfunction "1_1") (pintype "passive"))
      (node (ref "R28") (pin "2") (pinfunction "2_2") (pintype "passive"))
      (node (ref "R29") (pin "2") (pinfunction "2_2") (pintype "passive"))
      (node (ref "R30") (pin "2") (pinfunction "2_2") (pintype "passive"))
      (node (ref "R31") (pin "2") (pinfunction "2_2") (pintype "passive"))
      (node (ref "R32") (pin "2") (pinfunction "2_2") (pintype "passive"))
      (node (ref "R33") (pin "2") (pinfunction "2_2") (pintype "passive"))
      (node (ref "R46") (pin "2") (pinfunction "2_2") (pintype "passive"))
      (node (ref "R47") (pin "2") (pinfunction "2_2") (pintype "passive"))
      (node (ref "R48") (pin "2") (pinfunction "2_2") (pintype "passive"))
      (node (ref "R49") (pin "2") (pinfunction "2_2") (pintype "passive"))
      (node (ref "R50") (pin "2") (pinfunction "2_2") (pintype "passive"))
      (node (ref "R51") (pin "2") (pinfunction "2_2") (pintype "passive"))
      (node (ref "R52") (pin "2") (pinfunction "2_2") (pintype "passive"))
      (node (ref "S10") (pin "3") (pinfunction "I0_3") (pintype "bidirectional"))
      (node (ref "S10") (pin "5") (pinfunction "VCC_5") (pintype "bidirectional"))
      (node (ref "S11") (pin "3") (pinfunction "I0_3") (pintype "bidirectional"))
      (node (ref "S11") (pin "5") (pinfunction "VCC_5") (pintype "bidirectional"))
      (node (ref "S12") (pin "3") (pinfunction "I0_3") (pintype "bidirectional"))
      (node (ref "S12") (pin "5") (pinfunction "VCC_5") (pintype "bidirectional"))
      (node (ref "S7") (pin "3") (pinfunction "I0_3") (pintype "bidirectional"))
      (node (ref "S7") (pin "5") (pinfunction "VCC_5") (pintype "bidirectional"))
      (node (ref "S8") (pin "3") (pinfunction "I0_3") (pintype "bidirectional"))
      (node (ref "S8") (pin "5") (pinfunction "VCC_5") (pintype "bidirectional"))
      (node (ref "S9") (pin "3") (pinfunction "I0_3") (pintype "bidirectional"))
      (node (ref "S9") (pin "5") (pinfunction "VCC_5") (pintype "bidirectional"))
      (node (ref "SJ1") (pin "1") (pinfunction "1_1") (pintype "passive"))
      (node (ref "TP24") (pin "TESTPOINT") (pinfunction "TESTPOINT_TESTPOINT") (pintype "bidirectional"))
      (node (ref "TP8") (pin "TESTPOINT") (pinfunction "TESTPOINT_TESTPOINT") (pintype "bidirectional"))
      (node (ref "U1") (pin "10") (pinfunction "~{BUSPWR}_10") (pintype "bidirectional"))
      (node (ref "U1") (pin "46") (pinfunction "VCC_46") (pintype "bidirectional"))
      (node (ref "U1") (pin "47") (pinfunction "~{EXTMEM}_47") (pintype "bidirectional"))
      (node (ref "U1") (pin "8") (pinfunction "EEDATA/~{GANGED}_8") (pintype "bidirectional"))
      (node (ref "U1") (pin "9") (pinfunction "VCC_9") (pintype "bidirectional"))
      (node (ref "U10") (pin "1") (pinfunction "VCC_A_1") (pintype "bidirectional"))
      (node (ref "U10") (pin "5") (pinfunction "DIR_5") (pintype "bidirectional"))
      (node (ref "U11") (pin "1") (pinfunction "VCC_A_1") (pintype "bidirectional"))
      (node (ref "U11") (pin "5") (pinfunction "DIR_5") (pintype "bidirectional"))
      (node (ref "U12") (pin "1") (pinfunction "VCC_A_1") (pintype "bidirectional"))
      (node (ref "U12") (pin "5") (pinfunction "DIR_5") (pintype "bidirectional"))
      (node (ref "U13") (pin "1") (pinfunction "VCC_A_1") (pintype "bidirectional"))
      (node (ref "U13") (pin "5") (pinfunction "DIR_5") (pintype "bidirectional"))
      (node (ref "U14") (pin "1") (pinfunction "VCC_A_1") (pintype "bidirectional"))
      (node (ref "U15") (pin "1") (pinfunction "VCC_A_1") (pintype "bidirectional"))
      (node (ref "U16") (pin "1") (pinfunction "VCC_A_1") (pintype "bidirectional"))
      (node (ref "U17") (pin "1") (pinfunction "VCC_A_1") (pintype "bidirectional"))
      (node (ref "U18") (pin "1") (pinfunction "VCC_A_1") (pintype "bidirectional"))
      (node (ref "U19") (pin "1") (pinfunction "VCC_A_1") (pintype "bidirectional"))
      (node (ref "U2") (pin "1") (pinfunction "VCC_A_1") (pintype "bidirectional"))
      (node (ref "U20") (pin "9") (pinfunction "VCC_9") (pintype "bidirectional"))
      (node (ref "U21") (pin "9") (pinfunction "VCC_9") (pintype "bidirectional"))
      (node (ref "U22") (pin "9") (pinfunction "VCC_9") (pintype "bidirectional"))
      (node (ref "U23") (pin "9") (pinfunction "VCC_9") (pintype "bidirectional"))
      (node (ref "U24") (pin "9") (pinfunction "VCC_9") (pintype "bidirectional"))
      (node (ref "U25") (pin "9") (pinfunction "VCC_9") (pintype "bidirectional"))
      (node (ref "U26") (pin "18") (pinfunction "VCC_18") (pintype "bidirectional"))
      (node (ref "U27") (pin "18") (pinfunction "VCC_18") (pintype "bidirectional"))
      (node (ref "U27") (pin "3") (pinfunction "A0_3") (pintype "bidirectional"))
      (node (ref "U28") (pin "18") (pinfunction "VCC_18") (pintype "bidirectional"))
      (node (ref "U28") (pin "2") (pinfunction "A1_2") (pintype "bidirectional"))
      (node (ref "U29") (pin "1") (pinfunction "A2_1") (pintype "bidirectional"))
      (node (ref "U29") (pin "18") (pinfunction "VCC_18") (pintype "bidirectional"))
      (node (ref "U29") (pin "3") (pinfunction "A0_3") (pintype "bidirectional"))
      (node (ref "U3") (pin "1") (pinfunction "VCC_A_1") (pintype "bidirectional"))
      (node (ref "U30") (pin "1") (pinfunction "A2_1") (pintype "bidirectional"))
      (node (ref "U30") (pin "18") (pinfunction "VCC_18") (pintype "bidirectional"))
      (node (ref "U30") (pin "2") (pinfunction "A1_2") (pintype "bidirectional"))
      (node (ref "U31") (pin "1") (pinfunction "A2_1") (pintype "bidirectional"))
      (node (ref "U31") (pin "18") (pinfunction "VCC_18") (pintype "bidirectional"))
      (node (ref "U31") (pin "2") (pinfunction "A1_2") (pintype "bidirectional"))
      (node (ref "U31") (pin "3") (pinfunction "A0_3") (pintype "bidirectional"))
      (node (ref "U32") (pin "18") (pinfunction "VCC_18") (pintype "bidirectional"))
      (node (ref "U32") (pin "2") (pinfunction "A1_2") (pintype "bidirectional"))
      (node (ref "U32") (pin "3") (pinfunction "A0_3") (pintype "bidirectional"))
      (node (ref "U33") (pin "2") (pinfunction "VCC_2") (pintype "bidirectional"))
      (node (ref "U34") (pin "1") (pinfunction "E0_1") (pintype "bidirectional"))
      (node (ref "U34") (pin "8") (pinfunction "VCC_8") (pintype "bidirectional"))
      (node (ref "U4") (pin "1") (pinfunction "VCC_A_1") (pintype "bidirectional"))
      (node (ref "U5") (pin "1") (pinfunction "VCC_A_1") (pintype "bidirectional"))
      (node (ref "U6") (pin "1") (pinfunction "VCC_A_1") (pintype "bidirectional"))
      (node (ref "U7") (pin "1") (pinfunction "VCC_A_1") (pintype "bidirectional"))
      (node (ref "U8") (pin "1") (pinfunction "VCC_A_1") (pintype "bidirectional"))
      (node (ref "U8") (pin "5") (pinfunction "DIR_5") (pintype "bidirectional"))
      (node (ref "U9") (pin "1") (pinfunction "VCC_A_1") (pintype "bidirectional"))
      (node (ref "U9") (pin "5") (pinfunction "DIR_5") (pintype "bidirectional"))
    )
    (net (code "193") (name "VCC_CONTROLLER") (class "Default")
      (node (ref "J3") (pin "2") (pinfunction "VCC_CONTROLLER_2") (pintype "bidirectional"))
      (node (ref "J4") (pin "2") (pinfunction "VCC_CONTROLLER_2") (pintype "power_in"))
      (node (ref "TP22") (pin "TESTPOINT") (pinfunction "TESTPOINT_TESTPOINT") (pintype "bidirectional"))
    )
    (net (code "194") (name "VCC_LINUX") (class "Default")
      (node (ref "J3") (pin "4") (pinfunction "VCC_LINUX_4") (pintype "bidirectional"))
      (node (ref "J4") (pin "4") (pinfunction "VCC_LINUX_4") (pintype "power_in"))
      (node (ref "TP23") (pin "TESTPOINT") (pinfunction "TESTPOINT_TESTPOINT") (pintype "bidirectional"))
    )
    (net (code "195") (name "VSOL+") (class "Default")
      (node (ref "J4") (pin "19") (pinfunction "VSOL+_19") (pintype "power_in"))
      (node (ref "J8") (pin "1") (pinfunction "1_1") (pintype "bidirectional"))
      (node (ref "TP12") (pin "TESTPOINT") (pinfunction "TESTPOINT_TESTPOINT") (pintype "bidirectional"))
    )
    (net (code "196") (name "VSOL-") (class "Default")
      (node (ref "J4") (pin "20") (pinfunction "VSOL-_20") (pintype "power_in"))
      (node (ref "J8") (pin "2") (pinfunction "2_2") (pintype "bidirectional"))
      (node (ref "TP13") (pin "TESTPOINT") (pinfunction "TESTPOINT_TESTPOINT") (pintype "bidirectional"))
    )
    (net (code "197") (name "unconnected-(D2-C-Pad2)") (class "Default")
      (node (ref "D2") (pin "2") (pinfunction "C_2") (pintype "bidirectional"))
    )
    (net (code "198") (name "unconnected-(D2-D-Pad4)") (class "Default")
      (node (ref "D2") (pin "4") (pinfunction "D_4") (pintype "bidirectional"))
    )
    (net (code "199") (name "unconnected-(D3-A-Pad8)") (class "Default")
      (node (ref "D3") (pin "8") (pinfunction "A_8") (pintype "bidirectional"))
    )
    (net (code "200") (name "unconnected-(D3-B-Pad6)") (class "Default")
      (node (ref "D3") (pin "6") (pinfunction "B_6") (pintype "bidirectional"))
    )
    (net (code "201") (name "unconnected-(U1-EECLK-Pad7)") (class "Default")
      (node (ref "U1") (pin "7") (pinfunction "EECLK_7") (pintype "bidirectional"))
    )
    (net (code "202") (name "unconnected-(U14-A2-Pad3)") (class "Default")
      (node (ref "U14") (pin "3") (pinfunction "A2_3") (pintype "bidirectional"))
    )
    (net (code "203") (name "unconnected-(U14-B2-Pad6)") (class "Default")
      (node (ref "U14") (pin "6") (pinfunction "B2_6") (pintype "bidirectional"))
    )
    (net (code "204") (name "unconnected-(U15-A2-Pad3)") (class "Default")
      (node (ref "U15") (pin "3") (pinfunction "A2_3") (pintype "bidirectional"))
    )
    (net (code "205") (name "unconnected-(U15-B2-Pad6)") (class "Default")
      (node (ref "U15") (pin "6") (pinfunction "B2_6") (pintype "bidirectional"))
    )
    (net (code "206") (name "unconnected-(U16-A2-Pad3)") (class "Default")
      (node (ref "U16") (pin "3") (pinfunction "A2_3") (pintype "bidirectional"))
    )
    (net (code "207") (name "unconnected-(U16-B2-Pad6)") (class "Default")
      (node (ref "U16") (pin "6") (pinfunction "B2_6") (pintype "bidirectional"))
    )
    (net (code "208") (name "unconnected-(U17-A2-Pad3)") (class "Default")
      (node (ref "U17") (pin "3") (pinfunction "A2_3") (pintype "bidirectional"))
    )
    (net (code "209") (name "unconnected-(U17-B2-Pad6)") (class "Default")
      (node (ref "U17") (pin "6") (pinfunction "B2_6") (pintype "bidirectional"))
    )
    (net (code "210") (name "unconnected-(U18-A2-Pad3)") (class "Default")
      (node (ref "U18") (pin "3") (pinfunction "A2_3") (pintype "bidirectional"))
    )
    (net (code "211") (name "unconnected-(U18-B2-Pad6)") (class "Default")
      (node (ref "U18") (pin "6") (pinfunction "B2_6") (pintype "bidirectional"))
    )
    (net (code "212") (name "unconnected-(U18-DIR-Pad5)") (class "Default")
      (node (ref "U18") (pin "5") (pinfunction "DIR_5") (pintype "bidirectional"))
    )
    (net (code "213") (name "unconnected-(U19-A2-Pad3)") (class "Default")
      (node (ref "U19") (pin "3") (pinfunction "A2_3") (pintype "bidirectional"))
    )
    (net (code "214") (name "unconnected-(U19-B2-Pad6)") (class "Default")
      (node (ref "U19") (pin "6") (pinfunction "B2_6") (pintype "bidirectional"))
    )
    (net (code "215") (name "unconnected-(U26-INT-Pad7)") (class "Default")
      (node (ref "U26") (pin "7") (pinfunction "INT_7") (pintype "bidirectional"))
    )
    (net (code "216") (name "unconnected-(U26-P3-Pad12)") (class "Default")
      (node (ref "U26") (pin "12") (pinfunction "P3_12") (pintype "bidirectional"))
    )
    (net (code "217") (name "unconnected-(U26-P4-Pad13)") (class "Default")
      (node (ref "U26") (pin "13") (pinfunction "P4_13") (pintype "bidirectional"))
    )
    (net (code "218") (name "unconnected-(U26-P5-Pad14)") (class "Default")
      (node (ref "U26") (pin "14") (pinfunction "P5_14") (pintype "bidirectional"))
    )
    (net (code "219") (name "unconnected-(U26-P6-Pad15)") (class "Default")
      (node (ref "U26") (pin "15") (pinfunction "P6_15") (pintype "bidirectional"))
    )
    (net (code "220") (name "unconnected-(U26-P7-Pad16)") (class "Default")
      (node (ref "U26") (pin "16") (pinfunction "P7_16") (pintype "bidirectional"))
    )
    (net (code "221") (name "unconnected-(U27-INT-Pad7)") (class "Default")
      (node (ref "U27") (pin "7") (pinfunction "INT_7") (pintype "bidirectional"))
    )
    (net (code "222") (name "unconnected-(U27-P3-Pad12)") (class "Default")
      (node (ref "U27") (pin "12") (pinfunction "P3_12") (pintype "bidirectional"))
    )
    (net (code "223") (name "unconnected-(U27-P4-Pad13)") (class "Default")
      (node (ref "U27") (pin "13") (pinfunction "P4_13") (pintype "bidirectional"))
    )
    (net (code "224") (name "unconnected-(U27-P5-Pad14)") (class "Default")
      (node (ref "U27") (pin "14") (pinfunction "P5_14") (pintype "bidirectional"))
    )
    (net (code "225") (name "unconnected-(U27-P6-Pad15)") (class "Default")
      (node (ref "U27") (pin "15") (pinfunction "P6_15") (pintype "bidirectional"))
    )
    (net (code "226") (name "unconnected-(U27-P7-Pad16)") (class "Default")
      (node (ref "U27") (pin "16") (pinfunction "P7_16") (pintype "bidirectional"))
    )
    (net (code "227") (name "unconnected-(U28-INT-Pad7)") (class "Default")
      (node (ref "U28") (pin "7") (pinfunction "INT_7") (pintype "bidirectional"))
    )
    (net (code "228") (name "unconnected-(U28-P3-Pad12)") (class "Default")
      (node (ref "U28") (pin "12") (pinfunction "P3_12") (pintype "bidirectional"))
    )
    (net (code "229") (name "unconnected-(U28-P4-Pad13)") (class "Default")
      (node (ref "U28") (pin "13") (pinfunction "P4_13") (pintype "bidirectional"))
    )
    (net (code "230") (name "unconnected-(U28-P5-Pad14)") (class "Default")
      (node (ref "U28") (pin "14") (pinfunction "P5_14") (pintype "bidirectional"))
    )
    (net (code "231") (name "unconnected-(U28-P6-Pad15)") (class "Default")
      (node (ref "U28") (pin "15") (pinfunction "P6_15") (pintype "bidirectional"))
    )
    (net (code "232") (name "unconnected-(U28-P7-Pad16)") (class "Default")
      (node (ref "U28") (pin "16") (pinfunction "P7_16") (pintype "bidirectional"))
    )
    (net (code "233") (name "unconnected-(U29-INT-Pad7)") (class "Default")
      (node (ref "U29") (pin "7") (pinfunction "INT_7") (pintype "bidirectional"))
    )
    (net (code "234") (name "unconnected-(U29-P3-Pad12)") (class "Default")
      (node (ref "U29") (pin "12") (pinfunction "P3_12") (pintype "bidirectional"))
    )
    (net (code "235") (name "unconnected-(U29-P4-Pad13)") (class "Default")
      (node (ref "U29") (pin "13") (pinfunction "P4_13") (pintype "bidirectional"))
    )
    (net (code "236") (name "unconnected-(U29-P5-Pad14)") (class "Default")
      (node (ref "U29") (pin "14") (pinfunction "P5_14") (pintype "bidirectional"))
    )
    (net (code "237") (name "unconnected-(U29-P6-Pad15)") (class "Default")
      (node (ref "U29") (pin "15") (pinfunction "P6_15") (pintype "bidirectional"))
    )
    (net (code "238") (name "unconnected-(U29-P7-Pad16)") (class "Default")
      (node (ref "U29") (pin "16") (pinfunction "P7_16") (pintype "bidirectional"))
    )
    (net (code "239") (name "unconnected-(U30-INT-Pad7)") (class "Default")
      (node (ref "U30") (pin "7") (pinfunction "INT_7") (pintype "bidirectional"))
    )
    (net (code "240") (name "unconnected-(U30-P3-Pad12)") (class "Default")
      (node (ref "U30") (pin "12") (pinfunction "P3_12") (pintype "bidirectional"))
    )
    (net (code "241") (name "unconnected-(U30-P4-Pad13)") (class "Default")
      (node (ref "U30") (pin "13") (pinfunction "P4_13") (pintype "bidirectional"))
    )
    (net (code "242") (name "unconnected-(U30-P5-Pad14)") (class "Default")
      (node (ref "U30") (pin "14") (pinfunction "P5_14") (pintype "bidirectional"))
    )
    (net (code "243") (name "unconnected-(U30-P6-Pad15)") (class "Default")
      (node (ref "U30") (pin "15") (pinfunction "P6_15") (pintype "bidirectional"))
    )
    (net (code "244") (name "unconnected-(U30-P7-Pad16)") (class "Default")
      (node (ref "U30") (pin "16") (pinfunction "P7_16") (pintype "bidirectional"))
    )
    (net (code "245") (name "unconnected-(U31-INT-Pad7)") (class "Default")
      (node (ref "U31") (pin "7") (pinfunction "INT_7") (pintype "bidirectional"))
    )
    (net (code "246") (name "unconnected-(U31-P3-Pad12)") (class "Default")
      (node (ref "U31") (pin "12") (pinfunction "P3_12") (pintype "bidirectional"))
    )
    (net (code "247") (name "unconnected-(U31-P4-Pad13)") (class "Default")
      (node (ref "U31") (pin "13") (pinfunction "P4_13") (pintype "bidirectional"))
    )
    (net (code "248") (name "unconnected-(U31-P5-Pad14)") (class "Default")
      (node (ref "U31") (pin "14") (pinfunction "P5_14") (pintype "bidirectional"))
    )
    (net (code "249") (name "unconnected-(U31-P6-Pad15)") (class "Default")
      (node (ref "U31") (pin "15") (pinfunction "P6_15") (pintype "bidirectional"))
    )
    (net (code "250") (name "unconnected-(U31-P7-Pad16)") (class "Default")
      (node (ref "U31") (pin "16") (pinfunction "P7_16") (pintype "bidirectional"))
    )
    (net (code "251") (name "unconnected-(U32-INT-Pad7)") (class "Default")
      (node (ref "U32") (pin "7") (pinfunction "INT_7") (pintype "bidirectional"))
    )
    (net (code "252") (name "~{BACKPLANE_RESET}") (class "Default")
      (node (ref "J3") (pin "22") (pinfunction "~{BACKPLANE_RESET}_22") (pintype "bidirectional"))
      (node (ref "R27") (pin "2") (pinfunction "2_2") (pintype "passive"))
      (node (ref "TP9") (pin "TESTPOINT") (pinfunction "TESTPOINT_TESTPOINT") (pintype "bidirectional"))
      (node (ref "U26") (pin "4") (pinfunction "~{RESET}_4") (pintype "bidirectional"))
      (node (ref "U27") (pin "4") (pinfunction "~{RESET}_4") (pintype "bidirectional"))
      (node (ref "U28") (pin "4") (pinfunction "~{RESET}_4") (pintype "bidirectional"))
      (node (ref "U29") (pin "4") (pinfunction "~{RESET}_4") (pintype "bidirectional"))
      (node (ref "U30") (pin "4") (pinfunction "~{RESET}_4") (pintype "bidirectional"))
      (node (ref "U31") (pin "4") (pinfunction "~{RESET}_4") (pintype "bidirectional"))
      (node (ref "U32") (pin "4") (pinfunction "~{RESET}_4") (pintype "bidirectional"))
    )
    (net (code "253") (name "~{SMBALERT}") (class "Default")
      (node (ref "J3") (pin "6") (pinfunction "~{SMBALERT}_6") (pintype "bidirectional"))
      (node (ref "J4") (pin "6") (pinfunction "~{SMBALERT}_6") (pintype "bidirectional"))
      (node (ref "R48") (pin "1") (pinfunction "1_1") (pintype "passive"))
      (node (ref "TP3") (pin "TESTPOINT") (pinfunction "TESTPOINT_TESTPOINT") (pintype "bidirectional"))
    )
    (net (code "254") (name "~{USB_RESET}") (class "Default")
      (node (ref "R52") (pin "1") (pinfunction "1_1") (pintype "passive"))
      (node (ref "U1") (pin "6") (pinfunction "~{RESET}_6") (pintype "bidirectional"))
      (node (ref "U32") (pin "9") (pinfunction "P0_9") (pintype "bidirectional"))
      (node (ref "U33") (pin "1") (pinfunction "~{RST}_1") (pintype "bidirectional"))
    )
    (net (code "255") (name "~{WATCHDOG}") (class "Default")
      (node (ref "J3") (pin "7") (pinfunction "~{WATCHDOG}_7") (pintype "bidirectional"))
      (node (ref "J4") (pin "16") (pinfunction "WDI_16") (pintype "power_in"))
    )
  )
)
